# haasoscope_pro_fpga_board_-_before_autor.net
KiCad netlist of a schematic drawn in EAGLE
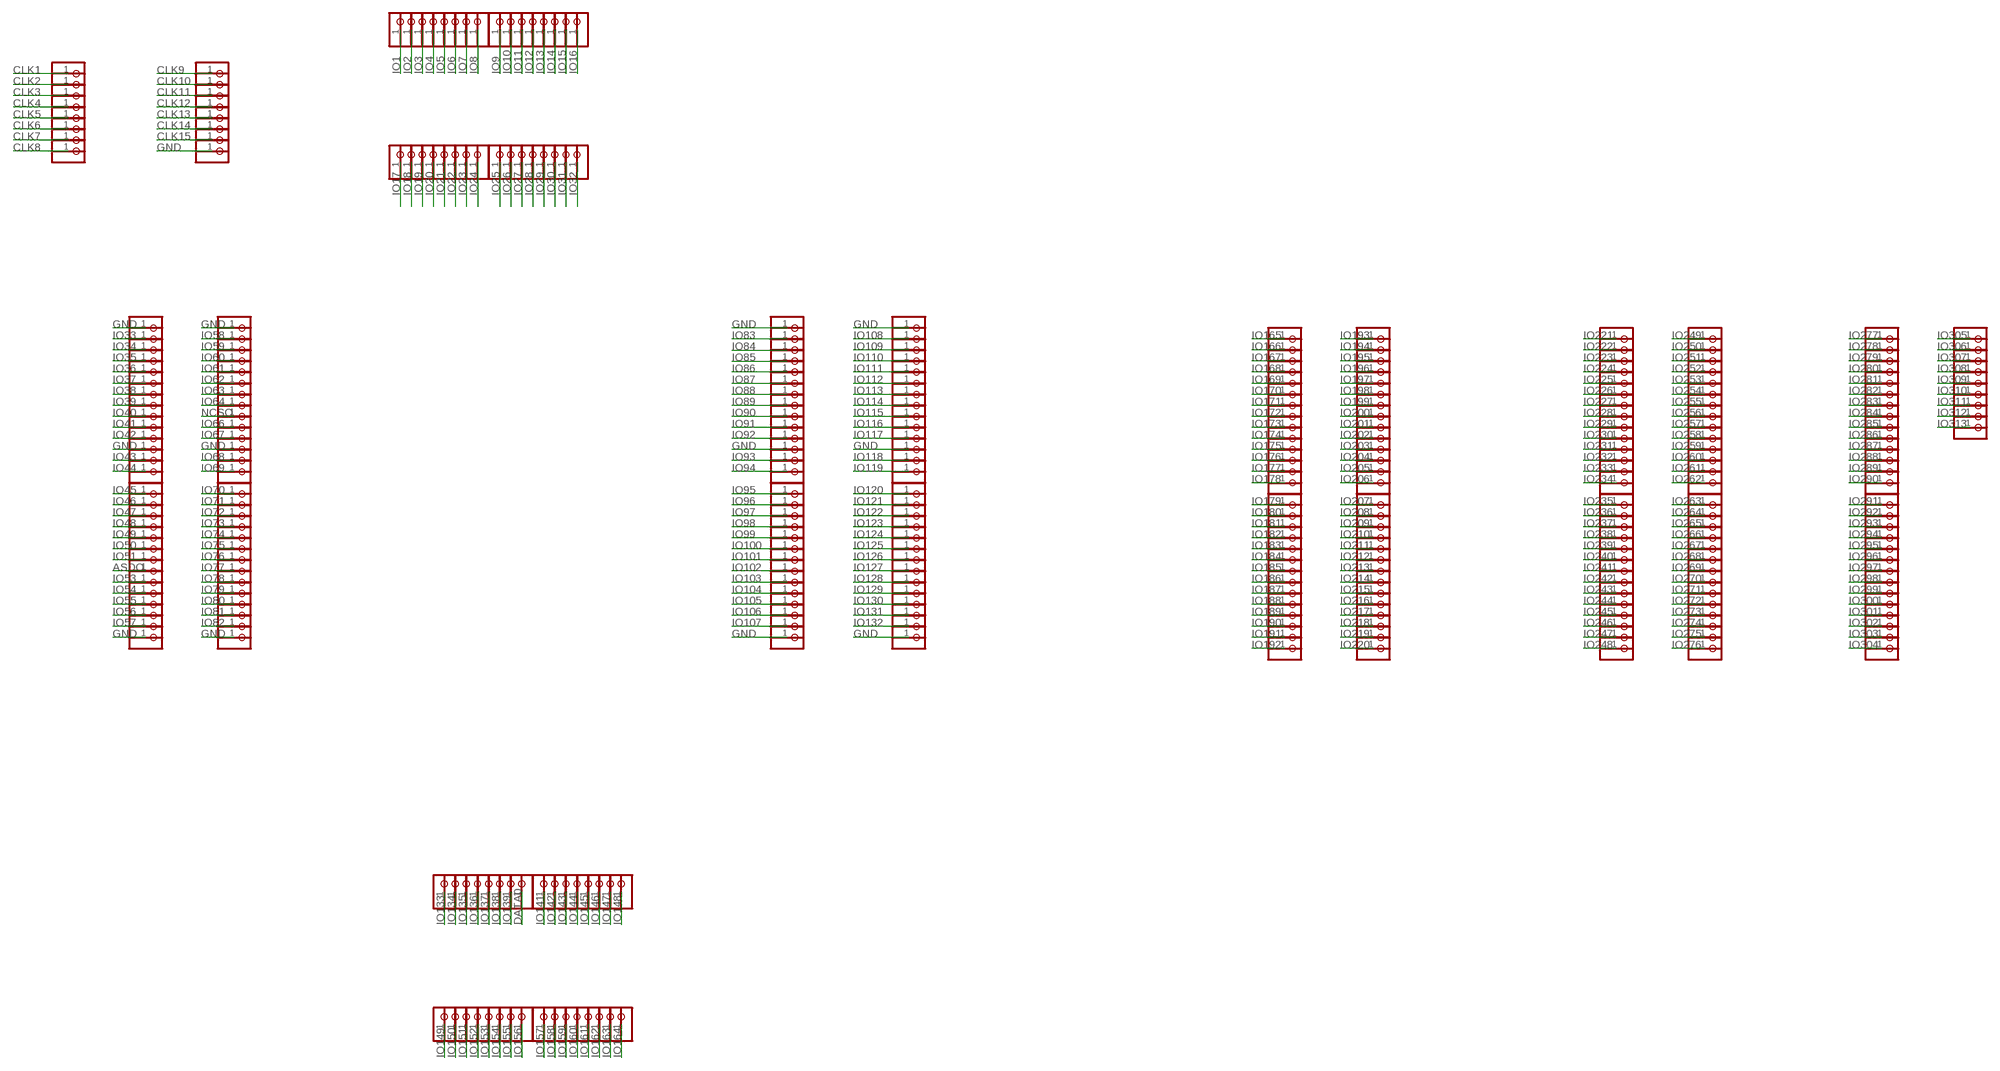
[diagram p0: schematic, sheet 1]
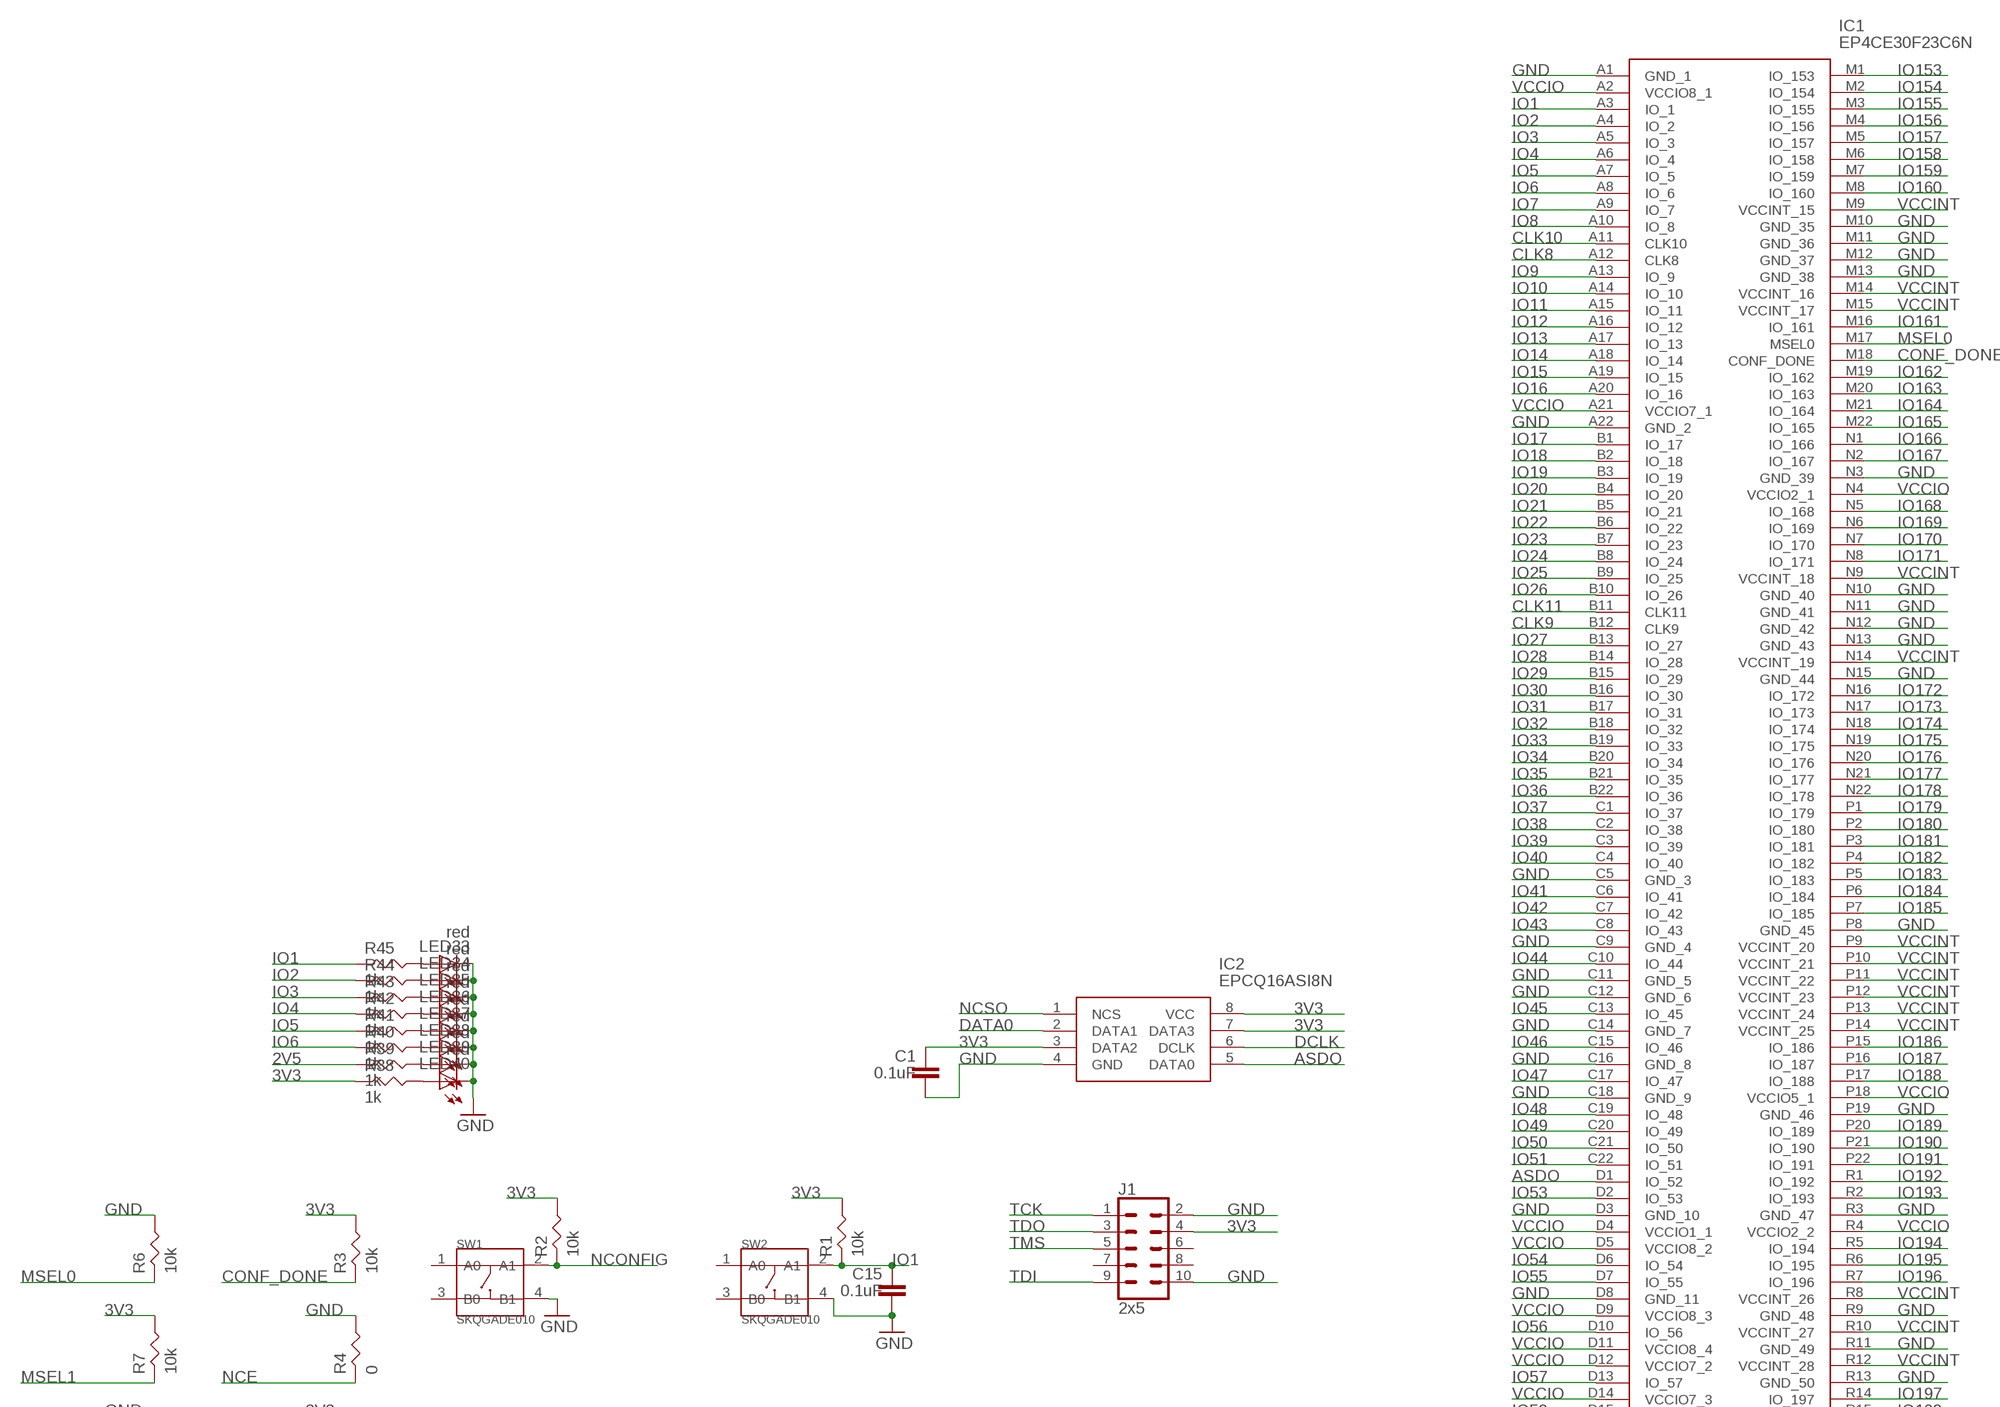
[diagram p1: schematic, sheet 2, part 1 of 2]
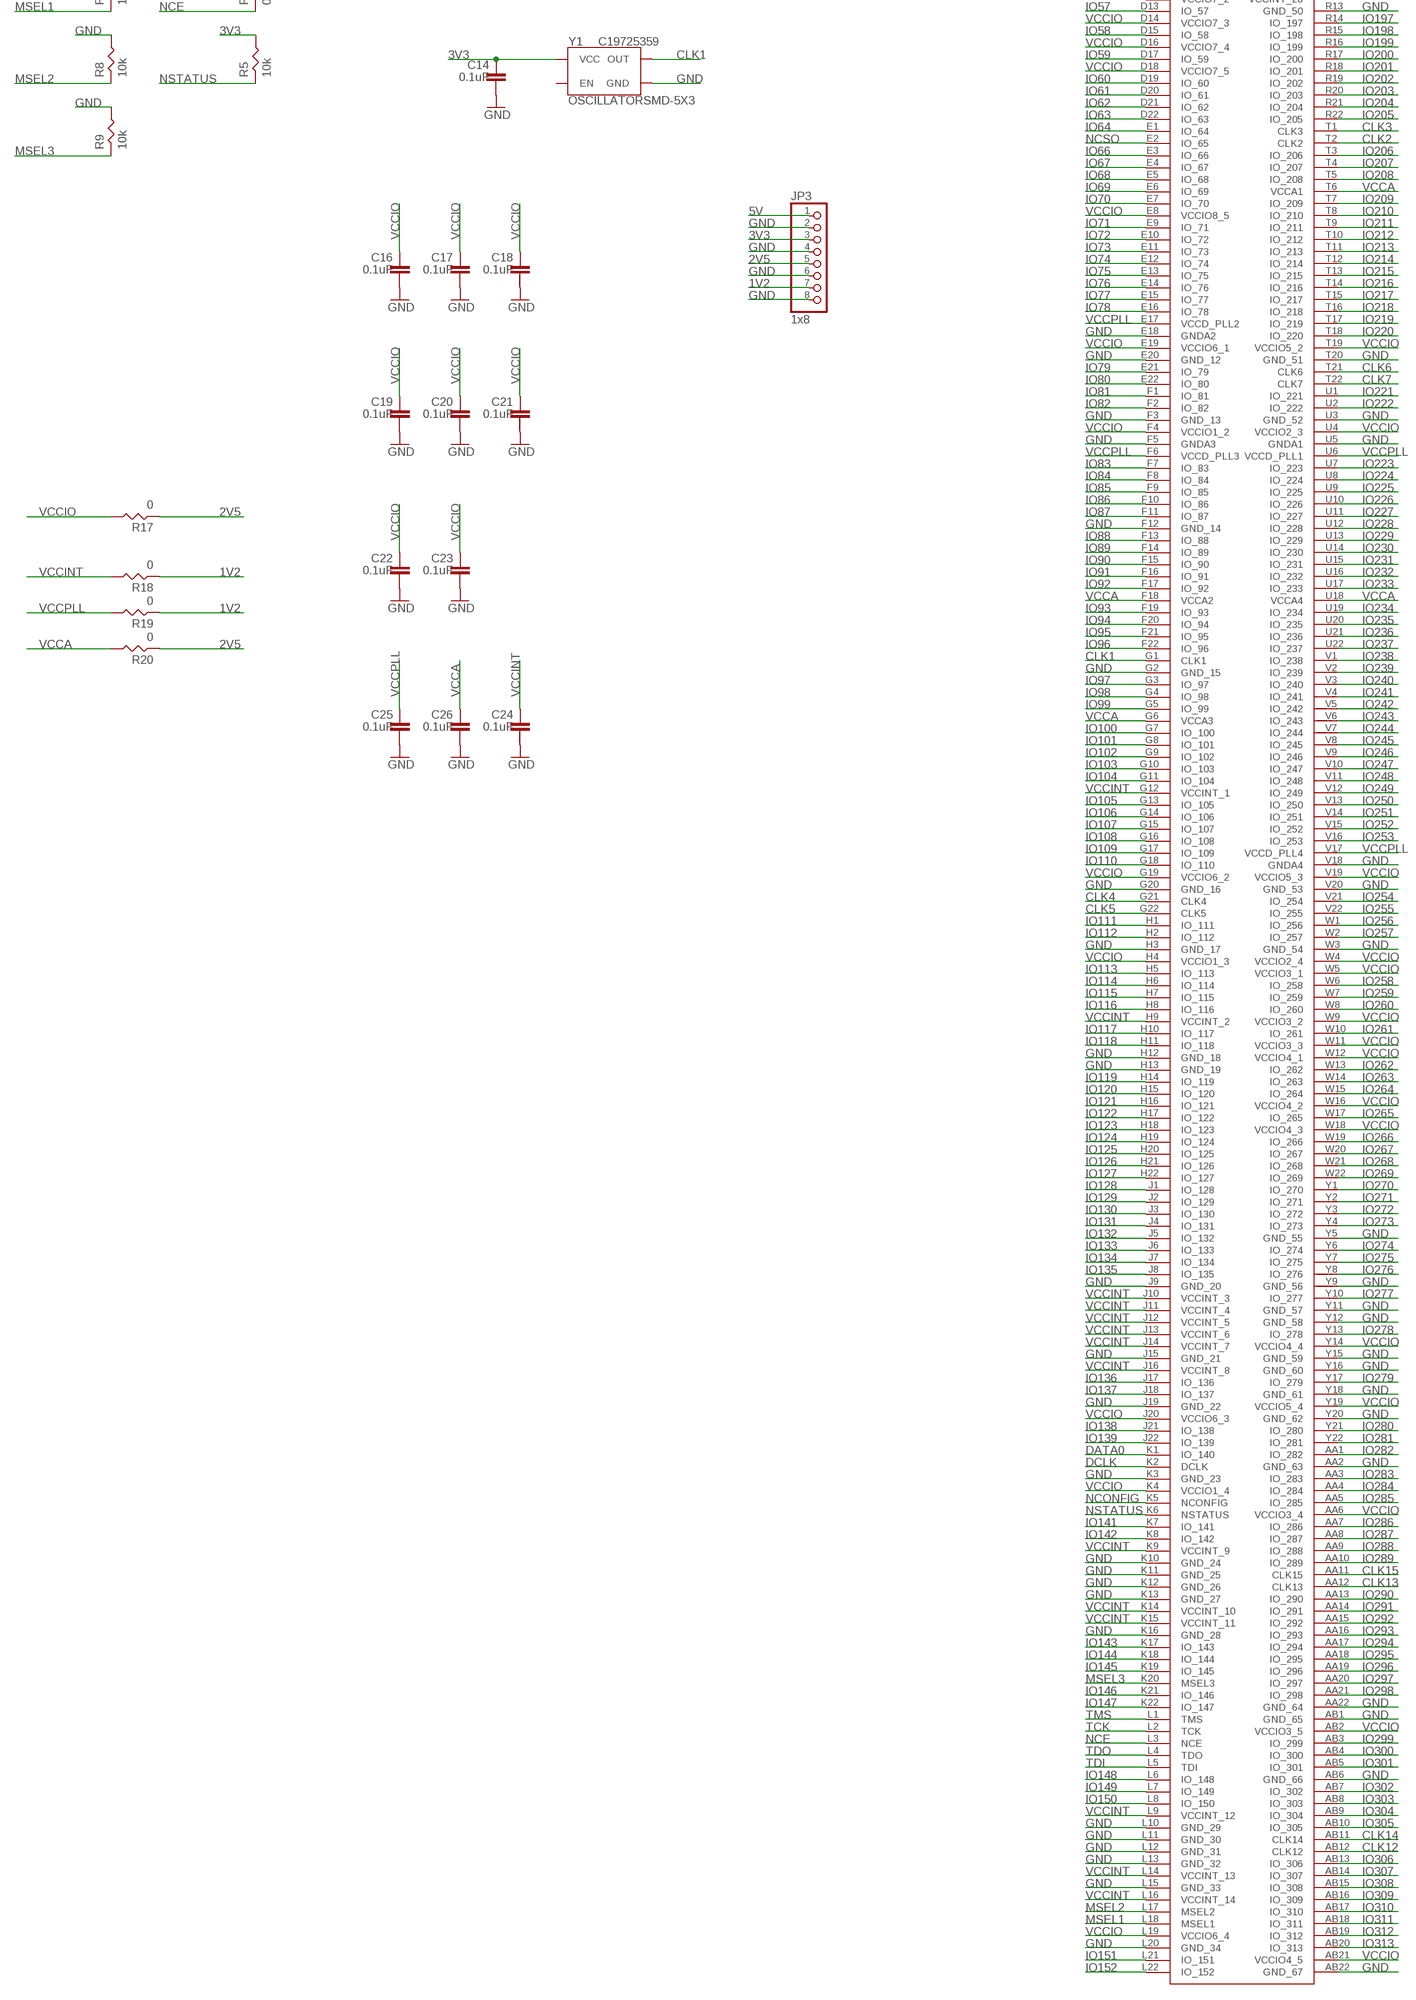
[diagram p2: schematic, sheet 2, part 2 of 2]
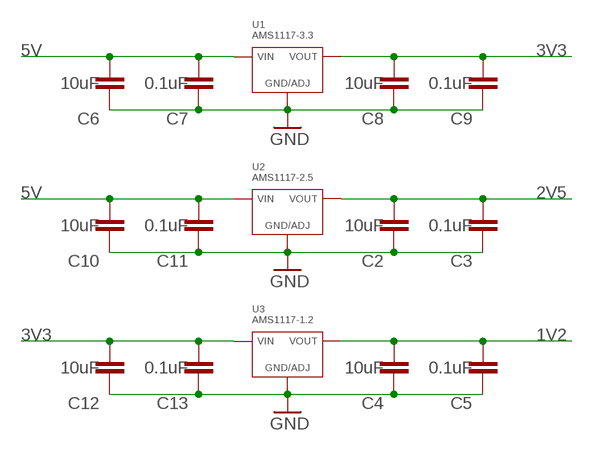
[diagram p3: schematic, sheet 3]

(export (version "E")
  (design (tool "Eeschema 10.0.6"))
  (components
    (comp (ref "C2")
      (value "10uF")
      (footprint "eagle-import:RESC0805_N")
      (libsource (lib "eagle-import") (part "CAPACITOR_0805_N"))
    )
    (comp (ref "C3")
      (value "0.1uF")
      (footprint "eagle-import:RESC0402_N")
      (libsource (lib "eagle-import") (part "CAPACITOR_0402_N"))
    )
    (comp (ref "C4")
      (value "10uF")
      (footprint "eagle-import:RESC0805_N")
      (libsource (lib "eagle-import") (part "CAPACITOR_0805_N"))
    )
    (comp (ref "C5")
      (value "0.1uF")
      (footprint "eagle-import:RESC0402_N")
      (libsource (lib "eagle-import") (part "CAPACITOR_0402_N"))
    )
    (comp (ref "C6")
      (value "10uF")
      (footprint "eagle-import:RESC0805_N")
      (libsource (lib "eagle-import") (part "CAPACITOR_0805_N"))
    )
    (comp (ref "C7")
      (value "0.1uF")
      (footprint "eagle-import:RESC0402_N")
      (libsource (lib "eagle-import") (part "CAPACITOR_0402_N"))
    )
    (comp (ref "C8")
      (value "10uF")
      (footprint "eagle-import:RESC0805_N")
      (libsource (lib "eagle-import") (part "CAPACITOR_0805_N"))
    )
    (comp (ref "C9")
      (value "0.1uF")
      (footprint "eagle-import:RESC0402_N")
      (libsource (lib "eagle-import") (part "CAPACITOR_0402_N"))
    )
    (comp (ref "C10")
      (value "10uF")
      (footprint "eagle-import:RESC0805_N")
      (libsource (lib "eagle-import") (part "CAPACITOR_0805_N"))
    )
    (comp (ref "C11")
      (value "0.1uF")
      (footprint "eagle-import:RESC0402_N")
      (libsource (lib "eagle-import") (part "CAPACITOR_0402_N"))
    )
    (comp (ref "C12")
      (value "10uF")
      (footprint "eagle-import:RESC0805_N")
      (libsource (lib "eagle-import") (part "CAPACITOR_0805_N"))
    )
    (comp (ref "C13")
      (value "0.1uF")
      (footprint "eagle-import:RESC0402_N")
      (libsource (lib "eagle-import") (part "CAPACITOR_0402_N"))
    )
    (comp (ref "U1")
      (value "AMS1117-3.3")
      (footprint "eagle-import:SOT-223-3")
      (fields
        (field (name "HOUSEPART") "NO")
        (field (name "MPN") "NCP1117LPST33T3G")
        (field (name "MPN_1") "AMS1117-3.3")
      )
      (libsource (lib "eagle-import") (part "NCP1117LPST33T3G"))
    )
    (comp (ref "U2")
      (value "AMS1117-2.5")
      (footprint "eagle-import:SOT-223-3")
      (fields
        (field (name "HOUSEPART") "NO")
        (field (name "MPN") "NCP1117LPST33T3G")
        (field (name "MPN_1") "AMS1117-2.5")
      )
      (libsource (lib "eagle-import") (part "NCP1117LPST33T3G"))
    )
    (comp (ref "U3")
      (value "AMS1117-1.2")
      (footprint "eagle-import:SOT-223-3")
      (fields
        (field (name "HOUSEPART") "NO")
        (field (name "MPN") "NCP1117LPST33T3G")
        (field (name "MPN_1") "AMS1117-1.2")
      )
      (libsource (lib "eagle-import") (part "NCP1117LPST33T3G"))
    )
    (comp (ref "JP1")
      (value "1")
      (footprint "eagle-import:1X01")
      (libsource (lib "eagle-import") (part "PINHD-1X1"))
    )
    (comp (ref "JP2")
      (value "1")
      (footprint "eagle-import:1X01")
      (libsource (lib "eagle-import") (part "PINHD-1X1"))
    )
    (comp (ref "JP4")
      (value "1")
      (footprint "eagle-import:1X01")
      (libsource (lib "eagle-import") (part "PINHD-1X1"))
    )
    (comp (ref "JP5")
      (value "1")
      (footprint "eagle-import:1X01")
      (libsource (lib "eagle-import") (part "PINHD-1X1"))
    )
    (comp (ref "JP6")
      (value "1")
      (footprint "eagle-import:1X01")
      (libsource (lib "eagle-import") (part "PINHD-1X1"))
    )
    (comp (ref "JP7")
      (value "1")
      (footprint "eagle-import:1X01")
      (libsource (lib "eagle-import") (part "PINHD-1X1"))
    )
    (comp (ref "JP8")
      (value "1")
      (footprint "eagle-import:1X01")
      (libsource (lib "eagle-import") (part "PINHD-1X1"))
    )
    (comp (ref "JP9")
      (value "1")
      (footprint "eagle-import:1X01")
      (libsource (lib "eagle-import") (part "PINHD-1X1"))
    )
    (comp (ref "JP10")
      (value "1")
      (footprint "eagle-import:1X01")
      (libsource (lib "eagle-import") (part "PINHD-1X1"))
    )
    (comp (ref "JP11")
      (value "1")
      (footprint "eagle-import:1X01")
      (libsource (lib "eagle-import") (part "PINHD-1X1"))
    )
    (comp (ref "JP12")
      (value "1")
      (footprint "eagle-import:1X01")
      (libsource (lib "eagle-import") (part "PINHD-1X1"))
    )
    (comp (ref "JP13")
      (value "1")
      (footprint "eagle-import:1X01")
      (libsource (lib "eagle-import") (part "PINHD-1X1"))
    )
    (comp (ref "JP14")
      (value "1")
      (footprint "eagle-import:1X01")
      (libsource (lib "eagle-import") (part "PINHD-1X1"))
    )
    (comp (ref "JP15")
      (value "1")
      (footprint "eagle-import:1X01")
      (libsource (lib "eagle-import") (part "PINHD-1X1"))
    )
    (comp (ref "JP16")
      (value "1")
      (footprint "eagle-import:1X01")
      (libsource (lib "eagle-import") (part "PINHD-1X1"))
    )
    (comp (ref "JP17")
      (value "1")
      (footprint "eagle-import:1X01")
      (libsource (lib "eagle-import") (part "PINHD-1X1"))
    )
    (comp (ref "JP18")
      (value "1")
      (footprint "eagle-import:1X01")
      (libsource (lib "eagle-import") (part "PINHD-1X1"))
    )
    (comp (ref "JP19")
      (value "1")
      (footprint "eagle-import:1X01")
      (libsource (lib "eagle-import") (part "PINHD-1X1"))
    )
    (comp (ref "JP20")
      (value "1")
      (footprint "eagle-import:1X01")
      (libsource (lib "eagle-import") (part "PINHD-1X1"))
    )
    (comp (ref "JP21")
      (value "1")
      (footprint "eagle-import:1X01")
      (libsource (lib "eagle-import") (part "PINHD-1X1"))
    )
    (comp (ref "JP22")
      (value "1")
      (footprint "eagle-import:1X01")
      (libsource (lib "eagle-import") (part "PINHD-1X1"))
    )
    (comp (ref "JP23")
      (value "1")
      (footprint "eagle-import:1X01")
      (libsource (lib "eagle-import") (part "PINHD-1X1"))
    )
    (comp (ref "JP24")
      (value "1")
      (footprint "eagle-import:1X01")
      (libsource (lib "eagle-import") (part "PINHD-1X1"))
    )
    (comp (ref "JP25")
      (value "1")
      (footprint "eagle-import:1X01")
      (libsource (lib "eagle-import") (part "PINHD-1X1"))
    )
    (comp (ref "JP26")
      (value "1")
      (footprint "eagle-import:1X01")
      (libsource (lib "eagle-import") (part "PINHD-1X1"))
    )
    (comp (ref "JP27")
      (value "1")
      (footprint "eagle-import:1X01")
      (libsource (lib "eagle-import") (part "PINHD-1X1"))
    )
    (comp (ref "JP28")
      (value "1")
      (footprint "eagle-import:1X01")
      (libsource (lib "eagle-import") (part "PINHD-1X1"))
    )
    (comp (ref "JP29")
      (value "1")
      (footprint "eagle-import:1X01")
      (libsource (lib "eagle-import") (part "PINHD-1X1"))
    )
    (comp (ref "JP30")
      (value "1")
      (footprint "eagle-import:1X01")
      (libsource (lib "eagle-import") (part "PINHD-1X1"))
    )
    (comp (ref "JP31")
      (value "1")
      (footprint "eagle-import:1X01")
      (libsource (lib "eagle-import") (part "PINHD-1X1"))
    )
    (comp (ref "JP32")
      (value "1")
      (footprint "eagle-import:1X01")
      (libsource (lib "eagle-import") (part "PINHD-1X1"))
    )
    (comp (ref "JP33")
      (value "1")
      (footprint "eagle-import:1X01")
      (libsource (lib "eagle-import") (part "PINHD-1X1"))
    )
    (comp (ref "JP34")
      (value "1")
      (footprint "eagle-import:1X01")
      (libsource (lib "eagle-import") (part "PINHD-1X1"))
    )
    (comp (ref "JP35")
      (value "1")
      (footprint "eagle-import:1X01")
      (libsource (lib "eagle-import") (part "PINHD-1X1"))
    )
    (comp (ref "JP36")
      (value "1")
      (footprint "eagle-import:1X01")
      (libsource (lib "eagle-import") (part "PINHD-1X1"))
    )
    (comp (ref "JP37")
      (value "1")
      (footprint "eagle-import:1X01")
      (libsource (lib "eagle-import") (part "PINHD-1X1"))
    )
    (comp (ref "JP38")
      (value "1")
      (footprint "eagle-import:1X01")
      (libsource (lib "eagle-import") (part "PINHD-1X1"))
    )
    (comp (ref "JP39")
      (value "1")
      (footprint "eagle-import:1X01")
      (libsource (lib "eagle-import") (part "PINHD-1X1"))
    )
    (comp (ref "JP40")
      (value "1")
      (footprint "eagle-import:1X01")
      (libsource (lib "eagle-import") (part "PINHD-1X1"))
    )
    (comp (ref "JP41")
      (value "1")
      (footprint "eagle-import:1X01")
      (libsource (lib "eagle-import") (part "PINHD-1X1"))
    )
    (comp (ref "JP42")
      (value "1")
      (footprint "eagle-import:1X01")
      (libsource (lib "eagle-import") (part "PINHD-1X1"))
    )
    (comp (ref "JP43")
      (value "1")
      (footprint "eagle-import:1X01")
      (libsource (lib "eagle-import") (part "PINHD-1X1"))
    )
    (comp (ref "JP44")
      (value "1")
      (footprint "eagle-import:1X01")
      (libsource (lib "eagle-import") (part "PINHD-1X1"))
    )
    (comp (ref "JP45")
      (value "1")
      (footprint "eagle-import:1X01")
      (libsource (lib "eagle-import") (part "PINHD-1X1"))
    )
    (comp (ref "JP46")
      (value "1")
      (footprint "eagle-import:1X01")
      (libsource (lib "eagle-import") (part "PINHD-1X1"))
    )
    (comp (ref "JP47")
      (value "1")
      (footprint "eagle-import:1X01")
      (libsource (lib "eagle-import") (part "PINHD-1X1"))
    )
    (comp (ref "JP48")
      (value "1")
      (footprint "eagle-import:1X01")
      (libsource (lib "eagle-import") (part "PINHD-1X1"))
    )
    (comp (ref "JP49")
      (value "1")
      (footprint "eagle-import:1X01")
      (libsource (lib "eagle-import") (part "PINHD-1X1"))
    )
    (comp (ref "JP50")
      (value "1")
      (footprint "eagle-import:1X01")
      (libsource (lib "eagle-import") (part "PINHD-1X1"))
    )
    (comp (ref "JP51")
      (value "1")
      (footprint "eagle-import:1X01")
      (libsource (lib "eagle-import") (part "PINHD-1X1"))
    )
    (comp (ref "JP52")
      (value "1")
      (footprint "eagle-import:1X01")
      (libsource (lib "eagle-import") (part "PINHD-1X1"))
    )
    (comp (ref "JP53")
      (value "1")
      (footprint "eagle-import:1X01")
      (libsource (lib "eagle-import") (part "PINHD-1X1"))
    )
    (comp (ref "JP54")
      (value "1")
      (footprint "eagle-import:1X01")
      (libsource (lib "eagle-import") (part "PINHD-1X1"))
    )
    (comp (ref "JP55")
      (value "1")
      (footprint "eagle-import:1X01")
      (libsource (lib "eagle-import") (part "PINHD-1X1"))
    )
    (comp (ref "JP56")
      (value "1")
      (footprint "eagle-import:1X01")
      (libsource (lib "eagle-import") (part "PINHD-1X1"))
    )
    (comp (ref "JP57")
      (value "1")
      (footprint "eagle-import:1X01")
      (libsource (lib "eagle-import") (part "PINHD-1X1"))
    )
    (comp (ref "JP58")
      (value "1")
      (footprint "eagle-import:1X01")
      (libsource (lib "eagle-import") (part "PINHD-1X1"))
    )
    (comp (ref "JP59")
      (value "1")
      (footprint "eagle-import:1X01")
      (libsource (lib "eagle-import") (part "PINHD-1X1"))
    )
    (comp (ref "JP60")
      (value "1")
      (footprint "eagle-import:1X01")
      (libsource (lib "eagle-import") (part "PINHD-1X1"))
    )
    (comp (ref "JP61")
      (value "1")
      (footprint "eagle-import:1X01")
      (libsource (lib "eagle-import") (part "PINHD-1X1"))
    )
    (comp (ref "JP62")
      (value "1")
      (footprint "eagle-import:1X01")
      (libsource (lib "eagle-import") (part "PINHD-1X1"))
    )
    (comp (ref "JP63")
      (value "1")
      (footprint "eagle-import:1X01")
      (libsource (lib "eagle-import") (part "PINHD-1X1"))
    )
    (comp (ref "JP64")
      (value "1")
      (footprint "eagle-import:1X01")
      (libsource (lib "eagle-import") (part "PINHD-1X1"))
    )
    (comp (ref "JP65")
      (value "1")
      (footprint "eagle-import:1X01")
      (libsource (lib "eagle-import") (part "PINHD-1X1"))
    )
    (comp (ref "JP66")
      (value "1")
      (footprint "eagle-import:1X01")
      (libsource (lib "eagle-import") (part "PINHD-1X1"))
    )
    (comp (ref "JP67")
      (value "1")
      (footprint "eagle-import:1X01")
      (libsource (lib "eagle-import") (part "PINHD-1X1"))
    )
    (comp (ref "JP68")
      (value "1")
      (footprint "eagle-import:1X01")
      (libsource (lib "eagle-import") (part "PINHD-1X1"))
    )
    (comp (ref "JP69")
      (value "1")
      (footprint "eagle-import:1X01")
      (libsource (lib "eagle-import") (part "PINHD-1X1"))
    )
    (comp (ref "JP70")
      (value "1")
      (footprint "eagle-import:1X01")
      (libsource (lib "eagle-import") (part "PINHD-1X1"))
    )
    (comp (ref "JP71")
      (value "1")
      (footprint "eagle-import:1X01")
      (libsource (lib "eagle-import") (part "PINHD-1X1"))
    )
    (comp (ref "JP72")
      (value "1")
      (footprint "eagle-import:1X01")
      (libsource (lib "eagle-import") (part "PINHD-1X1"))
    )
    (comp (ref "JP73")
      (value "1")
      (footprint "eagle-import:1X01")
      (libsource (lib "eagle-import") (part "PINHD-1X1"))
    )
    (comp (ref "JP74")
      (value "1")
      (footprint "eagle-import:1X01")
      (libsource (lib "eagle-import") (part "PINHD-1X1"))
    )
    (comp (ref "JP75")
      (value "1")
      (footprint "eagle-import:1X01")
      (libsource (lib "eagle-import") (part "PINHD-1X1"))
    )
    (comp (ref "JP76")
      (value "1")
      (footprint "eagle-import:1X01")
      (libsource (lib "eagle-import") (part "PINHD-1X1"))
    )
    (comp (ref "JP77")
      (value "1")
      (footprint "eagle-import:1X01")
      (libsource (lib "eagle-import") (part "PINHD-1X1"))
    )
    (comp (ref "JP78")
      (value "1")
      (footprint "eagle-import:1X01")
      (libsource (lib "eagle-import") (part "PINHD-1X1"))
    )
    (comp (ref "JP79")
      (value "1")
      (footprint "eagle-import:1X01")
      (libsource (lib "eagle-import") (part "PINHD-1X1"))
    )
    (comp (ref "JP80")
      (value "1")
      (footprint "eagle-import:1X01")
      (libsource (lib "eagle-import") (part "PINHD-1X1"))
    )
    (comp (ref "JP81")
      (value "1")
      (footprint "eagle-import:1X01")
      (libsource (lib "eagle-import") (part "PINHD-1X1"))
    )
    (comp (ref "JP82")
      (value "1")
      (footprint "eagle-import:1X01")
      (libsource (lib "eagle-import") (part "PINHD-1X1"))
    )
    (comp (ref "JP83")
      (value "1")
      (footprint "eagle-import:1X01")
      (libsource (lib "eagle-import") (part "PINHD-1X1"))
    )
    (comp (ref "JP84")
      (value "1")
      (footprint "eagle-import:1X01")
      (libsource (lib "eagle-import") (part "PINHD-1X1"))
    )
    (comp (ref "JP85")
      (value "1")
      (footprint "eagle-import:1X01")
      (libsource (lib "eagle-import") (part "PINHD-1X1"))
    )
    (comp (ref "JP86")
      (value "1")
      (footprint "eagle-import:1X01")
      (libsource (lib "eagle-import") (part "PINHD-1X1"))
    )
    (comp (ref "JP87")
      (value "1")
      (footprint "eagle-import:1X01")
      (libsource (lib "eagle-import") (part "PINHD-1X1"))
    )
    (comp (ref "JP88")
      (value "1")
      (footprint "eagle-import:1X01")
      (libsource (lib "eagle-import") (part "PINHD-1X1"))
    )
    (comp (ref "JP89")
      (value "1")
      (footprint "eagle-import:1X01")
      (libsource (lib "eagle-import") (part "PINHD-1X1"))
    )
    (comp (ref "JP90")
      (value "1")
      (footprint "eagle-import:1X01")
      (libsource (lib "eagle-import") (part "PINHD-1X1"))
    )
    (comp (ref "JP91")
      (value "1")
      (footprint "eagle-import:1X01")
      (libsource (lib "eagle-import") (part "PINHD-1X1"))
    )
    (comp (ref "JP92")
      (value "1")
      (footprint "eagle-import:1X01")
      (libsource (lib "eagle-import") (part "PINHD-1X1"))
    )
    (comp (ref "JP93")
      (value "1")
      (footprint "eagle-import:1X01")
      (libsource (lib "eagle-import") (part "PINHD-1X1"))
    )
    (comp (ref "JP94")
      (value "1")
      (footprint "eagle-import:1X01")
      (libsource (lib "eagle-import") (part "PINHD-1X1"))
    )
    (comp (ref "JP95")
      (value "1")
      (footprint "eagle-import:1X01")
      (libsource (lib "eagle-import") (part "PINHD-1X1"))
    )
    (comp (ref "JP96")
      (value "1")
      (footprint "eagle-import:1X01")
      (libsource (lib "eagle-import") (part "PINHD-1X1"))
    )
    (comp (ref "JP97")
      (value "1")
      (footprint "eagle-import:1X01")
      (libsource (lib "eagle-import") (part "PINHD-1X1"))
    )
    (comp (ref "JP98")
      (value "1")
      (footprint "eagle-import:1X01")
      (libsource (lib "eagle-import") (part "PINHD-1X1"))
    )
    (comp (ref "JP99")
      (value "1")
      (footprint "eagle-import:1X01")
      (libsource (lib "eagle-import") (part "PINHD-1X1"))
    )
    (comp (ref "JP100")
      (value "1")
      (footprint "eagle-import:1X01")
      (libsource (lib "eagle-import") (part "PINHD-1X1"))
    )
    (comp (ref "JP101")
      (value "1")
      (footprint "eagle-import:1X01")
      (libsource (lib "eagle-import") (part "PINHD-1X1"))
    )
    (comp (ref "JP102")
      (value "1")
      (footprint "eagle-import:1X01")
      (libsource (lib "eagle-import") (part "PINHD-1X1"))
    )
    (comp (ref "JP103")
      (value "1")
      (footprint "eagle-import:1X01")
      (libsource (lib "eagle-import") (part "PINHD-1X1"))
    )
    (comp (ref "JP104")
      (value "1")
      (footprint "eagle-import:1X01")
      (libsource (lib "eagle-import") (part "PINHD-1X1"))
    )
    (comp (ref "JP105")
      (value "1")
      (footprint "eagle-import:1X01")
      (libsource (lib "eagle-import") (part "PINHD-1X1"))
    )
    (comp (ref "JP106")
      (value "1")
      (footprint "eagle-import:1X01")
      (libsource (lib "eagle-import") (part "PINHD-1X1"))
    )
    (comp (ref "JP107")
      (value "1")
      (footprint "eagle-import:1X01")
      (libsource (lib "eagle-import") (part "PINHD-1X1"))
    )
    (comp (ref "JP108")
      (value "1")
      (footprint "eagle-import:1X01")
      (libsource (lib "eagle-import") (part "PINHD-1X1"))
    )
    (comp (ref "JP109")
      (value "1")
      (footprint "eagle-import:1X01")
      (libsource (lib "eagle-import") (part "PINHD-1X1"))
    )
    (comp (ref "JP110")
      (value "1")
      (footprint "eagle-import:1X01")
      (libsource (lib "eagle-import") (part "PINHD-1X1"))
    )
    (comp (ref "JP111")
      (value "1")
      (footprint "eagle-import:1X01")
      (libsource (lib "eagle-import") (part "PINHD-1X1"))
    )
    (comp (ref "JP112")
      (value "1")
      (footprint "eagle-import:1X01")
      (libsource (lib "eagle-import") (part "PINHD-1X1"))
    )
    (comp (ref "JP113")
      (value "1")
      (footprint "eagle-import:1X01")
      (libsource (lib "eagle-import") (part "PINHD-1X1"))
    )
    (comp (ref "JP114")
      (value "1")
      (footprint "eagle-import:1X01")
      (libsource (lib "eagle-import") (part "PINHD-1X1"))
    )
    (comp (ref "JP115")
      (value "1")
      (footprint "eagle-import:1X01")
      (libsource (lib "eagle-import") (part "PINHD-1X1"))
    )
    (comp (ref "JP116")
      (value "1")
      (footprint "eagle-import:1X01")
      (libsource (lib "eagle-import") (part "PINHD-1X1"))
    )
    (comp (ref "JP117")
      (value "1")
      (footprint "eagle-import:1X01")
      (libsource (lib "eagle-import") (part "PINHD-1X1"))
    )
    (comp (ref "JP118")
      (value "1")
      (footprint "eagle-import:1X01")
      (libsource (lib "eagle-import") (part "PINHD-1X1"))
    )
    (comp (ref "JP119")
      (value "1")
      (footprint "eagle-import:1X01")
      (libsource (lib "eagle-import") (part "PINHD-1X1"))
    )
    (comp (ref "JP120")
      (value "1")
      (footprint "eagle-import:1X01")
      (libsource (lib "eagle-import") (part "PINHD-1X1"))
    )
    (comp (ref "JP121")
      (value "1")
      (footprint "eagle-import:1X01")
      (libsource (lib "eagle-import") (part "PINHD-1X1"))
    )
    (comp (ref "JP122")
      (value "1")
      (footprint "eagle-import:1X01")
      (libsource (lib "eagle-import") (part "PINHD-1X1"))
    )
    (comp (ref "JP123")
      (value "1")
      (footprint "eagle-import:1X01")
      (libsource (lib "eagle-import") (part "PINHD-1X1"))
    )
    (comp (ref "JP124")
      (value "1")
      (footprint "eagle-import:1X01")
      (libsource (lib "eagle-import") (part "PINHD-1X1"))
    )
    (comp (ref "JP125")
      (value "1")
      (footprint "eagle-import:1X01")
      (libsource (lib "eagle-import") (part "PINHD-1X1"))
    )
    (comp (ref "JP126")
      (value "1")
      (footprint "eagle-import:1X01")
      (libsource (lib "eagle-import") (part "PINHD-1X1"))
    )
    (comp (ref "JP127")
      (value "1")
      (footprint "eagle-import:1X01")
      (libsource (lib "eagle-import") (part "PINHD-1X1"))
    )
    (comp (ref "JP128")
      (value "1")
      (footprint "eagle-import:1X01")
      (libsource (lib "eagle-import") (part "PINHD-1X1"))
    )
    (comp (ref "JP129")
      (value "1")
      (footprint "eagle-import:1X01")
      (libsource (lib "eagle-import") (part "PINHD-1X1"))
    )
    (comp (ref "JP130")
      (value "1")
      (footprint "eagle-import:1X01")
      (libsource (lib "eagle-import") (part "PINHD-1X1"))
    )
    (comp (ref "JP131")
      (value "1")
      (footprint "eagle-import:1X01")
      (libsource (lib "eagle-import") (part "PINHD-1X1"))
    )
    (comp (ref "JP132")
      (value "1")
      (footprint "eagle-import:1X01")
      (libsource (lib "eagle-import") (part "PINHD-1X1"))
    )
    (comp (ref "JP133")
      (value "1")
      (footprint "eagle-import:1X01")
      (libsource (lib "eagle-import") (part "PINHD-1X1"))
    )
    (comp (ref "JP134")
      (value "1")
      (footprint "eagle-import:1X01")
      (libsource (lib "eagle-import") (part "PINHD-1X1"))
    )
    (comp (ref "JP135")
      (value "1")
      (footprint "eagle-import:1X01")
      (libsource (lib "eagle-import") (part "PINHD-1X1"))
    )
    (comp (ref "JP136")
      (value "1")
      (footprint "eagle-import:1X01")
      (libsource (lib "eagle-import") (part "PINHD-1X1"))
    )
    (comp (ref "JP137")
      (value "1")
      (footprint "eagle-import:1X01")
      (libsource (lib "eagle-import") (part "PINHD-1X1"))
    )
    (comp (ref "JP138")
      (value "1")
      (footprint "eagle-import:1X01")
      (libsource (lib "eagle-import") (part "PINHD-1X1"))
    )
    (comp (ref "JP139")
      (value "1")
      (footprint "eagle-import:1X01")
      (libsource (lib "eagle-import") (part "PINHD-1X1"))
    )
    (comp (ref "JP140")
      (value "1")
      (footprint "eagle-import:1X01")
      (libsource (lib "eagle-import") (part "PINHD-1X1"))
    )
    (comp (ref "JP141")
      (value "1")
      (footprint "eagle-import:1X01")
      (libsource (lib "eagle-import") (part "PINHD-1X1"))
    )
    (comp (ref "JP142")
      (value "1")
      (footprint "eagle-import:1X01")
      (libsource (lib "eagle-import") (part "PINHD-1X1"))
    )
    (comp (ref "JP143")
      (value "1")
      (footprint "eagle-import:1X01")
      (libsource (lib "eagle-import") (part "PINHD-1X1"))
    )
    (comp (ref "JP144")
      (value "1")
      (footprint "eagle-import:1X01")
      (libsource (lib "eagle-import") (part "PINHD-1X1"))
    )
    (comp (ref "JP145")
      (value "1")
      (footprint "eagle-import:1X01")
      (libsource (lib "eagle-import") (part "PINHD-1X1"))
    )
    (comp (ref "JP146")
      (value "1")
      (footprint "eagle-import:1X01")
      (libsource (lib "eagle-import") (part "PINHD-1X1"))
    )
    (comp (ref "JP147")
      (value "1")
      (footprint "eagle-import:1X01")
      (libsource (lib "eagle-import") (part "PINHD-1X1"))
    )
    (comp (ref "JP148")
      (value "1")
      (footprint "eagle-import:1X01")
      (libsource (lib "eagle-import") (part "PINHD-1X1"))
    )
    (comp (ref "JP149")
      (value "1")
      (footprint "eagle-import:1X01")
      (libsource (lib "eagle-import") (part "PINHD-1X1"))
    )
    (comp (ref "JP150")
      (value "1")
      (footprint "eagle-import:1X01")
      (libsource (lib "eagle-import") (part "PINHD-1X1"))
    )
    (comp (ref "JP151")
      (value "1")
      (footprint "eagle-import:1X01")
      (libsource (lib "eagle-import") (part "PINHD-1X1"))
    )
    (comp (ref "JP152")
      (value "1")
      (footprint "eagle-import:1X01")
      (libsource (lib "eagle-import") (part "PINHD-1X1"))
    )
    (comp (ref "JP153")
      (value "1")
      (footprint "eagle-import:1X01")
      (libsource (lib "eagle-import") (part "PINHD-1X1"))
    )
    (comp (ref "JP154")
      (value "1")
      (footprint "eagle-import:1X01")
      (libsource (lib "eagle-import") (part "PINHD-1X1"))
    )
    (comp (ref "JP155")
      (value "1")
      (footprint "eagle-import:1X01")
      (libsource (lib "eagle-import") (part "PINHD-1X1"))
    )
    (comp (ref "JP156")
      (value "1")
      (footprint "eagle-import:1X01")
      (libsource (lib "eagle-import") (part "PINHD-1X1"))
    )
    (comp (ref "JP157")
      (value "1")
      (footprint "eagle-import:1X01")
      (libsource (lib "eagle-import") (part "PINHD-1X1"))
    )
    (comp (ref "JP158")
      (value "1")
      (footprint "eagle-import:1X01")
      (libsource (lib "eagle-import") (part "PINHD-1X1"))
    )
    (comp (ref "JP159")
      (value "1")
      (footprint "eagle-import:1X01")
      (libsource (lib "eagle-import") (part "PINHD-1X1"))
    )
    (comp (ref "JP160")
      (value "1")
      (footprint "eagle-import:1X01")
      (libsource (lib "eagle-import") (part "PINHD-1X1"))
    )
    (comp (ref "JP161")
      (value "1")
      (footprint "eagle-import:1X01")
      (libsource (lib "eagle-import") (part "PINHD-1X1"))
    )
    (comp (ref "JP162")
      (value "1")
      (footprint "eagle-import:1X01")
      (libsource (lib "eagle-import") (part "PINHD-1X1"))
    )
    (comp (ref "JP163")
      (value "1")
      (footprint "eagle-import:1X01")
      (libsource (lib "eagle-import") (part "PINHD-1X1"))
    )
    (comp (ref "JP164")
      (value "1")
      (footprint "eagle-import:1X01")
      (libsource (lib "eagle-import") (part "PINHD-1X1"))
    )
    (comp (ref "JP165")
      (value "1")
      (footprint "eagle-import:1X01")
      (libsource (lib "eagle-import") (part "PINHD-1X1"))
    )
    (comp (ref "JP166")
      (value "1")
      (footprint "eagle-import:1X01")
      (libsource (lib "eagle-import") (part "PINHD-1X1"))
    )
    (comp (ref "JP167")
      (value "1")
      (footprint "eagle-import:1X01")
      (libsource (lib "eagle-import") (part "PINHD-1X1"))
    )
    (comp (ref "JP168")
      (value "1")
      (footprint "eagle-import:1X01")
      (libsource (lib "eagle-import") (part "PINHD-1X1"))
    )
    (comp (ref "JP169")
      (value "1")
      (footprint "eagle-import:1X01")
      (libsource (lib "eagle-import") (part "PINHD-1X1"))
    )
    (comp (ref "JP170")
      (value "1")
      (footprint "eagle-import:1X01")
      (libsource (lib "eagle-import") (part "PINHD-1X1"))
    )
    (comp (ref "JP171")
      (value "1")
      (footprint "eagle-import:1X01")
      (libsource (lib "eagle-import") (part "PINHD-1X1"))
    )
    (comp (ref "JP172")
      (value "1")
      (footprint "eagle-import:1X01")
      (libsource (lib "eagle-import") (part "PINHD-1X1"))
    )
    (comp (ref "JP173")
      (value "1")
      (footprint "eagle-import:1X01")
      (libsource (lib "eagle-import") (part "PINHD-1X1"))
    )
    (comp (ref "JP174")
      (value "1")
      (footprint "eagle-import:1X01")
      (libsource (lib "eagle-import") (part "PINHD-1X1"))
    )
    (comp (ref "JP175")
      (value "1")
      (footprint "eagle-import:1X01")
      (libsource (lib "eagle-import") (part "PINHD-1X1"))
    )
    (comp (ref "JP176")
      (value "1")
      (footprint "eagle-import:1X01")
      (libsource (lib "eagle-import") (part "PINHD-1X1"))
    )
    (comp (ref "JP177")
      (value "1")
      (footprint "eagle-import:1X01")
      (libsource (lib "eagle-import") (part "PINHD-1X1"))
    )
    (comp (ref "JP178")
      (value "1")
      (footprint "eagle-import:1X01")
      (libsource (lib "eagle-import") (part "PINHD-1X1"))
    )
    (comp (ref "JP179")
      (value "1")
      (footprint "eagle-import:1X01")
      (libsource (lib "eagle-import") (part "PINHD-1X1"))
    )
    (comp (ref "JP180")
      (value "1")
      (footprint "eagle-import:1X01")
      (libsource (lib "eagle-import") (part "PINHD-1X1"))
    )
    (comp (ref "JP181")
      (value "1")
      (footprint "eagle-import:1X01")
      (libsource (lib "eagle-import") (part "PINHD-1X1"))
    )
    (comp (ref "JP182")
      (value "1")
      (footprint "eagle-import:1X01")
      (libsource (lib "eagle-import") (part "PINHD-1X1"))
    )
    (comp (ref "JP183")
      (value "1")
      (footprint "eagle-import:1X01")
      (libsource (lib "eagle-import") (part "PINHD-1X1"))
    )
    (comp (ref "JP184")
      (value "1")
      (footprint "eagle-import:1X01")
      (libsource (lib "eagle-import") (part "PINHD-1X1"))
    )
    (comp (ref "JP185")
      (value "1")
      (footprint "eagle-import:1X01")
      (libsource (lib "eagle-import") (part "PINHD-1X1"))
    )
    (comp (ref "JP186")
      (value "1")
      (footprint "eagle-import:1X01")
      (libsource (lib "eagle-import") (part "PINHD-1X1"))
    )
    (comp (ref "JP187")
      (value "1")
      (footprint "eagle-import:1X01")
      (libsource (lib "eagle-import") (part "PINHD-1X1"))
    )
    (comp (ref "JP188")
      (value "1")
      (footprint "eagle-import:1X01")
      (libsource (lib "eagle-import") (part "PINHD-1X1"))
    )
    (comp (ref "JP189")
      (value "1")
      (footprint "eagle-import:1X01")
      (libsource (lib "eagle-import") (part "PINHD-1X1"))
    )
    (comp (ref "JP190")
      (value "1")
      (footprint "eagle-import:1X01")
      (libsource (lib "eagle-import") (part "PINHD-1X1"))
    )
    (comp (ref "JP191")
      (value "1")
      (footprint "eagle-import:1X01")
      (libsource (lib "eagle-import") (part "PINHD-1X1"))
    )
    (comp (ref "JP192")
      (value "1")
      (footprint "eagle-import:1X01")
      (libsource (lib "eagle-import") (part "PINHD-1X1"))
    )
    (comp (ref "JP193")
      (value "1")
      (footprint "eagle-import:1X01")
      (libsource (lib "eagle-import") (part "PINHD-1X1"))
    )
    (comp (ref "JP194")
      (value "1")
      (footprint "eagle-import:1X01")
      (libsource (lib "eagle-import") (part "PINHD-1X1"))
    )
    (comp (ref "JP195")
      (value "1")
      (footprint "eagle-import:1X01")
      (libsource (lib "eagle-import") (part "PINHD-1X1"))
    )
    (comp (ref "JP196")
      (value "1")
      (footprint "eagle-import:1X01")
      (libsource (lib "eagle-import") (part "PINHD-1X1"))
    )
    (comp (ref "JP197")
      (value "1")
      (footprint "eagle-import:1X01")
      (libsource (lib "eagle-import") (part "PINHD-1X1"))
    )
    (comp (ref "JP198")
      (value "1")
      (footprint "eagle-import:1X01")
      (libsource (lib "eagle-import") (part "PINHD-1X1"))
    )
    (comp (ref "JP199")
      (value "1")
      (footprint "eagle-import:1X01")
      (libsource (lib "eagle-import") (part "PINHD-1X1"))
    )
    (comp (ref "JP200")
      (value "1")
      (footprint "eagle-import:1X01")
      (libsource (lib "eagle-import") (part "PINHD-1X1"))
    )
    (comp (ref "JP201")
      (value "1")
      (footprint "eagle-import:1X01")
      (libsource (lib "eagle-import") (part "PINHD-1X1"))
    )
    (comp (ref "JP202")
      (value "1")
      (footprint "eagle-import:1X01")
      (libsource (lib "eagle-import") (part "PINHD-1X1"))
    )
    (comp (ref "JP203")
      (value "1")
      (footprint "eagle-import:1X01")
      (libsource (lib "eagle-import") (part "PINHD-1X1"))
    )
    (comp (ref "JP204")
      (value "1")
      (footprint "eagle-import:1X01")
      (libsource (lib "eagle-import") (part "PINHD-1X1"))
    )
    (comp (ref "JP205")
      (value "1")
      (footprint "eagle-import:1X01")
      (libsource (lib "eagle-import") (part "PINHD-1X1"))
    )
    (comp (ref "JP206")
      (value "1")
      (footprint "eagle-import:1X01")
      (libsource (lib "eagle-import") (part "PINHD-1X1"))
    )
    (comp (ref "JP207")
      (value "1")
      (footprint "eagle-import:1X01")
      (libsource (lib "eagle-import") (part "PINHD-1X1"))
    )
    (comp (ref "JP208")
      (value "1")
      (footprint "eagle-import:1X01")
      (libsource (lib "eagle-import") (part "PINHD-1X1"))
    )
    (comp (ref "JP209")
      (value "1")
      (footprint "eagle-import:1X01")
      (libsource (lib "eagle-import") (part "PINHD-1X1"))
    )
    (comp (ref "JP210")
      (value "1")
      (footprint "eagle-import:1X01")
      (libsource (lib "eagle-import") (part "PINHD-1X1"))
    )
    (comp (ref "JP211")
      (value "1")
      (footprint "eagle-import:1X01")
      (libsource (lib "eagle-import") (part "PINHD-1X1"))
    )
    (comp (ref "JP212")
      (value "1")
      (footprint "eagle-import:1X01")
      (libsource (lib "eagle-import") (part "PINHD-1X1"))
    )
    (comp (ref "JP213")
      (value "1")
      (footprint "eagle-import:1X01")
      (libsource (lib "eagle-import") (part "PINHD-1X1"))
    )
    (comp (ref "JP214")
      (value "1")
      (footprint "eagle-import:1X01")
      (libsource (lib "eagle-import") (part "PINHD-1X1"))
    )
    (comp (ref "JP215")
      (value "1")
      (footprint "eagle-import:1X01")
      (libsource (lib "eagle-import") (part "PINHD-1X1"))
    )
    (comp (ref "JP216")
      (value "1")
      (footprint "eagle-import:1X01")
      (libsource (lib "eagle-import") (part "PINHD-1X1"))
    )
    (comp (ref "JP217")
      (value "1")
      (footprint "eagle-import:1X01")
      (libsource (lib "eagle-import") (part "PINHD-1X1"))
    )
    (comp (ref "JP218")
      (value "1")
      (footprint "eagle-import:1X01")
      (libsource (lib "eagle-import") (part "PINHD-1X1"))
    )
    (comp (ref "JP219")
      (value "1")
      (footprint "eagle-import:1X01")
      (libsource (lib "eagle-import") (part "PINHD-1X1"))
    )
    (comp (ref "JP220")
      (value "1")
      (footprint "eagle-import:1X01")
      (libsource (lib "eagle-import") (part "PINHD-1X1"))
    )
    (comp (ref "JP221")
      (value "1")
      (footprint "eagle-import:1X01")
      (libsource (lib "eagle-import") (part "PINHD-1X1"))
    )
    (comp (ref "JP222")
      (value "1")
      (footprint "eagle-import:1X01")
      (libsource (lib "eagle-import") (part "PINHD-1X1"))
    )
    (comp (ref "JP223")
      (value "1")
      (footprint "eagle-import:1X01")
      (libsource (lib "eagle-import") (part "PINHD-1X1"))
    )
    (comp (ref "JP224")
      (value "1")
      (footprint "eagle-import:1X01")
      (libsource (lib "eagle-import") (part "PINHD-1X1"))
    )
    (comp (ref "JP225")
      (value "1")
      (footprint "eagle-import:1X01")
      (libsource (lib "eagle-import") (part "PINHD-1X1"))
    )
    (comp (ref "JP226")
      (value "1")
      (footprint "eagle-import:1X01")
      (libsource (lib "eagle-import") (part "PINHD-1X1"))
    )
    (comp (ref "JP227")
      (value "1")
      (footprint "eagle-import:1X01")
      (libsource (lib "eagle-import") (part "PINHD-1X1"))
    )
    (comp (ref "JP228")
      (value "1")
      (footprint "eagle-import:1X01")
      (libsource (lib "eagle-import") (part "PINHD-1X1"))
    )
    (comp (ref "JP229")
      (value "1")
      (footprint "eagle-import:1X01")
      (libsource (lib "eagle-import") (part "PINHD-1X1"))
    )
    (comp (ref "JP230")
      (value "1")
      (footprint "eagle-import:1X01")
      (libsource (lib "eagle-import") (part "PINHD-1X1"))
    )
    (comp (ref "JP231")
      (value "1")
      (footprint "eagle-import:1X01")
      (libsource (lib "eagle-import") (part "PINHD-1X1"))
    )
    (comp (ref "JP232")
      (value "1")
      (footprint "eagle-import:1X01")
      (libsource (lib "eagle-import") (part "PINHD-1X1"))
    )
    (comp (ref "JP233")
      (value "1")
      (footprint "eagle-import:1X01")
      (libsource (lib "eagle-import") (part "PINHD-1X1"))
    )
    (comp (ref "JP234")
      (value "1")
      (footprint "eagle-import:1X01")
      (libsource (lib "eagle-import") (part "PINHD-1X1"))
    )
    (comp (ref "JP235")
      (value "1")
      (footprint "eagle-import:1X01")
      (libsource (lib "eagle-import") (part "PINHD-1X1"))
    )
    (comp (ref "JP236")
      (value "1")
      (footprint "eagle-import:1X01")
      (libsource (lib "eagle-import") (part "PINHD-1X1"))
    )
    (comp (ref "JP237")
      (value "1")
      (footprint "eagle-import:1X01")
      (libsource (lib "eagle-import") (part "PINHD-1X1"))
    )
    (comp (ref "JP238")
      (value "1")
      (footprint "eagle-import:1X01")
      (libsource (lib "eagle-import") (part "PINHD-1X1"))
    )
    (comp (ref "JP239")
      (value "1")
      (footprint "eagle-import:1X01")
      (libsource (lib "eagle-import") (part "PINHD-1X1"))
    )
    (comp (ref "JP240")
      (value "1")
      (footprint "eagle-import:1X01")
      (libsource (lib "eagle-import") (part "PINHD-1X1"))
    )
    (comp (ref "JP241")
      (value "1")
      (footprint "eagle-import:1X01")
      (libsource (lib "eagle-import") (part "PINHD-1X1"))
    )
    (comp (ref "JP242")
      (value "1")
      (footprint "eagle-import:1X01")
      (libsource (lib "eagle-import") (part "PINHD-1X1"))
    )
    (comp (ref "JP243")
      (value "1")
      (footprint "eagle-import:1X01")
      (libsource (lib "eagle-import") (part "PINHD-1X1"))
    )
    (comp (ref "JP244")
      (value "1")
      (footprint "eagle-import:1X01")
      (libsource (lib "eagle-import") (part "PINHD-1X1"))
    )
    (comp (ref "JP245")
      (value "1")
      (footprint "eagle-import:1X01")
      (libsource (lib "eagle-import") (part "PINHD-1X1"))
    )
    (comp (ref "JP246")
      (value "1")
      (footprint "eagle-import:1X01")
      (libsource (lib "eagle-import") (part "PINHD-1X1"))
    )
    (comp (ref "JP247")
      (value "1")
      (footprint "eagle-import:1X01")
      (libsource (lib "eagle-import") (part "PINHD-1X1"))
    )
    (comp (ref "JP248")
      (value "1")
      (footprint "eagle-import:1X01")
      (libsource (lib "eagle-import") (part "PINHD-1X1"))
    )
    (comp (ref "JP249")
      (value "1")
      (footprint "eagle-import:1X01")
      (libsource (lib "eagle-import") (part "PINHD-1X1"))
    )
    (comp (ref "JP250")
      (value "1")
      (footprint "eagle-import:1X01")
      (libsource (lib "eagle-import") (part "PINHD-1X1"))
    )
    (comp (ref "JP251")
      (value "1")
      (footprint "eagle-import:1X01")
      (libsource (lib "eagle-import") (part "PINHD-1X1"))
    )
    (comp (ref "JP252")
      (value "1")
      (footprint "eagle-import:1X01")
      (libsource (lib "eagle-import") (part "PINHD-1X1"))
    )
    (comp (ref "JP253")
      (value "1")
      (footprint "eagle-import:1X01")
      (libsource (lib "eagle-import") (part "PINHD-1X1"))
    )
    (comp (ref "JP254")
      (value "1")
      (footprint "eagle-import:1X01")
      (libsource (lib "eagle-import") (part "PINHD-1X1"))
    )
    (comp (ref "JP255")
      (value "1")
      (footprint "eagle-import:1X01")
      (libsource (lib "eagle-import") (part "PINHD-1X1"))
    )
    (comp (ref "JP256")
      (value "1")
      (footprint "eagle-import:1X01")
      (libsource (lib "eagle-import") (part "PINHD-1X1"))
    )
    (comp (ref "JP257")
      (value "1")
      (footprint "eagle-import:1X01")
      (libsource (lib "eagle-import") (part "PINHD-1X1"))
    )
    (comp (ref "JP258")
      (value "1")
      (footprint "eagle-import:1X01")
      (libsource (lib "eagle-import") (part "PINHD-1X1"))
    )
    (comp (ref "JP259")
      (value "1")
      (footprint "eagle-import:1X01")
      (libsource (lib "eagle-import") (part "PINHD-1X1"))
    )
    (comp (ref "JP260")
      (value "1")
      (footprint "eagle-import:1X01")
      (libsource (lib "eagle-import") (part "PINHD-1X1"))
    )
    (comp (ref "JP261")
      (value "1")
      (footprint "eagle-import:1X01")
      (libsource (lib "eagle-import") (part "PINHD-1X1"))
    )
    (comp (ref "JP262")
      (value "1")
      (footprint "eagle-import:1X01")
      (libsource (lib "eagle-import") (part "PINHD-1X1"))
    )
    (comp (ref "JP263")
      (value "1")
      (footprint "eagle-import:1X01")
      (libsource (lib "eagle-import") (part "PINHD-1X1"))
    )
    (comp (ref "JP264")
      (value "1")
      (footprint "eagle-import:1X01")
      (libsource (lib "eagle-import") (part "PINHD-1X1"))
    )
    (comp (ref "JP265")
      (value "1")
      (footprint "eagle-import:1X01")
      (libsource (lib "eagle-import") (part "PINHD-1X1"))
    )
    (comp (ref "JP266")
      (value "1")
      (footprint "eagle-import:1X01")
      (libsource (lib "eagle-import") (part "PINHD-1X1"))
    )
    (comp (ref "JP267")
      (value "1")
      (footprint "eagle-import:1X01")
      (libsource (lib "eagle-import") (part "PINHD-1X1"))
    )
    (comp (ref "JP268")
      (value "1")
      (footprint "eagle-import:1X01")
      (libsource (lib "eagle-import") (part "PINHD-1X1"))
    )
    (comp (ref "JP269")
      (value "1")
      (footprint "eagle-import:1X01")
      (libsource (lib "eagle-import") (part "PINHD-1X1"))
    )
    (comp (ref "JP270")
      (value "1")
      (footprint "eagle-import:1X01")
      (libsource (lib "eagle-import") (part "PINHD-1X1"))
    )
    (comp (ref "JP271")
      (value "1")
      (footprint "eagle-import:1X01")
      (libsource (lib "eagle-import") (part "PINHD-1X1"))
    )
    (comp (ref "JP272")
      (value "1")
      (footprint "eagle-import:1X01")
      (libsource (lib "eagle-import") (part "PINHD-1X1"))
    )
    (comp (ref "JP273")
      (value "1")
      (footprint "eagle-import:1X01")
      (libsource (lib "eagle-import") (part "PINHD-1X1"))
    )
    (comp (ref "JP274")
      (value "1")
      (footprint "eagle-import:1X01")
      (libsource (lib "eagle-import") (part "PINHD-1X1"))
    )
    (comp (ref "JP275")
      (value "1")
      (footprint "eagle-import:1X01")
      (libsource (lib "eagle-import") (part "PINHD-1X1"))
    )
    (comp (ref "JP276")
      (value "1")
      (footprint "eagle-import:1X01")
      (libsource (lib "eagle-import") (part "PINHD-1X1"))
    )
    (comp (ref "JP277")
      (value "1")
      (footprint "eagle-import:1X01")
      (libsource (lib "eagle-import") (part "PINHD-1X1"))
    )
    (comp (ref "JP278")
      (value "1")
      (footprint "eagle-import:1X01")
      (libsource (lib "eagle-import") (part "PINHD-1X1"))
    )
    (comp (ref "JP279")
      (value "1")
      (footprint "eagle-import:1X01")
      (libsource (lib "eagle-import") (part "PINHD-1X1"))
    )
    (comp (ref "JP280")
      (value "1")
      (footprint "eagle-import:1X01")
      (libsource (lib "eagle-import") (part "PINHD-1X1"))
    )
    (comp (ref "JP281")
      (value "1")
      (footprint "eagle-import:1X01")
      (libsource (lib "eagle-import") (part "PINHD-1X1"))
    )
    (comp (ref "JP282")
      (value "1")
      (footprint "eagle-import:1X01")
      (libsource (lib "eagle-import") (part "PINHD-1X1"))
    )
    (comp (ref "JP283")
      (value "1")
      (footprint "eagle-import:1X01")
      (libsource (lib "eagle-import") (part "PINHD-1X1"))
    )
    (comp (ref "JP284")
      (value "1")
      (footprint "eagle-import:1X01")
      (libsource (lib "eagle-import") (part "PINHD-1X1"))
    )
    (comp (ref "JP285")
      (value "1")
      (footprint "eagle-import:1X01")
      (libsource (lib "eagle-import") (part "PINHD-1X1"))
    )
    (comp (ref "JP286")
      (value "1")
      (footprint "eagle-import:1X01")
      (libsource (lib "eagle-import") (part "PINHD-1X1"))
    )
    (comp (ref "JP287")
      (value "1")
      (footprint "eagle-import:1X01")
      (libsource (lib "eagle-import") (part "PINHD-1X1"))
    )
    (comp (ref "JP288")
      (value "1")
      (footprint "eagle-import:1X01")
      (libsource (lib "eagle-import") (part "PINHD-1X1"))
    )
    (comp (ref "JP289")
      (value "1")
      (footprint "eagle-import:1X01")
      (libsource (lib "eagle-import") (part "PINHD-1X1"))
    )
    (comp (ref "JP290")
      (value "1")
      (footprint "eagle-import:1X01")
      (libsource (lib "eagle-import") (part "PINHD-1X1"))
    )
    (comp (ref "JP291")
      (value "1")
      (footprint "eagle-import:1X01")
      (libsource (lib "eagle-import") (part "PINHD-1X1"))
    )
    (comp (ref "JP292")
      (value "1")
      (footprint "eagle-import:1X01")
      (libsource (lib "eagle-import") (part "PINHD-1X1"))
    )
    (comp (ref "JP293")
      (value "1")
      (footprint "eagle-import:1X01")
      (libsource (lib "eagle-import") (part "PINHD-1X1"))
    )
    (comp (ref "JP294")
      (value "1")
      (footprint "eagle-import:1X01")
      (libsource (lib "eagle-import") (part "PINHD-1X1"))
    )
    (comp (ref "JP295")
      (value "1")
      (footprint "eagle-import:1X01")
      (libsource (lib "eagle-import") (part "PINHD-1X1"))
    )
    (comp (ref "JP296")
      (value "1")
      (footprint "eagle-import:1X01")
      (libsource (lib "eagle-import") (part "PINHD-1X1"))
    )
    (comp (ref "JP297")
      (value "1")
      (footprint "eagle-import:1X01")
      (libsource (lib "eagle-import") (part "PINHD-1X1"))
    )
    (comp (ref "JP298")
      (value "1")
      (footprint "eagle-import:1X01")
      (libsource (lib "eagle-import") (part "PINHD-1X1"))
    )
    (comp (ref "JP299")
      (value "1")
      (footprint "eagle-import:1X01")
      (libsource (lib "eagle-import") (part "PINHD-1X1"))
    )
    (comp (ref "JP300")
      (value "1")
      (footprint "eagle-import:1X01")
      (libsource (lib "eagle-import") (part "PINHD-1X1"))
    )
    (comp (ref "JP301")
      (value "1")
      (footprint "eagle-import:1X01")
      (libsource (lib "eagle-import") (part "PINHD-1X1"))
    )
    (comp (ref "JP302")
      (value "1")
      (footprint "eagle-import:1X01")
      (libsource (lib "eagle-import") (part "PINHD-1X1"))
    )
    (comp (ref "JP303")
      (value "1")
      (footprint "eagle-import:1X01")
      (libsource (lib "eagle-import") (part "PINHD-1X1"))
    )
    (comp (ref "JP304")
      (value "1")
      (footprint "eagle-import:1X01")
      (libsource (lib "eagle-import") (part "PINHD-1X1"))
    )
    (comp (ref "JP305")
      (value "1")
      (footprint "eagle-import:1X01")
      (libsource (lib "eagle-import") (part "PINHD-1X1"))
    )
    (comp (ref "JP306")
      (value "1")
      (footprint "eagle-import:1X01")
      (libsource (lib "eagle-import") (part "PINHD-1X1"))
    )
    (comp (ref "JP307")
      (value "1")
      (footprint "eagle-import:1X01")
      (libsource (lib "eagle-import") (part "PINHD-1X1"))
    )
    (comp (ref "JP308")
      (value "1")
      (footprint "eagle-import:1X01")
      (libsource (lib "eagle-import") (part "PINHD-1X1"))
    )
    (comp (ref "JP309")
      (value "1")
      (footprint "eagle-import:1X01")
      (libsource (lib "eagle-import") (part "PINHD-1X1"))
    )
    (comp (ref "JP310")
      (value "1")
      (footprint "eagle-import:1X01")
      (libsource (lib "eagle-import") (part "PINHD-1X1"))
    )
    (comp (ref "JP311")
      (value "1")
      (footprint "eagle-import:1X01")
      (libsource (lib "eagle-import") (part "PINHD-1X1"))
    )
    (comp (ref "JP312")
      (value "1")
      (footprint "eagle-import:1X01")
      (libsource (lib "eagle-import") (part "PINHD-1X1"))
    )
    (comp (ref "JP313")
      (value "1")
      (footprint "eagle-import:1X01")
      (libsource (lib "eagle-import") (part "PINHD-1X1"))
    )
    (comp (ref "JP314")
      (value "1")
      (footprint "eagle-import:1X01")
      (libsource (lib "eagle-import") (part "PINHD-1X1"))
    )
    (comp (ref "JP315")
      (value "1")
      (footprint "eagle-import:1X01")
      (libsource (lib "eagle-import") (part "PINHD-1X1"))
    )
    (comp (ref "JP316")
      (value "1")
      (footprint "eagle-import:1X01")
      (libsource (lib "eagle-import") (part "PINHD-1X1"))
    )
    (comp (ref "JP317")
      (value "1")
      (footprint "eagle-import:1X01")
      (libsource (lib "eagle-import") (part "PINHD-1X1"))
    )
    (comp (ref "JP318")
      (value "1")
      (footprint "eagle-import:1X01")
      (libsource (lib "eagle-import") (part "PINHD-1X1"))
    )
    (comp (ref "JP319")
      (value "1")
      (footprint "eagle-import:1X01")
      (libsource (lib "eagle-import") (part "PINHD-1X1"))
    )
    (comp (ref "JP320")
      (value "1")
      (footprint "eagle-import:1X01")
      (libsource (lib "eagle-import") (part "PINHD-1X1"))
    )
    (comp (ref "JP321")
      (value "1")
      (footprint "eagle-import:1X01")
      (libsource (lib "eagle-import") (part "PINHD-1X1"))
    )
    (comp (ref "JP322")
      (value "1")
      (footprint "eagle-import:1X01")
      (libsource (lib "eagle-import") (part "PINHD-1X1"))
    )
    (comp (ref "JP323")
      (value "1")
      (footprint "eagle-import:1X01")
      (libsource (lib "eagle-import") (part "PINHD-1X1"))
    )
    (comp (ref "JP324")
      (value "1")
      (footprint "eagle-import:1X01")
      (libsource (lib "eagle-import") (part "PINHD-1X1"))
    )
    (comp (ref "JP325")
      (value "1")
      (footprint "eagle-import:1X01")
      (libsource (lib "eagle-import") (part "PINHD-1X1"))
    )
    (comp (ref "JP326")
      (value "1")
      (footprint "eagle-import:1X01")
      (libsource (lib "eagle-import") (part "PINHD-1X1"))
    )
    (comp (ref "JP327")
      (value "1")
      (footprint "eagle-import:1X01")
      (libsource (lib "eagle-import") (part "PINHD-1X1"))
    )
    (comp (ref "JP328")
      (value "1")
      (footprint "eagle-import:1X01")
      (libsource (lib "eagle-import") (part "PINHD-1X1"))
    )
    (comp (ref "JP329")
      (value "1")
      (footprint "eagle-import:1X01")
      (libsource (lib "eagle-import") (part "PINHD-1X1"))
    )
    (comp (ref "JP330")
      (value "1")
      (footprint "eagle-import:1X01")
      (libsource (lib "eagle-import") (part "PINHD-1X1"))
    )
    (comp (ref "JP331")
      (value "1")
      (footprint "eagle-import:1X01")
      (libsource (lib "eagle-import") (part "PINHD-1X1"))
    )
    (comp (ref "JP332")
      (value "1")
      (footprint "eagle-import:1X01")
      (libsource (lib "eagle-import") (part "PINHD-1X1"))
    )
    (comp (ref "JP333")
      (value "1")
      (footprint "eagle-import:1X01")
      (libsource (lib "eagle-import") (part "PINHD-1X1"))
    )
    (comp (ref "JP334")
      (value "1")
      (footprint "eagle-import:1X01")
      (libsource (lib "eagle-import") (part "PINHD-1X1"))
    )
    (comp (ref "JP335")
      (value "1")
      (footprint "eagle-import:1X01")
      (libsource (lib "eagle-import") (part "PINHD-1X1"))
    )
    (comp (ref "JP336")
      (value "1")
      (footprint "eagle-import:1X01")
      (libsource (lib "eagle-import") (part "PINHD-1X1"))
    )
    (comp (ref "JP337")
      (value "1")
      (footprint "eagle-import:1X01")
      (libsource (lib "eagle-import") (part "PINHD-1X1"))
    )
    (comp (ref "JP338")
      (value "1")
      (footprint "eagle-import:1X01")
      (libsource (lib "eagle-import") (part "PINHD-1X1"))
    )
    (comp (ref "JP339")
      (value "1")
      (footprint "eagle-import:1X01")
      (libsource (lib "eagle-import") (part "PINHD-1X1"))
    )
    (comp (ref "JP340")
      (value "1")
      (footprint "eagle-import:1X01")
      (libsource (lib "eagle-import") (part "PINHD-1X1"))
    )
    (comp (ref "JP341")
      (value "1")
      (footprint "eagle-import:1X01")
      (libsource (lib "eagle-import") (part "PINHD-1X1"))
    )
    (comp (ref "JP342")
      (value "1")
      (footprint "eagle-import:1X01")
      (libsource (lib "eagle-import") (part "PINHD-1X1"))
    )
    (comp (ref "C1")
      (value "0.1uF")
      (footprint "eagle-import:RESC0402_N")
      (libsource (lib "eagle-import") (part "CAPACITOR_0402_N"))
    )
    (comp (ref "C14")
      (value "0.1uF")
      (footprint "eagle-import:RESC0402_N")
      (libsource (lib "eagle-import") (part "CAPACITOR_0402_N"))
    )
    (comp (ref "C15")
      (value "0.1uF")
      (footprint "eagle-import:RESC0402_N")
      (libsource (lib "eagle-import") (part "CAPACITOR_0402_N"))
    )
    (comp (ref "C16")
      (value "0.1uF")
      (footprint "eagle-import:RESC0402_N")
      (libsource (lib "eagle-import") (part "CAPACITOR_0402_N"))
    )
    (comp (ref "C17")
      (value "0.1uF")
      (footprint "eagle-import:RESC0402_N")
      (libsource (lib "eagle-import") (part "CAPACITOR_0402_N"))
    )
    (comp (ref "C18")
      (value "0.1uF")
      (footprint "eagle-import:RESC0402_N")
      (libsource (lib "eagle-import") (part "CAPACITOR_0402_N"))
    )
    (comp (ref "C19")
      (value "0.1uF")
      (footprint "eagle-import:RESC0402_N")
      (libsource (lib "eagle-import") (part "CAPACITOR_0402_N"))
    )
    (comp (ref "C20")
      (value "0.1uF")
      (footprint "eagle-import:RESC0402_N")
      (libsource (lib "eagle-import") (part "CAPACITOR_0402_N"))
    )
    (comp (ref "C21")
      (value "0.1uF")
      (footprint "eagle-import:RESC0402_N")
      (libsource (lib "eagle-import") (part "CAPACITOR_0402_N"))
    )
    (comp (ref "C22")
      (value "0.1uF")
      (footprint "eagle-import:RESC0402_N")
      (libsource (lib "eagle-import") (part "CAPACITOR_0402_N"))
    )
    (comp (ref "C23")
      (value "0.1uF")
      (footprint "eagle-import:RESC0402_N")
      (libsource (lib "eagle-import") (part "CAPACITOR_0402_N"))
    )
    (comp (ref "C24")
      (value "0.1uF")
      (footprint "eagle-import:RESC0402_N")
      (libsource (lib "eagle-import") (part "CAPACITOR_0402_N"))
    )
    (comp (ref "C25")
      (value "0.1uF")
      (footprint "eagle-import:RESC0402_N")
      (libsource (lib "eagle-import") (part "CAPACITOR_0402_N"))
    )
    (comp (ref "C26")
      (value "0.1uF")
      (footprint "eagle-import:RESC0402_N")
      (libsource (lib "eagle-import") (part "CAPACITOR_0402_N"))
    )
    (comp (ref "IC1")
      (value "EP4CE30F23C6N")
      (footprint "eagle-import:BGA484C100P22X22_2300X2300X240")
      (fields (field (name "MOUSER_PART_NUMBER") "989-EP4CE30F23C6N"))
      (libsource (lib "eagle-import") (part "EP4CE30F23C6N"))
    )
    (comp (ref "IC2")
      (value "EPCQ16ASI8N")
      (footprint "eagle-import:SOIC127P600X175-8N")
      (fields (field (name "MOUSER_PART_NUMBER") "989-EPCQ16ASI8N"))
      (libsource (lib "eagle-import") (part "EPCQ16ASI8N"))
    )
    (comp (ref "J1")
      (value "2x5")
      (footprint "eagle-import:2X5-SHROUDED")
      (libsource (lib "eagle-import") (part "CONN_05X2SHD"))
    )
    (comp (ref "JP3")
      (value "1x8")
      (footprint "eagle-import:1X08")
      (libsource (lib "eagle-import") (part "PINHD-1X8"))
    )
    (comp (ref "LED33")
      (value "red")
      (footprint "eagle-import:CHIP-LED0603")
      (libsource (lib "eagle-import") (part "LEDCHIP-LED0603"))
    )
    (comp (ref "LED34")
      (value "red")
      (footprint "eagle-import:CHIP-LED0603")
      (libsource (lib "eagle-import") (part "LEDCHIP-LED0603"))
    )
    (comp (ref "LED35")
      (value "red")
      (footprint "eagle-import:CHIP-LED0603")
      (libsource (lib "eagle-import") (part "LEDCHIP-LED0603"))
    )
    (comp (ref "LED36")
      (value "red")
      (footprint "eagle-import:CHIP-LED0603")
      (libsource (lib "eagle-import") (part "LEDCHIP-LED0603"))
    )
    (comp (ref "LED37")
      (value "red")
      (footprint "eagle-import:CHIP-LED0603")
      (libsource (lib "eagle-import") (part "LEDCHIP-LED0603"))
    )
    (comp (ref "LED38")
      (value "red")
      (footprint "eagle-import:CHIP-LED0603")
      (libsource (lib "eagle-import") (part "LEDCHIP-LED0603"))
    )
    (comp (ref "LED39")
      (value "red")
      (footprint "eagle-import:CHIP-LED0603")
      (libsource (lib "eagle-import") (part "LEDCHIP-LED0603"))
    )
    (comp (ref "LED40")
      (value "red")
      (footprint "eagle-import:CHIP-LED0603")
      (libsource (lib "eagle-import") (part "LEDCHIP-LED0603"))
    )
    (comp (ref "R1")
      (value "10k")
      (footprint "eagle-import:RES-0402")
      (libsource (lib "eagle-import") (part "RES-0402"))
    )
    (comp (ref "R2")
      (value "10k")
      (footprint "eagle-import:RES-0402")
      (libsource (lib "eagle-import") (part "RES-0402"))
    )
    (comp (ref "R3")
      (value "10k")
      (footprint "eagle-import:RES-0402")
      (libsource (lib "eagle-import") (part "RES-0402"))
    )
    (comp (ref "R4")
      (value "0")
      (footprint "eagle-import:RES-0402")
      (libsource (lib "eagle-import") (part "RES-0402"))
    )
    (comp (ref "R5")
      (value "10k")
      (footprint "eagle-import:RES-0402")
      (libsource (lib "eagle-import") (part "RES-0402"))
    )
    (comp (ref "R6")
      (value "10k")
      (footprint "eagle-import:RES-0402")
      (libsource (lib "eagle-import") (part "RES-0402"))
    )
    (comp (ref "R7")
      (value "10k")
      (footprint "eagle-import:RES-0402")
      (libsource (lib "eagle-import") (part "RES-0402"))
    )
    (comp (ref "R8")
      (value "10k")
      (footprint "eagle-import:RES-0402")
      (libsource (lib "eagle-import") (part "RES-0402"))
    )
    (comp (ref "R9")
      (value "10k")
      (footprint "eagle-import:RES-0402")
      (libsource (lib "eagle-import") (part "RES-0402"))
    )
    (comp (ref "R17")
      (value "0")
      (footprint "eagle-import:RES-0402")
      (libsource (lib "eagle-import") (part "RES-0402"))
    )
    (comp (ref "R18")
      (value "0")
      (footprint "eagle-import:RES-0402")
      (libsource (lib "eagle-import") (part "RES-0402"))
    )
    (comp (ref "R19")
      (value "0")
      (footprint "eagle-import:RES-0402")
      (libsource (lib "eagle-import") (part "RES-0402"))
    )
    (comp (ref "R20")
      (value "0")
      (footprint "eagle-import:RES-0402")
      (libsource (lib "eagle-import") (part "RES-0402"))
    )
    (comp (ref "R38")
      (value "1k")
      (footprint "eagle-import:RES-0402")
      (libsource (lib "eagle-import") (part "RES-0402"))
    )
    (comp (ref "R39")
      (value "1k")
      (footprint "eagle-import:RES-0402")
      (libsource (lib "eagle-import") (part "RES-0402"))
    )
    (comp (ref "R40")
      (value "1k")
      (footprint "eagle-import:RES-0402")
      (libsource (lib "eagle-import") (part "RES-0402"))
    )
    (comp (ref "R41")
      (value "1k")
      (footprint "eagle-import:RES-0402")
      (libsource (lib "eagle-import") (part "RES-0402"))
    )
    (comp (ref "R42")
      (value "1k")
      (footprint "eagle-import:RES-0402")
      (libsource (lib "eagle-import") (part "RES-0402"))
    )
    (comp (ref "R43")
      (value "1k")
      (footprint "eagle-import:RES-0402")
      (libsource (lib "eagle-import") (part "RES-0402"))
    )
    (comp (ref "R44")
      (value "1k")
      (footprint "eagle-import:RES-0402")
      (libsource (lib "eagle-import") (part "RES-0402"))
    )
    (comp (ref "R45")
      (value "1k")
      (footprint "eagle-import:RES-0402")
      (libsource (lib "eagle-import") (part "RES-0402"))
    )
    (comp (ref "SW1")
      (value "SKQGADE010")
      (footprint "eagle-import:SW4-SMD-5.2X5.2X1.5MM")
      (libsource (lib "eagle-import") (part "SMD-BUTTON(4P-5.2X5.2X1.5MM-SKQGADE010)-SKQGADE010"))
    )
    (comp (ref "SW2")
      (value "SKQGADE010")
      (footprint "eagle-import:SW4-SMD-5.2X5.2X1.5MM")
      (libsource (lib "eagle-import") (part "SMD-BUTTON(4P-5.2X5.2X1.5MM-SKQGADE010)-SKQGADE010"))
    )
    (comp (ref "Y1")
      (value "OSCILLATORSMD-5X3")
      (footprint "eagle-import:OSCILLATOR-SMD-5X3.2")
      (fields (field (name "LCSC") "C19725359"))
      (libsource (lib "eagle-import") (part "OSCILLATORSMD-5X3"))
    )
  )
  (nets
    (net (code "1") (name "1V2") (class "Default")
      (node (ref "C4") (pin "2") (pinfunction "2_2") (pintype "passive"))
      (node (ref "C5") (pin "2") (pinfunction "2_2") (pintype "passive"))
      (node (ref "JP3") (pin "7") (pinfunction "7_7") (pintype "passive"))
      (node (ref "R18") (pin "P$1") (pinfunction "P$1_P$1") (pintype "bidirectional"))
      (node (ref "R19") (pin "P$1") (pinfunction "P$1_P$1") (pintype "bidirectional"))
      (node (ref "U3") (pin "P$1") (pinfunction "VOUT_P$1") (pintype "bidirectional"))
      (node (ref "U3") (pin "P$3") (pinfunction "VOUT_P$3") (pintype "bidirectional"))
    )
    (net (code "2") (name "2V5") (class "Default")
      (node (ref "C2") (pin "2") (pinfunction "2_2") (pintype "passive"))
      (node (ref "C3") (pin "2") (pinfunction "2_2") (pintype "passive"))
      (node (ref "JP3") (pin "5") (pinfunction "5_5") (pintype "passive"))
      (node (ref "R17") (pin "P$1") (pinfunction "P$1_P$1") (pintype "bidirectional"))
      (node (ref "R20") (pin "P$1") (pinfunction "P$1_P$1") (pintype "bidirectional"))
      (node (ref "R39") (pin "P$1") (pinfunction "P$1_P$1") (pintype "bidirectional"))
      (node (ref "U2") (pin "P$1") (pinfunction "VOUT_P$1") (pintype "bidirectional"))
      (node (ref "U2") (pin "P$3") (pinfunction "VOUT_P$3") (pintype "bidirectional"))
    )
    (net (code "3") (name "3V3") (class "Default")
      (node (ref "C1") (pin "2") (pinfunction "2_2") (pintype "passive"))
      (node (ref "C12") (pin "2") (pinfunction "2_2") (pintype "passive"))
      (node (ref "C13") (pin "2") (pinfunction "2_2") (pintype "passive"))
      (node (ref "C14") (pin "2") (pinfunction "2_2") (pintype "passive"))
      (node (ref "C8") (pin "2") (pinfunction "2_2") (pintype "passive"))
      (node (ref "C9") (pin "2") (pinfunction "2_2") (pintype "passive"))
      (node (ref "IC2") (pin "3") (pinfunction "DATA2_3") (pintype "bidirectional"))
      (node (ref "IC2") (pin "7") (pinfunction "DATA3_7") (pintype "bidirectional"))
      (node (ref "IC2") (pin "8") (pinfunction "VCC_8") (pintype "bidirectional"))
      (node (ref "J1") (pin "4") (pinfunction "4_4") (pintype "passive"))
      (node (ref "JP3") (pin "3") (pinfunction "3_3") (pintype "passive"))
      (node (ref "R1") (pin "P$2") (pinfunction "P$2_P$2") (pintype "bidirectional"))
      (node (ref "R2") (pin "P$2") (pinfunction "P$2_P$2") (pintype "bidirectional"))
      (node (ref "R3") (pin "P$2") (pinfunction "P$2_P$2") (pintype "bidirectional"))
      (node (ref "R38") (pin "P$1") (pinfunction "P$1_P$1") (pintype "bidirectional"))
      (node (ref "R5") (pin "P$2") (pinfunction "P$2_P$2") (pintype "bidirectional"))
      (node (ref "R7") (pin "P$2") (pinfunction "P$2_P$2") (pintype "bidirectional"))
      (node (ref "U1") (pin "P$1") (pinfunction "VOUT_P$1") (pintype "bidirectional"))
      (node (ref "U1") (pin "P$3") (pinfunction "VOUT_P$3") (pintype "bidirectional"))
      (node (ref "U3") (pin "P$4") (pinfunction "VIN_P$4") (pintype "bidirectional"))
      (node (ref "Y1") (pin "4") (pinfunction "VCC_4") (pintype "bidirectional"))
    )
    (net (code "4") (name "5V") (class "Default")
      (node (ref "C10") (pin "2") (pinfunction "2_2") (pintype "passive"))
      (node (ref "C11") (pin "2") (pinfunction "2_2") (pintype "passive"))
      (node (ref "C6") (pin "2") (pinfunction "2_2") (pintype "passive"))
      (node (ref "C7") (pin "2") (pinfunction "2_2") (pintype "passive"))
      (node (ref "JP3") (pin "1") (pinfunction "1_1") (pintype "passive"))
      (node (ref "U1") (pin "P$4") (pinfunction "VIN_P$4") (pintype "bidirectional"))
      (node (ref "U2") (pin "P$4") (pinfunction "VIN_P$4") (pintype "bidirectional"))
    )
    (net (code "5") (name "ASDO") (class "Default")
      (node (ref "IC1") (pin "D1") (pinfunction "IO_52_D1") (pintype "bidirectional"))
      (node (ref "IC2") (pin "5") (pinfunction "DATA0_5") (pintype "bidirectional"))
      (node (ref "JP39") (pin "1") (pinfunction "1_1") (pintype "passive"))
    )
    (net (code "6") (name "CLK1") (class "Default")
      (node (ref "IC1") (pin "G1") (pinfunction "CLK1_G1") (pintype "bidirectional"))
      (node (ref "JP16") (pin "1") (pinfunction "1_1") (pintype "passive"))
      (node (ref "Y1") (pin "3") (pinfunction "OUT_3") (pintype "bidirectional"))
    )
    (net (code "7") (name "CLK2") (class "Default")
      (node (ref "IC1") (pin "T2") (pinfunction "CLK2_T2") (pintype "bidirectional"))
      (node (ref "JP18") (pin "1") (pinfunction "1_1") (pintype "passive"))
    )
    (net (code "8") (name "CLK3") (class "Default")
      (node (ref "IC1") (pin "T1") (pinfunction "CLK3_T1") (pintype "bidirectional"))
      (node (ref "JP17") (pin "1") (pinfunction "1_1") (pintype "passive"))
    )
    (net (code "9") (name "CLK4") (class "Default")
      (node (ref "IC1") (pin "G21") (pinfunction "CLK4_G21") (pintype "bidirectional"))
      (node (ref "JP19") (pin "1") (pinfunction "1_1") (pintype "passive"))
    )
    (net (code "10") (name "CLK5") (class "Default")
      (node (ref "IC1") (pin "G22") (pinfunction "CLK5_G22") (pintype "bidirectional"))
      (node (ref "JP20") (pin "1") (pinfunction "1_1") (pintype "passive"))
    )
    (net (code "11") (name "CLK6") (class "Default")
      (node (ref "IC1") (pin "T21") (pinfunction "CLK6_T21") (pintype "bidirectional"))
      (node (ref "JP22") (pin "1") (pinfunction "1_1") (pintype "passive"))
    )
    (net (code "12") (name "CLK7") (class "Default")
      (node (ref "IC1") (pin "T22") (pinfunction "CLK7_T22") (pintype "bidirectional"))
      (node (ref "JP21") (pin "1") (pinfunction "1_1") (pintype "passive"))
    )
    (net (code "13") (name "CLK8") (class "Default")
      (node (ref "IC1") (pin "A12") (pinfunction "CLK8_A12") (pintype "bidirectional"))
      (node (ref "JP23") (pin "1") (pinfunction "1_1") (pintype "passive"))
    )
    (net (code "14") (name "CLK9") (class "Default")
      (node (ref "IC1") (pin "B12") (pinfunction "CLK9_B12") (pintype "bidirectional"))
      (node (ref "JP24") (pin "1") (pinfunction "1_1") (pintype "passive"))
    )
    (net (code "15") (name "CLK10") (class "Default")
      (node (ref "IC1") (pin "A11") (pinfunction "CLK10_A11") (pintype "bidirectional"))
      (node (ref "JP26") (pin "1") (pinfunction "1_1") (pintype "passive"))
    )
    (net (code "16") (name "CLK11") (class "Default")
      (node (ref "IC1") (pin "B11") (pinfunction "CLK11_B11") (pintype "bidirectional"))
      (node (ref "JP25") (pin "1") (pinfunction "1_1") (pintype "passive"))
    )
    (net (code "17") (name "CLK12") (class "Default")
      (node (ref "IC1") (pin "AB12") (pinfunction "CLK12_AB12") (pintype "bidirectional"))
      (node (ref "JP27") (pin "1") (pinfunction "1_1") (pintype "passive"))
    )
    (net (code "18") (name "CLK13") (class "Default")
      (node (ref "IC1") (pin "AA12") (pinfunction "CLK13_AA12") (pintype "bidirectional"))
      (node (ref "JP28") (pin "1") (pinfunction "1_1") (pintype "passive"))
    )
    (net (code "19") (name "CLK14") (class "Default")
      (node (ref "IC1") (pin "AB11") (pinfunction "CLK14_AB11") (pintype "bidirectional"))
      (node (ref "JP30") (pin "1") (pinfunction "1_1") (pintype "passive"))
    )
    (net (code "20") (name "CLK15") (class "Default")
      (node (ref "IC1") (pin "AA11") (pinfunction "CLK15_AA11") (pintype "bidirectional"))
      (node (ref "JP29") (pin "1") (pinfunction "1_1") (pintype "passive"))
    )
    (net (code "21") (name "CONF_DONE") (class "Default")
      (node (ref "IC1") (pin "M18") (pinfunction "CONF_DONE_M18") (pintype "bidirectional"))
      (node (ref "R3") (pin "P$1") (pinfunction "P$1_P$1") (pintype "bidirectional"))
    )
    (net (code "22") (name "DATA0") (class "Default")
      (node (ref "IC1") (pin "K1") (pinfunction "IO_140_K1") (pintype "bidirectional"))
      (node (ref "IC2") (pin "2") (pinfunction "DATA1_2") (pintype "bidirectional"))
      (node (ref "JP113") (pin "1") (pinfunction "1_1") (pintype "passive"))
    )
    (net (code "23") (name "DCLK") (class "Default")
      (node (ref "IC1") (pin "K2") (pinfunction "DCLK_K2") (pintype "bidirectional"))
      (node (ref "IC2") (pin "6") (pinfunction "DCLK_6") (pintype "bidirectional"))
    )
    (net (code "24") (name "GND") (class "Default")
      (node (ref "C1") (pin "1") (pinfunction "1_1") (pintype "passive"))
      (node (ref "C10") (pin "1") (pinfunction "1_1") (pintype "passive"))
      (node (ref "C11") (pin "1") (pinfunction "1_1") (pintype "passive"))
      (node (ref "C12") (pin "1") (pinfunction "1_1") (pintype "passive"))
      (node (ref "C13") (pin "1") (pinfunction "1_1") (pintype "passive"))
      (node (ref "C14") (pin "1") (pinfunction "1_1") (pintype "passive"))
      (node (ref "C15") (pin "1") (pinfunction "1_1") (pintype "passive"))
      (node (ref "C16") (pin "1") (pinfunction "1_1") (pintype "passive"))
      (node (ref "C17") (pin "1") (pinfunction "1_1") (pintype "passive"))
      (node (ref "C18") (pin "1") (pinfunction "1_1") (pintype "passive"))
      (node (ref "C19") (pin "1") (pinfunction "1_1") (pintype "passive"))
      (node (ref "C2") (pin "1") (pinfunction "1_1") (pintype "passive"))
      (node (ref "C20") (pin "1") (pinfunction "1_1") (pintype "passive"))
      (node (ref "C21") (pin "1") (pinfunction "1_1") (pintype "passive"))
      (node (ref "C22") (pin "1") (pinfunction "1_1") (pintype "passive"))
      (node (ref "C23") (pin "1") (pinfunction "1_1") (pintype "passive"))
      (node (ref "C24") (pin "1") (pinfunction "1_1") (pintype "passive"))
      (node (ref "C25") (pin "1") (pinfunction "1_1") (pintype "passive"))
      (node (ref "C26") (pin "1") (pinfunction "1_1") (pintype "passive"))
      (node (ref "C3") (pin "1") (pinfunction "1_1") (pintype "passive"))
      (node (ref "C4") (pin "1") (pinfunction "1_1") (pintype "passive"))
      (node (ref "C5") (pin "1") (pinfunction "1_1") (pintype "passive"))
      (node (ref "C6") (pin "1") (pinfunction "1_1") (pintype "passive"))
      (node (ref "C7") (pin "1") (pinfunction "1_1") (pintype "passive"))
      (node (ref "C8") (pin "1") (pinfunction "1_1") (pintype "passive"))
      (node (ref "C9") (pin "1") (pinfunction "1_1") (pintype "passive"))
      (node (ref "IC1") (pin "A1") (pinfunction "GND_1_A1") (pintype "bidirectional"))
      (node (ref "IC1") (pin "A22") (pinfunction "GND_2_A22") (pintype "bidirectional"))
      (node (ref "IC1") (pin "AA2") (pinfunction "GND_63_AA2") (pintype "bidirectional"))
      (node (ref "IC1") (pin "AA22") (pinfunction "GND_64_AA22") (pintype "bidirectional"))
      (node (ref "IC1") (pin "AB1") (pinfunction "GND_65_AB1") (pintype "bidirectional"))
      (node (ref "IC1") (pin "AB22") (pinfunction "GND_67_AB22") (pintype "bidirectional"))
      (node (ref "IC1") (pin "AB6") (pinfunction "GND_66_AB6") (pintype "bidirectional"))
      (node (ref "IC1") (pin "C11") (pinfunction "GND_5_C11") (pintype "bidirectional"))
      (node (ref "IC1") (pin "C12") (pinfunction "GND_6_C12") (pintype "bidirectional"))
      (node (ref "IC1") (pin "C14") (pinfunction "GND_7_C14") (pintype "bidirectional"))
      (node (ref "IC1") (pin "C16") (pinfunction "GND_8_C16") (pintype "bidirectional"))
      (node (ref "IC1") (pin "C18") (pinfunction "GND_9_C18") (pintype "bidirectional"))
      (node (ref "IC1") (pin "C5") (pinfunction "GND_3_C5") (pintype "bidirectional"))
      (node (ref "IC1") (pin "C9") (pinfunction "GND_4_C9") (pintype "bidirectional"))
      (node (ref "IC1") (pin "D3") (pinfunction "GND_10_D3") (pintype "bidirectional"))
      (node (ref "IC1") (pin "D8") (pinfunction "GND_11_D8") (pintype "bidirectional"))
      (node (ref "IC1") (pin "E18") (pinfunction "GNDA2_E18") (pintype "bidirectional"))
      (node (ref "IC1") (pin "E20") (pinfunction "GND_12_E20") (pintype "bidirectional"))
      (node (ref "IC1") (pin "F12") (pinfunction "GND_14_F12") (pintype "bidirectional"))
      (node (ref "IC1") (pin "F3") (pinfunction "GND_13_F3") (pintype "bidirectional"))
      (node (ref "IC1") (pin "F5") (pinfunction "GNDA3_F5") (pintype "bidirectional"))
      (node (ref "IC1") (pin "G2") (pinfunction "GND_15_G2") (pintype "bidirectional"))
      (node (ref "IC1") (pin "G20") (pinfunction "GND_16_G20") (pintype "bidirectional"))
      (node (ref "IC1") (pin "H12") (pinfunction "GND_18_H12") (pintype "bidirectional"))
      (node (ref "IC1") (pin "H13") (pinfunction "GND_19_H13") (pintype "bidirectional"))
      (node (ref "IC1") (pin "H3") (pinfunction "GND_17_H3") (pintype "bidirectional"))
      (node (ref "IC1") (pin "J15") (pinfunction "GND_21_J15") (pintype "bidirectional"))
      (node (ref "IC1") (pin "J19") (pinfunction "GND_22_J19") (pintype "bidirectional"))
      (node (ref "IC1") (pin "J9") (pinfunction "GND_20_J9") (pintype "bidirectional"))
      (node (ref "IC1") (pin "K10") (pinfunction "GND_24_K10") (pintype "bidirectional"))
      (node (ref "IC1") (pin "K11") (pinfunction "GND_25_K11") (pintype "bidirectional"))
      (node (ref "IC1") (pin "K12") (pinfunction "GND_26_K12") (pintype "bidirectional"))
      (node (ref "IC1") (pin "K13") (pinfunction "GND_27_K13") (pintype "bidirectional"))
      (node (ref "IC1") (pin "K16") (pinfunction "GND_28_K16") (pintype "bidirectional"))
      (node (ref "IC1") (pin "K3") (pinfunction "GND_23_K3") (pintype "bidirectional"))
      (node (ref "IC1") (pin "L10") (pinfunction "GND_29_L10") (pintype "bidirectional"))
      (node (ref "IC1") (pin "L11") (pinfunction "GND_30_L11") (pintype "bidirectional"))
      (node (ref "IC1") (pin "L12") (pinfunction "GND_31_L12") (pintype "bidirectional"))
      (node (ref "IC1") (pin "L13") (pinfunction "GND_32_L13") (pintype "bidirectional"))
      (node (ref "IC1") (pin "L15") (pinfunction "GND_33_L15") (pintype "bidirectional"))
      (node (ref "IC1") (pin "L20") (pinfunction "GND_34_L20") (pintype "bidirectional"))
      (node (ref "IC1") (pin "M10") (pinfunction "GND_35_M10") (pintype "bidirectional"))
      (node (ref "IC1") (pin "M11") (pinfunction "GND_36_M11") (pintype "bidirectional"))
      (node (ref "IC1") (pin "M12") (pinfunction "GND_37_M12") (pintype "bidirectional"))
      (node (ref "IC1") (pin "M13") (pinfunction "GND_38_M13") (pintype "bidirectional"))
      (node (ref "IC1") (pin "N10") (pinfunction "GND_40_N10") (pintype "bidirectional"))
      (node (ref "IC1") (pin "N11") (pinfunction "GND_41_N11") (pintype "bidirectional"))
      (node (ref "IC1") (pin "N12") (pinfunction "GND_42_N12") (pintype "bidirectional"))
      (node (ref "IC1") (pin "N13") (pinfunction "GND_43_N13") (pintype "bidirectional"))
      (node (ref "IC1") (pin "N15") (pinfunction "GND_44_N15") (pintype "bidirectional"))
      (node (ref "IC1") (pin "N3") (pinfunction "GND_39_N3") (pintype "bidirectional"))
      (node (ref "IC1") (pin "P19") (pinfunction "GND_46_P19") (pintype "bidirectional"))
      (node (ref "IC1") (pin "P8") (pinfunction "GND_45_P8") (pintype "bidirectional"))
      (node (ref "IC1") (pin "R11") (pinfunction "GND_49_R11") (pintype "bidirectional"))
      (node (ref "IC1") (pin "R13") (pinfunction "GND_50_R13") (pintype "bidirectional"))
      (node (ref "IC1") (pin "R3") (pinfunction "GND_47_R3") (pintype "bidirectional"))
      (node (ref "IC1") (pin "R9") (pinfunction "GND_48_R9") (pintype "bidirectional"))
      (node (ref "IC1") (pin "T20") (pinfunction "GND_51_T20") (pintype "bidirectional"))
      (node (ref "IC1") (pin "U3") (pinfunction "GND_52_U3") (pintype "bidirectional"))
      (node (ref "IC1") (pin "U5") (pinfunction "GNDA1_U5") (pintype "bidirectional"))
      (node (ref "IC1") (pin "V18") (pinfunction "GNDA4_V18") (pintype "bidirectional"))
      (node (ref "IC1") (pin "V20") (pinfunction "GND_53_V20") (pintype "bidirectional"))
      (node (ref "IC1") (pin "W3") (pinfunction "GND_54_W3") (pintype "bidirectional"))
      (node (ref "IC1") (pin "Y11") (pinfunction "GND_57_Y11") (pintype "bidirectional"))
      (node (ref "IC1") (pin "Y12") (pinfunction "GND_58_Y12") (pintype "bidirectional"))
      (node (ref "IC1") (pin "Y15") (pinfunction "GND_59_Y15") (pintype "bidirectional"))
      (node (ref "IC1") (pin "Y16") (pinfunction "GND_60_Y16") (pintype "bidirectional"))
      (node (ref "IC1") (pin "Y18") (pinfunction "GND_61_Y18") (pintype "bidirectional"))
      (node (ref "IC1") (pin "Y20") (pinfunction "GND_62_Y20") (pintype "bidirectional"))
      (node (ref "IC1") (pin "Y5") (pinfunction "GND_55_Y5") (pintype "bidirectional"))
      (node (ref "IC1") (pin "Y9") (pinfunction "GND_56_Y9") (pintype "bidirectional"))
      (node (ref "IC2") (pin "4") (pinfunction "GND_4") (pintype "bidirectional"))
      (node (ref "J1") (pin "10") (pinfunction "10_10") (pintype "passive"))
      (node (ref "J1") (pin "2") (pinfunction "2_2") (pintype "passive"))
      (node (ref "JP1") (pin "1") (pinfunction "1_1") (pintype "passive"))
      (node (ref "JP13") (pin "1") (pinfunction "1_1") (pintype "passive"))
      (node (ref "JP138") (pin "1") (pinfunction "1_1") (pintype "passive"))
      (node (ref "JP149") (pin "1") (pinfunction "1_1") (pintype "passive"))
      (node (ref "JP165") (pin "1") (pinfunction "1_1") (pintype "passive"))
      (node (ref "JP166") (pin "1") (pinfunction "1_1") (pintype "passive"))
      (node (ref "JP177") (pin "1") (pinfunction "1_1") (pintype "passive"))
      (node (ref "JP193") (pin "1") (pinfunction "1_1") (pintype "passive"))
      (node (ref "JP3") (pin "2") (pinfunction "2_2") (pintype "passive"))
      (node (ref "JP3") (pin "4") (pinfunction "4_4") (pintype "passive"))
      (node (ref "JP3") (pin "6") (pinfunction "6_6") (pintype "passive"))
      (node (ref "JP3") (pin "8") (pinfunction "8_8") (pintype "passive"))
      (node (ref "JP31") (pin "1") (pinfunction "1_1") (pintype "passive"))
      (node (ref "JP45") (pin "1") (pinfunction "1_1") (pintype "passive"))
      (node (ref "JP46") (pin "1") (pinfunction "1_1") (pintype "passive"))
      (node (ref "JP57") (pin "1") (pinfunction "1_1") (pintype "passive"))
      (node (ref "JP73") (pin "1") (pinfunction "1_1") (pintype "passive"))
      (node (ref "LED33") (pin "C") (pinfunction "C_C") (pintype "passive"))
      (node (ref "LED34") (pin "C") (pinfunction "C_C") (pintype "passive"))
      (node (ref "LED35") (pin "C") (pinfunction "C_C") (pintype "passive"))
      (node (ref "LED36") (pin "C") (pinfunction "C_C") (pintype "passive"))
      (node (ref "LED37") (pin "C") (pinfunction "C_C") (pintype "passive"))
      (node (ref "LED38") (pin "C") (pinfunction "C_C") (pintype "passive"))
      (node (ref "LED39") (pin "C") (pinfunction "C_C") (pintype "passive"))
      (node (ref "LED40") (pin "C") (pinfunction "C_C") (pintype "passive"))
      (node (ref "R4") (pin "P$2") (pinfunction "P$2_P$2") (pintype "bidirectional"))
      (node (ref "R6") (pin "P$2") (pinfunction "P$2_P$2") (pintype "bidirectional"))
      (node (ref "R8") (pin "P$2") (pinfunction "P$2_P$2") (pintype "bidirectional"))
      (node (ref "R9") (pin "P$2") (pinfunction "P$2_P$2") (pintype "bidirectional"))
      (node (ref "SW1") (pin "4") (pinfunction "B1_4") (pintype "bidirectional"))
      (node (ref "SW2") (pin "4") (pinfunction "B1_4") (pintype "bidirectional"))
      (node (ref "U1") (pin "P$2") (pinfunction "GND/ADJ_P$2") (pintype "bidirectional"))
      (node (ref "U2") (pin "P$2") (pinfunction "GND/ADJ_P$2") (pintype "bidirectional"))
      (node (ref "U3") (pin "P$2") (pinfunction "GND/ADJ_P$2") (pintype "bidirectional"))
      (node (ref "Y1") (pin "2") (pinfunction "GND_2") (pintype "bidirectional"))
    )
    (net (code "25") (name "IO1") (class "Default")
      (node (ref "C15") (pin "2") (pinfunction "2_2") (pintype "passive"))
      (node (ref "IC1") (pin "A3") (pinfunction "IO_1_A3") (pintype "bidirectional"))
      (node (ref "JP74") (pin "1") (pinfunction "1_1") (pintype "passive"))
      (node (ref "R1") (pin "P$1") (pinfunction "P$1_P$1") (pintype "bidirectional"))
      (node (ref "R45") (pin "P$1") (pinfunction "P$1_P$1") (pintype "bidirectional"))
      (node (ref "SW2") (pin "2") (pinfunction "A1_2") (pintype "bidirectional"))
    )
    (net (code "26") (name "IO2") (class "Default")
      (node (ref "IC1") (pin "A4") (pinfunction "IO_2_A4") (pintype "bidirectional"))
      (node (ref "JP76") (pin "1") (pinfunction "1_1") (pintype "passive"))
      (node (ref "R44") (pin "P$1") (pinfunction "P$1_P$1") (pintype "bidirectional"))
    )
    (net (code "27") (name "IO3") (class "Default")
      (node (ref "IC1") (pin "A5") (pinfunction "IO_3_A5") (pintype "bidirectional"))
      (node (ref "JP75") (pin "1") (pinfunction "1_1") (pintype "passive"))
      (node (ref "R43") (pin "P$1") (pinfunction "P$1_P$1") (pintype "bidirectional"))
    )
    (net (code "28") (name "IO4") (class "Default")
      (node (ref "IC1") (pin "A6") (pinfunction "IO_4_A6") (pintype "bidirectional"))
      (node (ref "JP77") (pin "1") (pinfunction "1_1") (pintype "passive"))
      (node (ref "R42") (pin "P$1") (pinfunction "P$1_P$1") (pintype "bidirectional"))
    )
    (net (code "29") (name "IO5") (class "Default")
      (node (ref "IC1") (pin "A7") (pinfunction "IO_5_A7") (pintype "bidirectional"))
      (node (ref "JP78") (pin "1") (pinfunction "1_1") (pintype "passive"))
      (node (ref "R41") (pin "P$1") (pinfunction "P$1_P$1") (pintype "bidirectional"))
    )
    (net (code "30") (name "IO6") (class "Default")
      (node (ref "IC1") (pin "A8") (pinfunction "IO_6_A8") (pintype "bidirectional"))
      (node (ref "JP80") (pin "1") (pinfunction "1_1") (pintype "passive"))
      (node (ref "R40") (pin "P$1") (pinfunction "P$1_P$1") (pintype "bidirectional"))
    )
    (net (code "31") (name "IO7") (class "Default")
      (node (ref "IC1") (pin "A9") (pinfunction "IO_7_A9") (pintype "bidirectional"))
      (node (ref "JP79") (pin "1") (pinfunction "1_1") (pintype "passive"))
    )
    (net (code "32") (name "IO8") (class "Default")
      (node (ref "IC1") (pin "A10") (pinfunction "IO_8_A10") (pintype "bidirectional"))
      (node (ref "JP81") (pin "1") (pinfunction "1_1") (pintype "passive"))
    )
    (net (code "33") (name "IO9") (class "Default")
      (node (ref "IC1") (pin "A13") (pinfunction "IO_9_A13") (pintype "bidirectional"))
      (node (ref "JP82") (pin "1") (pinfunction "1_1") (pintype "passive"))
    )
    (net (code "34") (name "IO10") (class "Default")
      (node (ref "IC1") (pin "A14") (pinfunction "IO_10_A14") (pintype "bidirectional"))
      (node (ref "JP84") (pin "1") (pinfunction "1_1") (pintype "passive"))
    )
    (net (code "35") (name "IO11") (class "Default")
      (node (ref "IC1") (pin "A15") (pinfunction "IO_11_A15") (pintype "bidirectional"))
      (node (ref "JP83") (pin "1") (pinfunction "1_1") (pintype "passive"))
    )
    (net (code "36") (name "IO12") (class "Default")
      (node (ref "IC1") (pin "A16") (pinfunction "IO_12_A16") (pintype "bidirectional"))
      (node (ref "JP85") (pin "1") (pinfunction "1_1") (pintype "passive"))
    )
    (net (code "37") (name "IO13") (class "Default")
      (node (ref "IC1") (pin "A17") (pinfunction "IO_13_A17") (pintype "bidirectional"))
      (node (ref "JP86") (pin "1") (pinfunction "1_1") (pintype "passive"))
    )
    (net (code "38") (name "IO14") (class "Default")
      (node (ref "IC1") (pin "A18") (pinfunction "IO_14_A18") (pintype "bidirectional"))
      (node (ref "JP88") (pin "1") (pinfunction "1_1") (pintype "passive"))
    )
    (net (code "39") (name "IO15") (class "Default")
      (node (ref "IC1") (pin "A19") (pinfunction "IO_15_A19") (pintype "bidirectional"))
      (node (ref "JP87") (pin "1") (pinfunction "1_1") (pintype "passive"))
    )
    (net (code "40") (name "IO16") (class "Default")
      (node (ref "IC1") (pin "A20") (pinfunction "IO_16_A20") (pintype "bidirectional"))
      (node (ref "JP89") (pin "1") (pinfunction "1_1") (pintype "passive"))
    )
    (net (code "41") (name "IO17") (class "Default")
      (node (ref "IC1") (pin "B1") (pinfunction "IO_17_B1") (pintype "bidirectional"))
      (node (ref "JP90") (pin "1") (pinfunction "1_1") (pintype "passive"))
    )
    (net (code "42") (name "IO18") (class "Default")
      (node (ref "IC1") (pin "B2") (pinfunction "IO_18_B2") (pintype "bidirectional"))
      (node (ref "JP92") (pin "1") (pinfunction "1_1") (pintype "passive"))
    )
    (net (code "43") (name "IO19") (class "Default")
      (node (ref "IC1") (pin "B3") (pinfunction "IO_19_B3") (pintype "bidirectional"))
      (node (ref "JP91") (pin "1") (pinfunction "1_1") (pintype "passive"))
    )
    (net (code "44") (name "IO20") (class "Default")
      (node (ref "IC1") (pin "B4") (pinfunction "IO_20_B4") (pintype "bidirectional"))
      (node (ref "JP93") (pin "1") (pinfunction "1_1") (pintype "passive"))
    )
    (net (code "45") (name "IO21") (class "Default")
      (node (ref "IC1") (pin "B5") (pinfunction "IO_21_B5") (pintype "bidirectional"))
      (node (ref "JP94") (pin "1") (pinfunction "1_1") (pintype "passive"))
    )
    (net (code "46") (name "IO22") (class "Default")
      (node (ref "IC1") (pin "B6") (pinfunction "IO_22_B6") (pintype "bidirectional"))
      (node (ref "JP96") (pin "1") (pinfunction "1_1") (pintype "passive"))
    )
    (net (code "47") (name "IO23") (class "Default")
      (node (ref "IC1") (pin "B7") (pinfunction "IO_23_B7") (pintype "bidirectional"))
      (node (ref "JP95") (pin "1") (pinfunction "1_1") (pintype "passive"))
    )
    (net (code "48") (name "IO24") (class "Default")
      (node (ref "IC1") (pin "B8") (pinfunction "IO_24_B8") (pintype "bidirectional"))
      (node (ref "JP97") (pin "1") (pinfunction "1_1") (pintype "passive"))
    )
    (net (code "49") (name "IO25") (class "Default")
      (node (ref "IC1") (pin "B9") (pinfunction "IO_25_B9") (pintype "bidirectional"))
      (node (ref "JP98") (pin "1") (pinfunction "1_1") (pintype "passive"))
    )
    (net (code "50") (name "IO26") (class "Default")
      (node (ref "IC1") (pin "B10") (pinfunction "IO_26_B10") (pintype "bidirectional"))
      (node (ref "JP100") (pin "1") (pinfunction "1_1") (pintype "passive"))
    )
    (net (code "51") (name "IO27") (class "Default")
      (node (ref "IC1") (pin "B13") (pinfunction "IO_27_B13") (pintype "bidirectional"))
      (node (ref "JP99") (pin "1") (pinfunction "1_1") (pintype "passive"))
    )
    (net (code "52") (name "IO28") (class "Default")
      (node (ref "IC1") (pin "B14") (pinfunction "IO_28_B14") (pintype "bidirectional"))
      (node (ref "JP101") (pin "1") (pinfunction "1_1") (pintype "passive"))
    )
    (net (code "53") (name "IO29") (class "Default")
      (node (ref "IC1") (pin "B15") (pinfunction "IO_29_B15") (pintype "bidirectional"))
      (node (ref "JP102") (pin "1") (pinfunction "1_1") (pintype "passive"))
    )
    (net (code "54") (name "IO30") (class "Default")
      (node (ref "IC1") (pin "B16") (pinfunction "IO_30_B16") (pintype "bidirectional"))
      (node (ref "JP104") (pin "1") (pinfunction "1_1") (pintype "passive"))
    )
    (net (code "55") (name "IO31") (class "Default")
      (node (ref "IC1") (pin "B17") (pinfunction "IO_31_B17") (pintype "bidirectional"))
      (node (ref "JP103") (pin "1") (pinfunction "1_1") (pintype "passive"))
    )
    (net (code "56") (name "IO32") (class "Default")
      (node (ref "IC1") (pin "B18") (pinfunction "IO_32_B18") (pintype "bidirectional"))
      (node (ref "JP105") (pin "1") (pinfunction "1_1") (pintype "passive"))
    )
    (net (code "57") (name "IO33") (class "Default")
      (node (ref "IC1") (pin "B19") (pinfunction "IO_33_B19") (pintype "bidirectional"))
      (node (ref "JP4") (pin "1") (pinfunction "1_1") (pintype "passive"))
    )
    (net (code "58") (name "IO34") (class "Default")
      (node (ref "IC1") (pin "B20") (pinfunction "IO_34_B20") (pintype "bidirectional"))
      (node (ref "JP2") (pin "1") (pinfunction "1_1") (pintype "passive"))
    )
    (net (code "59") (name "IO35") (class "Default")
      (node (ref "IC1") (pin "B21") (pinfunction "IO_35_B21") (pintype "bidirectional"))
      (node (ref "JP5") (pin "1") (pinfunction "1_1") (pintype "passive"))
    )
    (net (code "60") (name "IO36") (class "Default")
      (node (ref "IC1") (pin "B22") (pinfunction "IO_36_B22") (pintype "bidirectional"))
      (node (ref "JP6") (pin "1") (pinfunction "1_1") (pintype "passive"))
    )
    (net (code "61") (name "IO37") (class "Default")
      (node (ref "IC1") (pin "C1") (pinfunction "IO_37_C1") (pintype "bidirectional"))
      (node (ref "JP8") (pin "1") (pinfunction "1_1") (pintype "passive"))
    )
    (net (code "62") (name "IO38") (class "Default")
      (node (ref "IC1") (pin "C2") (pinfunction "IO_38_C2") (pintype "bidirectional"))
      (node (ref "JP7") (pin "1") (pinfunction "1_1") (pintype "passive"))
    )
    (net (code "63") (name "IO39") (class "Default")
      (node (ref "IC1") (pin "C3") (pinfunction "IO_39_C3") (pintype "bidirectional"))
      (node (ref "JP9") (pin "1") (pinfunction "1_1") (pintype "passive"))
    )
    (net (code "64") (name "IO40") (class "Default")
      (node (ref "IC1") (pin "C4") (pinfunction "IO_40_C4") (pintype "bidirectional"))
      (node (ref "JP10") (pin "1") (pinfunction "1_1") (pintype "passive"))
    )
    (net (code "65") (name "IO41") (class "Default")
      (node (ref "IC1") (pin "C6") (pinfunction "IO_41_C6") (pintype "bidirectional"))
      (node (ref "JP12") (pin "1") (pinfunction "1_1") (pintype "passive"))
    )
    (net (code "66") (name "IO42") (class "Default")
      (node (ref "IC1") (pin "C7") (pinfunction "IO_42_C7") (pintype "bidirectional"))
      (node (ref "JP11") (pin "1") (pinfunction "1_1") (pintype "passive"))
    )
    (net (code "67") (name "IO43") (class "Default")
      (node (ref "IC1") (pin "C8") (pinfunction "IO_43_C8") (pintype "bidirectional"))
      (node (ref "JP14") (pin "1") (pinfunction "1_1") (pintype "passive"))
    )
    (net (code "68") (name "IO44") (class "Default")
      (node (ref "IC1") (pin "C10") (pinfunction "IO_44_C10") (pintype "bidirectional"))
      (node (ref "JP15") (pin "1") (pinfunction "1_1") (pintype "passive"))
    )
    (net (code "69") (name "IO45") (class "Default")
      (node (ref "IC1") (pin "C13") (pinfunction "IO_45_C13") (pintype "bidirectional"))
      (node (ref "JP32") (pin "1") (pinfunction "1_1") (pintype "passive"))
    )
    (net (code "70") (name "IO46") (class "Default")
      (node (ref "IC1") (pin "C15") (pinfunction "IO_46_C15") (pintype "bidirectional"))
      (node (ref "JP34") (pin "1") (pinfunction "1_1") (pintype "passive"))
    )
    (net (code "71") (name "IO47") (class "Default")
      (node (ref "IC1") (pin "C17") (pinfunction "IO_47_C17") (pintype "bidirectional"))
      (node (ref "JP33") (pin "1") (pinfunction "1_1") (pintype "passive"))
    )
    (net (code "72") (name "IO48") (class "Default")
      (node (ref "IC1") (pin "C19") (pinfunction "IO_48_C19") (pintype "bidirectional"))
      (node (ref "JP35") (pin "1") (pinfunction "1_1") (pintype "passive"))
    )
    (net (code "73") (name "IO49") (class "Default")
      (node (ref "IC1") (pin "C20") (pinfunction "IO_49_C20") (pintype "bidirectional"))
      (node (ref "JP36") (pin "1") (pinfunction "1_1") (pintype "passive"))
    )
    (net (code "74") (name "IO50") (class "Default")
      (node (ref "IC1") (pin "C21") (pinfunction "IO_50_C21") (pintype "bidirectional"))
      (node (ref "JP38") (pin "1") (pinfunction "1_1") (pintype "passive"))
    )
    (net (code "75") (name "IO51") (class "Default")
      (node (ref "IC1") (pin "C22") (pinfunction "IO_51_C22") (pintype "bidirectional"))
      (node (ref "JP37") (pin "1") (pinfunction "1_1") (pintype "passive"))
    )
    (net (code "76") (name "IO53") (class "Default")
      (node (ref "IC1") (pin "D2") (pinfunction "IO_53_D2") (pintype "bidirectional"))
      (node (ref "JP40") (pin "1") (pinfunction "1_1") (pintype "passive"))
    )
    (net (code "77") (name "IO54") (class "Default")
      (node (ref "IC1") (pin "D6") (pinfunction "IO_54_D6") (pintype "bidirectional"))
      (node (ref "JP42") (pin "1") (pinfunction "1_1") (pintype "passive"))
    )
    (net (code "78") (name "IO55") (class "Default")
      (node (ref "IC1") (pin "D7") (pinfunction "IO_55_D7") (pintype "bidirectional"))
      (node (ref "JP41") (pin "1") (pinfunction "1_1") (pintype "passive"))
    )
    (net (code "79") (name "IO56") (class "Default")
      (node (ref "IC1") (pin "D10") (pinfunction "IO_56_D10") (pintype "bidirectional"))
      (node (ref "JP43") (pin "1") (pinfunction "1_1") (pintype "passive"))
    )
    (net (code "80") (name "IO57") (class "Default")
      (node (ref "IC1") (pin "D13") (pinfunction "IO_57_D13") (pintype "bidirectional"))
      (node (ref "JP44") (pin "1") (pinfunction "1_1") (pintype "passive"))
    )
    (net (code "81") (name "IO58") (class "Default")
      (node (ref "IC1") (pin "D15") (pinfunction "IO_58_D15") (pintype "bidirectional"))
      (node (ref "JP48") (pin "1") (pinfunction "1_1") (pintype "passive"))
    )
    (net (code "82") (name "IO59") (class "Default")
      (node (ref "IC1") (pin "D17") (pinfunction "IO_59_D17") (pintype "bidirectional"))
      (node (ref "JP47") (pin "1") (pinfunction "1_1") (pintype "passive"))
    )
    (net (code "83") (name "IO60") (class "Default")
      (node (ref "IC1") (pin "D19") (pinfunction "IO_60_D19") (pintype "bidirectional"))
      (node (ref "JP49") (pin "1") (pinfunction "1_1") (pintype "passive"))
    )
    (net (code "84") (name "IO61") (class "Default")
      (node (ref "IC1") (pin "D20") (pinfunction "IO_61_D20") (pintype "bidirectional"))
      (node (ref "JP50") (pin "1") (pinfunction "1_1") (pintype "passive"))
    )
    (net (code "85") (name "IO62") (class "Default")
      (node (ref "IC1") (pin "D21") (pinfunction "IO_62_D21") (pintype "bidirectional"))
      (node (ref "JP52") (pin "1") (pinfunction "1_1") (pintype "passive"))
    )
    (net (code "86") (name "IO63") (class "Default")
      (node (ref "IC1") (pin "D22") (pinfunction "IO_63_D22") (pintype "bidirectional"))
      (node (ref "JP51") (pin "1") (pinfunction "1_1") (pintype "passive"))
    )
    (net (code "87") (name "IO64") (class "Default")
      (node (ref "IC1") (pin "E1") (pinfunction "IO_64_E1") (pintype "bidirectional"))
      (node (ref "JP53") (pin "1") (pinfunction "1_1") (pintype "passive"))
    )
    (net (code "88") (name "IO66") (class "Default")
      (node (ref "IC1") (pin "E3") (pinfunction "IO_66_E3") (pintype "bidirectional"))
      (node (ref "JP56") (pin "1") (pinfunction "1_1") (pintype "passive"))
    )
    (net (code "89") (name "IO67") (class "Default")
      (node (ref "IC1") (pin "E4") (pinfunction "IO_67_E4") (pintype "bidirectional"))
      (node (ref "JP55") (pin "1") (pinfunction "1_1") (pintype "passive"))
    )
    (net (code "90") (name "IO68") (class "Default")
      (node (ref "IC1") (pin "E5") (pinfunction "IO_68_E5") (pintype "bidirectional"))
      (node (ref "JP58") (pin "1") (pinfunction "1_1") (pintype "passive"))
    )
    (net (code "91") (name "IO69") (class "Default")
      (node (ref "IC1") (pin "E6") (pinfunction "IO_69_E6") (pintype "bidirectional"))
      (node (ref "JP59") (pin "1") (pinfunction "1_1") (pintype "passive"))
    )
    (net (code "92") (name "IO70") (class "Default")
      (node (ref "IC1") (pin "E7") (pinfunction "IO_70_E7") (pintype "bidirectional"))
      (node (ref "JP60") (pin "1") (pinfunction "1_1") (pintype "passive"))
    )
    (net (code "93") (name "IO71") (class "Default")
      (node (ref "IC1") (pin "E9") (pinfunction "IO_71_E9") (pintype "bidirectional"))
      (node (ref "JP62") (pin "1") (pinfunction "1_1") (pintype "passive"))
    )
    (net (code "94") (name "IO72") (class "Default")
      (node (ref "IC1") (pin "E10") (pinfunction "IO_72_E10") (pintype "bidirectional"))
      (node (ref "JP61") (pin "1") (pinfunction "1_1") (pintype "passive"))
    )
    (net (code "95") (name "IO73") (class "Default")
      (node (ref "IC1") (pin "E11") (pinfunction "IO_73_E11") (pintype "bidirectional"))
      (node (ref "JP63") (pin "1") (pinfunction "1_1") (pintype "passive"))
    )
    (net (code "96") (name "IO74") (class "Default")
      (node (ref "IC1") (pin "E12") (pinfunction "IO_74_E12") (pintype "bidirectional"))
      (node (ref "JP64") (pin "1") (pinfunction "1_1") (pintype "passive"))
    )
    (net (code "97") (name "IO75") (class "Default")
      (node (ref "IC1") (pin "E13") (pinfunction "IO_75_E13") (pintype "bidirectional"))
      (node (ref "JP66") (pin "1") (pinfunction "1_1") (pintype "passive"))
    )
    (net (code "98") (name "IO76") (class "Default")
      (node (ref "IC1") (pin "E14") (pinfunction "IO_76_E14") (pintype "bidirectional"))
      (node (ref "JP65") (pin "1") (pinfunction "1_1") (pintype "passive"))
    )
    (net (code "99") (name "IO77") (class "Default")
      (node (ref "IC1") (pin "E15") (pinfunction "IO_77_E15") (pintype "bidirectional"))
      (node (ref "JP67") (pin "1") (pinfunction "1_1") (pintype "passive"))
    )
    (net (code "100") (name "IO78") (class "Default")
      (node (ref "IC1") (pin "E16") (pinfunction "IO_78_E16") (pintype "bidirectional"))
      (node (ref "JP68") (pin "1") (pinfunction "1_1") (pintype "passive"))
    )
    (net (code "101") (name "IO79") (class "Default")
      (node (ref "IC1") (pin "E21") (pinfunction "IO_79_E21") (pintype "bidirectional"))
      (node (ref "JP70") (pin "1") (pinfunction "1_1") (pintype "passive"))
    )
    (net (code "102") (name "IO80") (class "Default")
      (node (ref "IC1") (pin "E22") (pinfunction "IO_80_E22") (pintype "bidirectional"))
      (node (ref "JP69") (pin "1") (pinfunction "1_1") (pintype "passive"))
    )
    (net (code "103") (name "IO81") (class "Default")
      (node (ref "IC1") (pin "F1") (pinfunction "IO_81_F1") (pintype "bidirectional"))
      (node (ref "JP71") (pin "1") (pinfunction "1_1") (pintype "passive"))
    )
    (net (code "104") (name "IO82") (class "Default")
      (node (ref "IC1") (pin "F2") (pinfunction "IO_82_F2") (pintype "bidirectional"))
      (node (ref "JP72") (pin "1") (pinfunction "1_1") (pintype "passive"))
    )
    (net (code "105") (name "IO83") (class "Default")
      (node (ref "IC1") (pin "F7") (pinfunction "IO_83_F7") (pintype "bidirectional"))
      (node (ref "JP140") (pin "1") (pinfunction "1_1") (pintype "passive"))
    )
    (net (code "106") (name "IO84") (class "Default")
      (node (ref "IC1") (pin "F8") (pinfunction "IO_84_F8") (pintype "bidirectional"))
      (node (ref "JP139") (pin "1") (pinfunction "1_1") (pintype "passive"))
    )
    (net (code "107") (name "IO85") (class "Default")
      (node (ref "IC1") (pin "F9") (pinfunction "IO_85_F9") (pintype "bidirectional"))
      (node (ref "JP141") (pin "1") (pinfunction "1_1") (pintype "passive"))
    )
    (net (code "108") (name "IO86") (class "Default")
      (node (ref "IC1") (pin "F10") (pinfunction "IO_86_F10") (pintype "bidirectional"))
      (node (ref "JP142") (pin "1") (pinfunction "1_1") (pintype "passive"))
    )
    (net (code "109") (name "IO87") (class "Default")
      (node (ref "IC1") (pin "F11") (pinfunction "IO_87_F11") (pintype "bidirectional"))
      (node (ref "JP144") (pin "1") (pinfunction "1_1") (pintype "passive"))
    )
    (net (code "110") (name "IO88") (class "Default")
      (node (ref "IC1") (pin "F13") (pinfunction "IO_88_F13") (pintype "bidirectional"))
      (node (ref "JP143") (pin "1") (pinfunction "1_1") (pintype "passive"))
    )
    (net (code "111") (name "IO89") (class "Default")
      (node (ref "IC1") (pin "F14") (pinfunction "IO_89_F14") (pintype "bidirectional"))
      (node (ref "JP145") (pin "1") (pinfunction "1_1") (pintype "passive"))
    )
    (net (code "112") (name "IO90") (class "Default")
      (node (ref "IC1") (pin "F15") (pinfunction "IO_90_F15") (pintype "bidirectional"))
      (node (ref "JP146") (pin "1") (pinfunction "1_1") (pintype "passive"))
    )
    (net (code "113") (name "IO91") (class "Default")
      (node (ref "IC1") (pin "F16") (pinfunction "IO_91_F16") (pintype "bidirectional"))
      (node (ref "JP148") (pin "1") (pinfunction "1_1") (pintype "passive"))
    )
    (net (code "114") (name "IO92") (class "Default")
      (node (ref "IC1") (pin "F17") (pinfunction "IO_92_F17") (pintype "bidirectional"))
      (node (ref "JP147") (pin "1") (pinfunction "1_1") (pintype "passive"))
    )
    (net (code "115") (name "IO93") (class "Default")
      (node (ref "IC1") (pin "F19") (pinfunction "IO_93_F19") (pintype "bidirectional"))
      (node (ref "JP150") (pin "1") (pinfunction "1_1") (pintype "passive"))
    )
    (net (code "116") (name "IO94") (class "Default")
      (node (ref "IC1") (pin "F20") (pinfunction "IO_94_F20") (pintype "bidirectional"))
      (node (ref "JP151") (pin "1") (pinfunction "1_1") (pintype "passive"))
    )
    (net (code "117") (name "IO95") (class "Default")
      (node (ref "IC1") (pin "F21") (pinfunction "IO_95_F21") (pintype "bidirectional"))
      (node (ref "JP152") (pin "1") (pinfunction "1_1") (pintype "passive"))
    )
    (net (code "118") (name "IO96") (class "Default")
      (node (ref "IC1") (pin "F22") (pinfunction "IO_96_F22") (pintype "bidirectional"))
      (node (ref "JP154") (pin "1") (pinfunction "1_1") (pintype "passive"))
    )
    (net (code "119") (name "IO97") (class "Default")
      (node (ref "IC1") (pin "G3") (pinfunction "IO_97_G3") (pintype "bidirectional"))
      (node (ref "JP153") (pin "1") (pinfunction "1_1") (pintype "passive"))
    )
    (net (code "120") (name "IO98") (class "Default")
      (node (ref "IC1") (pin "G4") (pinfunction "IO_98_G4") (pintype "bidirectional"))
      (node (ref "JP155") (pin "1") (pinfunction "1_1") (pintype "passive"))
    )
    (net (code "121") (name "IO99") (class "Default")
      (node (ref "IC1") (pin "G5") (pinfunction "IO_99_G5") (pintype "bidirectional"))
      (node (ref "JP156") (pin "1") (pinfunction "1_1") (pintype "passive"))
    )
    (net (code "122") (name "IO100") (class "Default")
      (node (ref "IC1") (pin "G7") (pinfunction "IO_100_G7") (pintype "bidirectional"))
      (node (ref "JP158") (pin "1") (pinfunction "1_1") (pintype "passive"))
    )
    (net (code "123") (name "IO101") (class "Default")
      (node (ref "IC1") (pin "G8") (pinfunction "IO_101_G8") (pintype "bidirectional"))
      (node (ref "JP157") (pin "1") (pinfunction "1_1") (pintype "passive"))
    )
    (net (code "124") (name "IO102") (class "Default")
      (node (ref "IC1") (pin "G9") (pinfunction "IO_102_G9") (pintype "bidirectional"))
      (node (ref "JP159") (pin "1") (pinfunction "1_1") (pintype "passive"))
    )
    (net (code "125") (name "IO103") (class "Default")
      (node (ref "IC1") (pin "G10") (pinfunction "IO_103_G10") (pintype "bidirectional"))
      (node (ref "JP160") (pin "1") (pinfunction "1_1") (pintype "passive"))
    )
    (net (code "126") (name "IO104") (class "Default")
      (node (ref "IC1") (pin "G11") (pinfunction "IO_104_G11") (pintype "bidirectional"))
      (node (ref "JP162") (pin "1") (pinfunction "1_1") (pintype "passive"))
    )
    (net (code "127") (name "IO105") (class "Default")
      (node (ref "IC1") (pin "G13") (pinfunction "IO_105_G13") (pintype "bidirectional"))
      (node (ref "JP161") (pin "1") (pinfunction "1_1") (pintype "passive"))
    )
    (net (code "128") (name "IO106") (class "Default")
      (node (ref "IC1") (pin "G14") (pinfunction "IO_106_G14") (pintype "bidirectional"))
      (node (ref "JP163") (pin "1") (pinfunction "1_1") (pintype "passive"))
    )
    (net (code "129") (name "IO107") (class "Default")
      (node (ref "IC1") (pin "G15") (pinfunction "IO_107_G15") (pintype "bidirectional"))
      (node (ref "JP164") (pin "1") (pinfunction "1_1") (pintype "passive"))
    )
    (net (code "130") (name "IO108") (class "Default")
      (node (ref "IC1") (pin "G16") (pinfunction "IO_108_G16") (pintype "bidirectional"))
      (node (ref "JP168") (pin "1") (pinfunction "1_1") (pintype "passive"))
    )
    (net (code "131") (name "IO109") (class "Default")
      (node (ref "IC1") (pin "G17") (pinfunction "IO_109_G17") (pintype "bidirectional"))
      (node (ref "JP167") (pin "1") (pinfunction "1_1") (pintype "passive"))
    )
    (net (code "132") (name "IO110") (class "Default")
      (node (ref "IC1") (pin "G18") (pinfunction "IO_110_G18") (pintype "bidirectional"))
      (node (ref "JP169") (pin "1") (pinfunction "1_1") (pintype "passive"))
    )
    (net (code "133") (name "IO111") (class "Default")
      (node (ref "IC1") (pin "H1") (pinfunction "IO_111_H1") (pintype "bidirectional"))
      (node (ref "JP170") (pin "1") (pinfunction "1_1") (pintype "passive"))
    )
    (net (code "134") (name "IO112") (class "Default")
      (node (ref "IC1") (pin "H2") (pinfunction "IO_112_H2") (pintype "bidirectional"))
      (node (ref "JP172") (pin "1") (pinfunction "1_1") (pintype "passive"))
    )
    (net (code "135") (name "IO113") (class "Default")
      (node (ref "IC1") (pin "H5") (pinfunction "IO_113_H5") (pintype "bidirectional"))
      (node (ref "JP171") (pin "1") (pinfunction "1_1") (pintype "passive"))
    )
    (net (code "136") (name "IO114") (class "Default")
      (node (ref "IC1") (pin "H6") (pinfunction "IO_114_H6") (pintype "bidirectional"))
      (node (ref "JP173") (pin "1") (pinfunction "1_1") (pintype "passive"))
    )
    (net (code "137") (name "IO115") (class "Default")
      (node (ref "IC1") (pin "H7") (pinfunction "IO_115_H7") (pintype "bidirectional"))
      (node (ref "JP174") (pin "1") (pinfunction "1_1") (pintype "passive"))
    )
    (net (code "138") (name "IO116") (class "Default")
      (node (ref "IC1") (pin "H8") (pinfunction "IO_116_H8") (pintype "bidirectional"))
      (node (ref "JP176") (pin "1") (pinfunction "1_1") (pintype "passive"))
    )
    (net (code "139") (name "IO117") (class "Default")
      (node (ref "IC1") (pin "H10") (pinfunction "IO_117_H10") (pintype "bidirectional"))
      (node (ref "JP175") (pin "1") (pinfunction "1_1") (pintype "passive"))
    )
    (net (code "140") (name "IO118") (class "Default")
      (node (ref "IC1") (pin "H11") (pinfunction "IO_118_H11") (pintype "bidirectional"))
      (node (ref "JP178") (pin "1") (pinfunction "1_1") (pintype "passive"))
    )
    (net (code "141") (name "IO119") (class "Default")
      (node (ref "IC1") (pin "H14") (pinfunction "IO_119_H14") (pintype "bidirectional"))
      (node (ref "JP179") (pin "1") (pinfunction "1_1") (pintype "passive"))
    )
    (net (code "142") (name "IO120") (class "Default")
      (node (ref "IC1") (pin "H15") (pinfunction "IO_120_H15") (pintype "bidirectional"))
      (node (ref "JP180") (pin "1") (pinfunction "1_1") (pintype "passive"))
    )
    (net (code "143") (name "IO121") (class "Default")
      (node (ref "IC1") (pin "H16") (pinfunction "IO_121_H16") (pintype "bidirectional"))
      (node (ref "JP182") (pin "1") (pinfunction "1_1") (pintype "passive"))
    )
    (net (code "144") (name "IO122") (class "Default")
      (node (ref "IC1") (pin "H17") (pinfunction "IO_122_H17") (pintype "bidirectional"))
      (node (ref "JP181") (pin "1") (pinfunction "1_1") (pintype "passive"))
    )
    (net (code "145") (name "IO123") (class "Default")
      (node (ref "IC1") (pin "H18") (pinfunction "IO_123_H18") (pintype "bidirectional"))
      (node (ref "JP183") (pin "1") (pinfunction "1_1") (pintype "passive"))
    )
    (net (code "146") (name "IO124") (class "Default")
      (node (ref "IC1") (pin "H19") (pinfunction "IO_124_H19") (pintype "bidirectional"))
      (node (ref "JP184") (pin "1") (pinfunction "1_1") (pintype "passive"))
    )
    (net (code "147") (name "IO125") (class "Default")
      (node (ref "IC1") (pin "H20") (pinfunction "IO_125_H20") (pintype "bidirectional"))
      (node (ref "JP186") (pin "1") (pinfunction "1_1") (pintype "passive"))
    )
    (net (code "148") (name "IO126") (class "Default")
      (node (ref "IC1") (pin "H21") (pinfunction "IO_126_H21") (pintype "bidirectional"))
      (node (ref "JP185") (pin "1") (pinfunction "1_1") (pintype "passive"))
    )
    (net (code "149") (name "IO127") (class "Default")
      (node (ref "IC1") (pin "H22") (pinfunction "IO_127_H22") (pintype "bidirectional"))
      (node (ref "JP187") (pin "1") (pinfunction "1_1") (pintype "passive"))
    )
    (net (code "150") (name "IO128") (class "Default")
      (node (ref "IC1") (pin "J1") (pinfunction "IO_128_J1") (pintype "bidirectional"))
      (node (ref "JP188") (pin "1") (pinfunction "1_1") (pintype "passive"))
    )
    (net (code "151") (name "IO129") (class "Default")
      (node (ref "IC1") (pin "J2") (pinfunction "IO_129_J2") (pintype "bidirectional"))
      (node (ref "JP190") (pin "1") (pinfunction "1_1") (pintype "passive"))
    )
    (net (code "152") (name "IO130") (class "Default")
      (node (ref "IC1") (pin "J3") (pinfunction "IO_130_J3") (pintype "bidirectional"))
      (node (ref "JP189") (pin "1") (pinfunction "1_1") (pintype "passive"))
    )
    (net (code "153") (name "IO131") (class "Default")
      (node (ref "IC1") (pin "J4") (pinfunction "IO_131_J4") (pintype "bidirectional"))
      (node (ref "JP191") (pin "1") (pinfunction "1_1") (pintype "passive"))
    )
    (net (code "154") (name "IO132") (class "Default")
      (node (ref "IC1") (pin "J5") (pinfunction "IO_132_J5") (pintype "bidirectional"))
      (node (ref "JP192") (pin "1") (pinfunction "1_1") (pintype "passive"))
    )
    (net (code "155") (name "IO133") (class "Default")
      (node (ref "IC1") (pin "J6") (pinfunction "IO_133_J6") (pintype "bidirectional"))
      (node (ref "JP106") (pin "1") (pinfunction "1_1") (pintype "passive"))
    )
    (net (code "156") (name "IO134") (class "Default")
      (node (ref "IC1") (pin "J7") (pinfunction "IO_134_J7") (pintype "bidirectional"))
      (node (ref "JP108") (pin "1") (pinfunction "1_1") (pintype "passive"))
    )
    (net (code "157") (name "IO135") (class "Default")
      (node (ref "IC1") (pin "J8") (pinfunction "IO_135_J8") (pintype "bidirectional"))
      (node (ref "JP107") (pin "1") (pinfunction "1_1") (pintype "passive"))
    )
    (net (code "158") (name "IO136") (class "Default")
      (node (ref "IC1") (pin "J17") (pinfunction "IO_136_J17") (pintype "bidirectional"))
      (node (ref "JP109") (pin "1") (pinfunction "1_1") (pintype "passive"))
    )
    (net (code "159") (name "IO137") (class "Default")
      (node (ref "IC1") (pin "J18") (pinfunction "IO_137_J18") (pintype "bidirectional"))
      (node (ref "JP110") (pin "1") (pinfunction "1_1") (pintype "passive"))
    )
    (net (code "160") (name "IO138") (class "Default")
      (node (ref "IC1") (pin "J21") (pinfunction "IO_138_J21") (pintype "bidirectional"))
      (node (ref "JP112") (pin "1") (pinfunction "1_1") (pintype "passive"))
    )
    (net (code "161") (name "IO139") (class "Default")
      (node (ref "IC1") (pin "J22") (pinfunction "IO_139_J22") (pintype "bidirectional"))
      (node (ref "JP111") (pin "1") (pinfunction "1_1") (pintype "passive"))
    )
    (net (code "162") (name "IO141") (class "Default")
      (node (ref "IC1") (pin "K7") (pinfunction "IO_141_K7") (pintype "bidirectional"))
      (node (ref "JP114") (pin "1") (pinfunction "1_1") (pintype "passive"))
    )
    (net (code "163") (name "IO142") (class "Default")
      (node (ref "IC1") (pin "K8") (pinfunction "IO_142_K8") (pintype "bidirectional"))
      (node (ref "JP116") (pin "1") (pinfunction "1_1") (pintype "passive"))
    )
    (net (code "164") (name "IO143") (class "Default")
      (node (ref "IC1") (pin "K17") (pinfunction "IO_143_K17") (pintype "bidirectional"))
      (node (ref "JP115") (pin "1") (pinfunction "1_1") (pintype "passive"))
    )
    (net (code "165") (name "IO144") (class "Default")
      (node (ref "IC1") (pin "K18") (pinfunction "IO_144_K18") (pintype "bidirectional"))
      (node (ref "JP117") (pin "1") (pinfunction "1_1") (pintype "passive"))
    )
    (net (code "166") (name "IO145") (class "Default")
      (node (ref "IC1") (pin "K19") (pinfunction "IO_145_K19") (pintype "bidirectional"))
      (node (ref "JP118") (pin "1") (pinfunction "1_1") (pintype "passive"))
    )
    (net (code "167") (name "IO146") (class "Default")
      (node (ref "IC1") (pin "K21") (pinfunction "IO_146_K21") (pintype "bidirectional"))
      (node (ref "JP120") (pin "1") (pinfunction "1_1") (pintype "passive"))
    )
    (net (code "168") (name "IO147") (class "Default")
      (node (ref "IC1") (pin "K22") (pinfunction "IO_147_K22") (pintype "bidirectional"))
      (node (ref "JP119") (pin "1") (pinfunction "1_1") (pintype "passive"))
    )
    (net (code "169") (name "IO148") (class "Default")
      (node (ref "IC1") (pin "L6") (pinfunction "IO_148_L6") (pintype "bidirectional"))
      (node (ref "JP121") (pin "1") (pinfunction "1_1") (pintype "passive"))
    )
    (net (code "170") (name "IO149") (class "Default")
      (node (ref "IC1") (pin "L7") (pinfunction "IO_149_L7") (pintype "bidirectional"))
      (node (ref "JP122") (pin "1") (pinfunction "1_1") (pintype "passive"))
    )
    (net (code "171") (name "IO150") (class "Default")
      (node (ref "IC1") (pin "L8") (pinfunction "IO_150_L8") (pintype "bidirectional"))
      (node (ref "JP124") (pin "1") (pinfunction "1_1") (pintype "passive"))
    )
    (net (code "172") (name "IO151") (class "Default")
      (node (ref "IC1") (pin "L21") (pinfunction "IO_151_L21") (pintype "bidirectional"))
      (node (ref "JP123") (pin "1") (pinfunction "1_1") (pintype "passive"))
    )
    (net (code "173") (name "IO152") (class "Default")
      (node (ref "IC1") (pin "L22") (pinfunction "IO_152_L22") (pintype "bidirectional"))
      (node (ref "JP125") (pin "1") (pinfunction "1_1") (pintype "passive"))
    )
    (net (code "174") (name "IO153") (class "Default")
      (node (ref "IC1") (pin "M1") (pinfunction "IO_153_M1") (pintype "bidirectional"))
      (node (ref "JP126") (pin "1") (pinfunction "1_1") (pintype "passive"))
    )
    (net (code "175") (name "IO154") (class "Default")
      (node (ref "IC1") (pin "M2") (pinfunction "IO_154_M2") (pintype "bidirectional"))
      (node (ref "JP128") (pin "1") (pinfunction "1_1") (pintype "passive"))
    )
    (net (code "176") (name "IO155") (class "Default")
      (node (ref "IC1") (pin "M3") (pinfunction "IO_155_M3") (pintype "bidirectional"))
      (node (ref "JP127") (pin "1") (pinfunction "1_1") (pintype "passive"))
    )
    (net (code "177") (name "IO156") (class "Default")
      (node (ref "IC1") (pin "M4") (pinfunction "IO_156_M4") (pintype "bidirectional"))
      (node (ref "JP129") (pin "1") (pinfunction "1_1") (pintype "passive"))
    )
    (net (code "178") (name "IO157") (class "Default")
      (node (ref "IC1") (pin "M5") (pinfunction "IO_157_M5") (pintype "bidirectional"))
      (node (ref "JP130") (pin "1") (pinfunction "1_1") (pintype "passive"))
    )
    (net (code "179") (name "IO158") (class "Default")
      (node (ref "IC1") (pin "M6") (pinfunction "IO_158_M6") (pintype "bidirectional"))
      (node (ref "JP132") (pin "1") (pinfunction "1_1") (pintype "passive"))
    )
    (net (code "180") (name "IO159") (class "Default")
      (node (ref "IC1") (pin "M7") (pinfunction "IO_159_M7") (pintype "bidirectional"))
      (node (ref "JP131") (pin "1") (pinfunction "1_1") (pintype "passive"))
    )
    (net (code "181") (name "IO160") (class "Default")
      (node (ref "IC1") (pin "M8") (pinfunction "IO_160_M8") (pintype "bidirectional"))
      (node (ref "JP133") (pin "1") (pinfunction "1_1") (pintype "passive"))
    )
    (net (code "182") (name "IO161") (class "Default")
      (node (ref "IC1") (pin "M16") (pinfunction "IO_161_M16") (pintype "bidirectional"))
      (node (ref "JP134") (pin "1") (pinfunction "1_1") (pintype "passive"))
    )
    (net (code "183") (name "IO162") (class "Default")
      (node (ref "IC1") (pin "M19") (pinfunction "IO_162_M19") (pintype "bidirectional"))
      (node (ref "JP136") (pin "1") (pinfunction "1_1") (pintype "passive"))
    )
    (net (code "184") (name "IO163") (class "Default")
      (node (ref "IC1") (pin "M20") (pinfunction "IO_163_M20") (pintype "bidirectional"))
      (node (ref "JP135") (pin "1") (pinfunction "1_1") (pintype "passive"))
    )
    (net (code "185") (name "IO164") (class "Default")
      (node (ref "IC1") (pin "M21") (pinfunction "IO_164_M21") (pintype "bidirectional"))
      (node (ref "JP137") (pin "1") (pinfunction "1_1") (pintype "passive"))
    )
    (net (code "186") (name "IO165") (class "Default")
      (node (ref "IC1") (pin "M22") (pinfunction "IO_165_M22") (pintype "bidirectional"))
      (node (ref "JP194") (pin "1") (pinfunction "1_1") (pintype "passive"))
    )
    (net (code "187") (name "IO166") (class "Default")
      (node (ref "IC1") (pin "N1") (pinfunction "IO_166_N1") (pintype "bidirectional"))
      (node (ref "JP196") (pin "1") (pinfunction "1_1") (pintype "passive"))
    )
    (net (code "188") (name "IO167") (class "Default")
      (node (ref "IC1") (pin "N2") (pinfunction "IO_167_N2") (pintype "bidirectional"))
      (node (ref "JP195") (pin "1") (pinfunction "1_1") (pintype "passive"))
    )
    (net (code "189") (name "IO168") (class "Default")
      (node (ref "IC1") (pin "N5") (pinfunction "IO_168_N5") (pintype "bidirectional"))
      (node (ref "JP197") (pin "1") (pinfunction "1_1") (pintype "passive"))
    )
    (net (code "190") (name "IO169") (class "Default")
      (node (ref "IC1") (pin "N6") (pinfunction "IO_169_N6") (pintype "bidirectional"))
      (node (ref "JP198") (pin "1") (pinfunction "1_1") (pintype "passive"))
    )
    (net (code "191") (name "IO170") (class "Default")
      (node (ref "IC1") (pin "N7") (pinfunction "IO_170_N7") (pintype "bidirectional"))
      (node (ref "JP200") (pin "1") (pinfunction "1_1") (pintype "passive"))
    )
    (net (code "192") (name "IO171") (class "Default")
      (node (ref "IC1") (pin "N8") (pinfunction "IO_171_N8") (pintype "bidirectional"))
      (node (ref "JP199") (pin "1") (pinfunction "1_1") (pintype "passive"))
    )
    (net (code "193") (name "IO172") (class "Default")
      (node (ref "IC1") (pin "N16") (pinfunction "IO_172_N16") (pintype "bidirectional"))
      (node (ref "JP201") (pin "1") (pinfunction "1_1") (pintype "passive"))
    )
    (net (code "194") (name "IO173") (class "Default")
      (node (ref "IC1") (pin "N17") (pinfunction "IO_173_N17") (pintype "bidirectional"))
      (node (ref "JP202") (pin "1") (pinfunction "1_1") (pintype "passive"))
    )
    (net (code "195") (name "IO174") (class "Default")
      (node (ref "IC1") (pin "N18") (pinfunction "IO_174_N18") (pintype "bidirectional"))
      (node (ref "JP204") (pin "1") (pinfunction "1_1") (pintype "passive"))
    )
    (net (code "196") (name "IO175") (class "Default")
      (node (ref "IC1") (pin "N19") (pinfunction "IO_175_N19") (pintype "bidirectional"))
      (node (ref "JP203") (pin "1") (pinfunction "1_1") (pintype "passive"))
    )
    (net (code "197") (name "IO176") (class "Default")
      (node (ref "IC1") (pin "N20") (pinfunction "IO_176_N20") (pintype "bidirectional"))
      (node (ref "JP205") (pin "1") (pinfunction "1_1") (pintype "passive"))
    )
    (net (code "198") (name "IO177") (class "Default")
      (node (ref "IC1") (pin "N21") (pinfunction "IO_177_N21") (pintype "bidirectional"))
      (node (ref "JP206") (pin "1") (pinfunction "1_1") (pintype "passive"))
    )
    (net (code "199") (name "IO178") (class "Default")
      (node (ref "IC1") (pin "N22") (pinfunction "IO_178_N22") (pintype "bidirectional"))
      (node (ref "JP207") (pin "1") (pinfunction "1_1") (pintype "passive"))
    )
    (net (code "200") (name "IO179") (class "Default")
      (node (ref "IC1") (pin "P1") (pinfunction "IO_179_P1") (pintype "bidirectional"))
      (node (ref "JP208") (pin "1") (pinfunction "1_1") (pintype "passive"))
    )
    (net (code "201") (name "IO180") (class "Default")
      (node (ref "IC1") (pin "P2") (pinfunction "IO_180_P2") (pintype "bidirectional"))
      (node (ref "JP210") (pin "1") (pinfunction "1_1") (pintype "passive"))
    )
    (net (code "202") (name "IO181") (class "Default")
      (node (ref "IC1") (pin "P3") (pinfunction "IO_181_P3") (pintype "bidirectional"))
      (node (ref "JP209") (pin "1") (pinfunction "1_1") (pintype "passive"))
    )
    (net (code "203") (name "IO182") (class "Default")
      (node (ref "IC1") (pin "P4") (pinfunction "IO_182_P4") (pintype "bidirectional"))
      (node (ref "JP211") (pin "1") (pinfunction "1_1") (pintype "passive"))
    )
    (net (code "204") (name "IO183") (class "Default")
      (node (ref "IC1") (pin "P5") (pinfunction "IO_183_P5") (pintype "bidirectional"))
      (node (ref "JP212") (pin "1") (pinfunction "1_1") (pintype "passive"))
    )
    (net (code "205") (name "IO184") (class "Default")
      (node (ref "IC1") (pin "P6") (pinfunction "IO_184_P6") (pintype "bidirectional"))
      (node (ref "JP214") (pin "1") (pinfunction "1_1") (pintype "passive"))
    )
    (net (code "206") (name "IO185") (class "Default")
      (node (ref "IC1") (pin "P7") (pinfunction "IO_185_P7") (pintype "bidirectional"))
      (node (ref "JP213") (pin "1") (pinfunction "1_1") (pintype "passive"))
    )
    (net (code "207") (name "IO186") (class "Default")
      (node (ref "IC1") (pin "P15") (pinfunction "IO_186_P15") (pintype "bidirectional"))
      (node (ref "JP215") (pin "1") (pinfunction "1_1") (pintype "passive"))
    )
    (net (code "208") (name "IO187") (class "Default")
      (node (ref "IC1") (pin "P16") (pinfunction "IO_187_P16") (pintype "bidirectional"))
      (node (ref "JP216") (pin "1") (pinfunction "1_1") (pintype "passive"))
    )
    (net (code "209") (name "IO188") (class "Default")
      (node (ref "IC1") (pin "P17") (pinfunction "IO_188_P17") (pintype "bidirectional"))
      (node (ref "JP218") (pin "1") (pinfunction "1_1") (pintype "passive"))
    )
    (net (code "210") (name "IO189") (class "Default")
      (node (ref "IC1") (pin "P20") (pinfunction "IO_189_P20") (pintype "bidirectional"))
      (node (ref "JP217") (pin "1") (pinfunction "1_1") (pintype "passive"))
    )
    (net (code "211") (name "IO190") (class "Default")
      (node (ref "IC1") (pin "P21") (pinfunction "IO_190_P21") (pintype "bidirectional"))
      (node (ref "JP219") (pin "1") (pinfunction "1_1") (pintype "passive"))
    )
    (net (code "212") (name "IO191") (class "Default")
      (node (ref "IC1") (pin "P22") (pinfunction "IO_191_P22") (pintype "bidirectional"))
      (node (ref "JP220") (pin "1") (pinfunction "1_1") (pintype "passive"))
    )
    (net (code "213") (name "IO192") (class "Default")
      (node (ref "IC1") (pin "R1") (pinfunction "IO_192_R1") (pintype "bidirectional"))
      (node (ref "JP221") (pin "1") (pinfunction "1_1") (pintype "passive"))
    )
    (net (code "214") (name "IO193") (class "Default")
      (node (ref "IC1") (pin "R2") (pinfunction "IO_193_R2") (pintype "bidirectional"))
      (node (ref "JP222") (pin "1") (pinfunction "1_1") (pintype "passive"))
    )
    (net (code "215") (name "IO194") (class "Default")
      (node (ref "IC1") (pin "R5") (pinfunction "IO_194_R5") (pintype "bidirectional"))
      (node (ref "JP224") (pin "1") (pinfunction "1_1") (pintype "passive"))
    )
    (net (code "216") (name "IO195") (class "Default")
      (node (ref "IC1") (pin "R6") (pinfunction "IO_195_R6") (pintype "bidirectional"))
      (node (ref "JP223") (pin "1") (pinfunction "1_1") (pintype "passive"))
    )
    (net (code "217") (name "IO196") (class "Default")
      (node (ref "IC1") (pin "R7") (pinfunction "IO_196_R7") (pintype "bidirectional"))
      (node (ref "JP225") (pin "1") (pinfunction "1_1") (pintype "passive"))
    )
    (net (code "218") (name "IO197") (class "Default")
      (node (ref "IC1") (pin "R14") (pinfunction "IO_197_R14") (pintype "bidirectional"))
      (node (ref "JP226") (pin "1") (pinfunction "1_1") (pintype "passive"))
    )
    (net (code "219") (name "IO198") (class "Default")
      (node (ref "IC1") (pin "R15") (pinfunction "IO_198_R15") (pintype "bidirectional"))
      (node (ref "JP228") (pin "1") (pinfunction "1_1") (pintype "passive"))
    )
    (net (code "220") (name "IO199") (class "Default")
      (node (ref "IC1") (pin "R16") (pinfunction "IO_199_R16") (pintype "bidirectional"))
      (node (ref "JP227") (pin "1") (pinfunction "1_1") (pintype "passive"))
    )
    (net (code "221") (name "IO200") (class "Default")
      (node (ref "IC1") (pin "R17") (pinfunction "IO_200_R17") (pintype "bidirectional"))
      (node (ref "JP229") (pin "1") (pinfunction "1_1") (pintype "passive"))
    )
    (net (code "222") (name "IO201") (class "Default")
      (node (ref "IC1") (pin "R18") (pinfunction "IO_201_R18") (pintype "bidirectional"))
      (node (ref "JP230") (pin "1") (pinfunction "1_1") (pintype "passive"))
    )
    (net (code "223") (name "IO202") (class "Default")
      (node (ref "IC1") (pin "R19") (pinfunction "IO_202_R19") (pintype "bidirectional"))
      (node (ref "JP232") (pin "1") (pinfunction "1_1") (pintype "passive"))
    )
    (net (code "224") (name "IO203") (class "Default")
      (node (ref "IC1") (pin "R20") (pinfunction "IO_203_R20") (pintype "bidirectional"))
      (node (ref "JP231") (pin "1") (pinfunction "1_1") (pintype "passive"))
    )
    (net (code "225") (name "IO204") (class "Default")
      (node (ref "IC1") (pin "R21") (pinfunction "IO_204_R21") (pintype "bidirectional"))
      (node (ref "JP233") (pin "1") (pinfunction "1_1") (pintype "passive"))
    )
    (net (code "226") (name "IO205") (class "Default")
      (node (ref "IC1") (pin "R22") (pinfunction "IO_205_R22") (pintype "bidirectional"))
      (node (ref "JP234") (pin "1") (pinfunction "1_1") (pintype "passive"))
    )
    (net (code "227") (name "IO206") (class "Default")
      (node (ref "IC1") (pin "T3") (pinfunction "IO_206_T3") (pintype "bidirectional"))
      (node (ref "JP235") (pin "1") (pinfunction "1_1") (pintype "passive"))
    )
    (net (code "228") (name "IO207") (class "Default")
      (node (ref "IC1") (pin "T4") (pinfunction "IO_207_T4") (pintype "bidirectional"))
      (node (ref "JP236") (pin "1") (pinfunction "1_1") (pintype "passive"))
    )
    (net (code "229") (name "IO208") (class "Default")
      (node (ref "IC1") (pin "T5") (pinfunction "IO_208_T5") (pintype "bidirectional"))
      (node (ref "JP238") (pin "1") (pinfunction "1_1") (pintype "passive"))
    )
    (net (code "230") (name "IO209") (class "Default")
      (node (ref "IC1") (pin "T7") (pinfunction "IO_209_T7") (pintype "bidirectional"))
      (node (ref "JP237") (pin "1") (pinfunction "1_1") (pintype "passive"))
    )
    (net (code "231") (name "IO210") (class "Default")
      (node (ref "IC1") (pin "T8") (pinfunction "IO_210_T8") (pintype "bidirectional"))
      (node (ref "JP239") (pin "1") (pinfunction "1_1") (pintype "passive"))
    )
    (net (code "232") (name "IO211") (class "Default")
      (node (ref "IC1") (pin "T9") (pinfunction "IO_211_T9") (pintype "bidirectional"))
      (node (ref "JP240") (pin "1") (pinfunction "1_1") (pintype "passive"))
    )
    (net (code "233") (name "IO212") (class "Default")
      (node (ref "IC1") (pin "T10") (pinfunction "IO_212_T10") (pintype "bidirectional"))
      (node (ref "JP242") (pin "1") (pinfunction "1_1") (pintype "passive"))
    )
    (net (code "234") (name "IO213") (class "Default")
      (node (ref "IC1") (pin "T11") (pinfunction "IO_213_T11") (pintype "bidirectional"))
      (node (ref "JP241") (pin "1") (pinfunction "1_1") (pintype "passive"))
    )
    (net (code "235") (name "IO214") (class "Default")
      (node (ref "IC1") (pin "T12") (pinfunction "IO_214_T12") (pintype "bidirectional"))
      (node (ref "JP243") (pin "1") (pinfunction "1_1") (pintype "passive"))
    )
    (net (code "236") (name "IO215") (class "Default")
      (node (ref "IC1") (pin "T13") (pinfunction "IO_215_T13") (pintype "bidirectional"))
      (node (ref "JP244") (pin "1") (pinfunction "1_1") (pintype "passive"))
    )
    (net (code "237") (name "IO216") (class "Default")
      (node (ref "IC1") (pin "T14") (pinfunction "IO_216_T14") (pintype "bidirectional"))
      (node (ref "JP246") (pin "1") (pinfunction "1_1") (pintype "passive"))
    )
    (net (code "238") (name "IO217") (class "Default")
      (node (ref "IC1") (pin "T15") (pinfunction "IO_217_T15") (pintype "bidirectional"))
      (node (ref "JP245") (pin "1") (pinfunction "1_1") (pintype "passive"))
    )
    (net (code "239") (name "IO218") (class "Default")
      (node (ref "IC1") (pin "T16") (pinfunction "IO_218_T16") (pintype "bidirectional"))
      (node (ref "JP247") (pin "1") (pinfunction "1_1") (pintype "passive"))
    )
    (net (code "240") (name "IO219") (class "Default")
      (node (ref "IC1") (pin "T17") (pinfunction "IO_219_T17") (pintype "bidirectional"))
      (node (ref "JP248") (pin "1") (pinfunction "1_1") (pintype "passive"))
    )
    (net (code "241") (name "IO220") (class "Default")
      (node (ref "IC1") (pin "T18") (pinfunction "IO_220_T18") (pintype "bidirectional"))
      (node (ref "JP249") (pin "1") (pinfunction "1_1") (pintype "passive"))
    )
    (net (code "242") (name "IO221") (class "Default")
      (node (ref "IC1") (pin "U1") (pinfunction "IO_221_U1") (pintype "bidirectional"))
      (node (ref "JP250") (pin "1") (pinfunction "1_1") (pintype "passive"))
    )
    (net (code "243") (name "IO222") (class "Default")
      (node (ref "IC1") (pin "U2") (pinfunction "IO_222_U2") (pintype "bidirectional"))
      (node (ref "JP252") (pin "1") (pinfunction "1_1") (pintype "passive"))
    )
    (net (code "244") (name "IO223") (class "Default")
      (node (ref "IC1") (pin "U7") (pinfunction "IO_223_U7") (pintype "bidirectional"))
      (node (ref "JP251") (pin "1") (pinfunction "1_1") (pintype "passive"))
    )
    (net (code "245") (name "IO224") (class "Default")
      (node (ref "IC1") (pin "U8") (pinfunction "IO_224_U8") (pintype "bidirectional"))
      (node (ref "JP253") (pin "1") (pinfunction "1_1") (pintype "passive"))
    )
    (net (code "246") (name "IO225") (class "Default")
      (node (ref "IC1") (pin "U9") (pinfunction "IO_225_U9") (pintype "bidirectional"))
      (node (ref "JP254") (pin "1") (pinfunction "1_1") (pintype "passive"))
    )
    (net (code "247") (name "IO226") (class "Default")
      (node (ref "IC1") (pin "U10") (pinfunction "IO_226_U10") (pintype "bidirectional"))
      (node (ref "JP256") (pin "1") (pinfunction "1_1") (pintype "passive"))
    )
    (net (code "248") (name "IO227") (class "Default")
      (node (ref "IC1") (pin "U11") (pinfunction "IO_227_U11") (pintype "bidirectional"))
      (node (ref "JP255") (pin "1") (pinfunction "1_1") (pintype "passive"))
    )
    (net (code "249") (name "IO228") (class "Default")
      (node (ref "IC1") (pin "U12") (pinfunction "IO_228_U12") (pintype "bidirectional"))
      (node (ref "JP257") (pin "1") (pinfunction "1_1") (pintype "passive"))
    )
    (net (code "250") (name "IO229") (class "Default")
      (node (ref "IC1") (pin "U13") (pinfunction "IO_229_U13") (pintype "bidirectional"))
      (node (ref "JP258") (pin "1") (pinfunction "1_1") (pintype "passive"))
    )
    (net (code "251") (name "IO230") (class "Default")
      (node (ref "IC1") (pin "U14") (pinfunction "IO_230_U14") (pintype "bidirectional"))
      (node (ref "JP260") (pin "1") (pinfunction "1_1") (pintype "passive"))
    )
    (net (code "252") (name "IO231") (class "Default")
      (node (ref "IC1") (pin "U15") (pinfunction "IO_231_U15") (pintype "bidirectional"))
      (node (ref "JP259") (pin "1") (pinfunction "1_1") (pintype "passive"))
    )
    (net (code "253") (name "IO232") (class "Default")
      (node (ref "IC1") (pin "U16") (pinfunction "IO_232_U16") (pintype "bidirectional"))
      (node (ref "JP261") (pin "1") (pinfunction "1_1") (pintype "passive"))
    )
    (net (code "254") (name "IO233") (class "Default")
      (node (ref "IC1") (pin "U17") (pinfunction "IO_233_U17") (pintype "bidirectional"))
      (node (ref "JP262") (pin "1") (pinfunction "1_1") (pintype "passive"))
    )
    (net (code "255") (name "IO234") (class "Default")
      (node (ref "IC1") (pin "U19") (pinfunction "IO_234_U19") (pintype "bidirectional"))
      (node (ref "JP263") (pin "1") (pinfunction "1_1") (pintype "passive"))
    )
    (net (code "256") (name "IO235") (class "Default")
      (node (ref "IC1") (pin "U20") (pinfunction "IO_235_U20") (pintype "bidirectional"))
      (node (ref "JP264") (pin "1") (pinfunction "1_1") (pintype "passive"))
    )
    (net (code "257") (name "IO236") (class "Default")
      (node (ref "IC1") (pin "U21") (pinfunction "IO_236_U21") (pintype "bidirectional"))
      (node (ref "JP266") (pin "1") (pinfunction "1_1") (pintype "passive"))
    )
    (net (code "258") (name "IO237") (class "Default")
      (node (ref "IC1") (pin "U22") (pinfunction "IO_237_U22") (pintype "bidirectional"))
      (node (ref "JP265") (pin "1") (pinfunction "1_1") (pintype "passive"))
    )
    (net (code "259") (name "IO238") (class "Default")
      (node (ref "IC1") (pin "V1") (pinfunction "IO_238_V1") (pintype "bidirectional"))
      (node (ref "JP267") (pin "1") (pinfunction "1_1") (pintype "passive"))
    )
    (net (code "260") (name "IO239") (class "Default")
      (node (ref "IC1") (pin "V2") (pinfunction "IO_239_V2") (pintype "bidirectional"))
      (node (ref "JP268") (pin "1") (pinfunction "1_1") (pintype "passive"))
    )
    (net (code "261") (name "IO240") (class "Default")
      (node (ref "IC1") (pin "V3") (pinfunction "IO_240_V3") (pintype "bidirectional"))
      (node (ref "JP270") (pin "1") (pinfunction "1_1") (pintype "passive"))
    )
    (net (code "262") (name "IO241") (class "Default")
      (node (ref "IC1") (pin "V4") (pinfunction "IO_241_V4") (pintype "bidirectional"))
      (node (ref "JP269") (pin "1") (pinfunction "1_1") (pintype "passive"))
    )
    (net (code "263") (name "IO242") (class "Default")
      (node (ref "IC1") (pin "V5") (pinfunction "IO_242_V5") (pintype "bidirectional"))
      (node (ref "JP271") (pin "1") (pinfunction "1_1") (pintype "passive"))
    )
    (net (code "264") (name "IO243") (class "Default")
      (node (ref "IC1") (pin "V6") (pinfunction "IO_243_V6") (pintype "bidirectional"))
      (node (ref "JP272") (pin "1") (pinfunction "1_1") (pintype "passive"))
    )
    (net (code "265") (name "IO244") (class "Default")
      (node (ref "IC1") (pin "V7") (pinfunction "IO_244_V7") (pintype "bidirectional"))
      (node (ref "JP274") (pin "1") (pinfunction "1_1") (pintype "passive"))
    )
    (net (code "266") (name "IO245") (class "Default")
      (node (ref "IC1") (pin "V8") (pinfunction "IO_245_V8") (pintype "bidirectional"))
      (node (ref "JP273") (pin "1") (pinfunction "1_1") (pintype "passive"))
    )
    (net (code "267") (name "IO246") (class "Default")
      (node (ref "IC1") (pin "V9") (pinfunction "IO_246_V9") (pintype "bidirectional"))
      (node (ref "JP275") (pin "1") (pinfunction "1_1") (pintype "passive"))
    )
    (net (code "268") (name "IO247") (class "Default")
      (node (ref "IC1") (pin "V10") (pinfunction "IO_247_V10") (pintype "bidirectional"))
      (node (ref "JP276") (pin "1") (pinfunction "1_1") (pintype "passive"))
    )
    (net (code "269") (name "IO248") (class "Default")
      (node (ref "IC1") (pin "V11") (pinfunction "IO_248_V11") (pintype "bidirectional"))
      (node (ref "JP277") (pin "1") (pinfunction "1_1") (pintype "passive"))
    )
    (net (code "270") (name "IO249") (class "Default")
      (node (ref "IC1") (pin "V12") (pinfunction "IO_249_V12") (pintype "bidirectional"))
      (node (ref "JP278") (pin "1") (pinfunction "1_1") (pintype "passive"))
    )
    (net (code "271") (name "IO250") (class "Default")
      (node (ref "IC1") (pin "V13") (pinfunction "IO_250_V13") (pintype "bidirectional"))
      (node (ref "JP280") (pin "1") (pinfunction "1_1") (pintype "passive"))
    )
    (net (code "272") (name "IO251") (class "Default")
      (node (ref "IC1") (pin "V14") (pinfunction "IO_251_V14") (pintype "bidirectional"))
      (node (ref "JP279") (pin "1") (pinfunction "1_1") (pintype "passive"))
    )
    (net (code "273") (name "IO252") (class "Default")
      (node (ref "IC1") (pin "V15") (pinfunction "IO_252_V15") (pintype "bidirectional"))
      (node (ref "JP281") (pin "1") (pinfunction "1_1") (pintype "passive"))
    )
    (net (code "274") (name "IO253") (class "Default")
      (node (ref "IC1") (pin "V16") (pinfunction "IO_253_V16") (pintype "bidirectional"))
      (node (ref "JP282") (pin "1") (pinfunction "1_1") (pintype "passive"))
    )
    (net (code "275") (name "IO254") (class "Default")
      (node (ref "IC1") (pin "V21") (pinfunction "IO_254_V21") (pintype "bidirectional"))
      (node (ref "JP284") (pin "1") (pinfunction "1_1") (pintype "passive"))
    )
    (net (code "276") (name "IO255") (class "Default")
      (node (ref "IC1") (pin "V22") (pinfunction "IO_255_V22") (pintype "bidirectional"))
      (node (ref "JP283") (pin "1") (pinfunction "1_1") (pintype "passive"))
    )
    (net (code "277") (name "IO256") (class "Default")
      (node (ref "IC1") (pin "W1") (pinfunction "IO_256_W1") (pintype "bidirectional"))
      (node (ref "JP285") (pin "1") (pinfunction "1_1") (pintype "passive"))
    )
    (net (code "278") (name "IO257") (class "Default")
      (node (ref "IC1") (pin "W2") (pinfunction "IO_257_W2") (pintype "bidirectional"))
      (node (ref "JP286") (pin "1") (pinfunction "1_1") (pintype "passive"))
    )
    (net (code "279") (name "IO258") (class "Default")
      (node (ref "IC1") (pin "W6") (pinfunction "IO_258_W6") (pintype "bidirectional"))
      (node (ref "JP288") (pin "1") (pinfunction "1_1") (pintype "passive"))
    )
    (net (code "280") (name "IO259") (class "Default")
      (node (ref "IC1") (pin "W7") (pinfunction "IO_259_W7") (pintype "bidirectional"))
      (node (ref "JP287") (pin "1") (pinfunction "1_1") (pintype "passive"))
    )
    (net (code "281") (name "IO260") (class "Default")
      (node (ref "IC1") (pin "W8") (pinfunction "IO_260_W8") (pintype "bidirectional"))
      (node (ref "JP289") (pin "1") (pinfunction "1_1") (pintype "passive"))
    )
    (net (code "282") (name "IO261") (class "Default")
      (node (ref "IC1") (pin "W10") (pinfunction "IO_261_W10") (pintype "bidirectional"))
      (node (ref "JP290") (pin "1") (pinfunction "1_1") (pintype "passive"))
    )
    (net (code "283") (name "IO262") (class "Default")
      (node (ref "IC1") (pin "W13") (pinfunction "IO_262_W13") (pintype "bidirectional"))
      (node (ref "JP291") (pin "1") (pinfunction "1_1") (pintype "passive"))
    )
    (net (code "284") (name "IO263") (class "Default")
      (node (ref "IC1") (pin "W14") (pinfunction "IO_263_W14") (pintype "bidirectional"))
      (node (ref "JP292") (pin "1") (pinfunction "1_1") (pintype "passive"))
    )
    (net (code "285") (name "IO264") (class "Default")
      (node (ref "IC1") (pin "W15") (pinfunction "IO_264_W15") (pintype "bidirectional"))
      (node (ref "JP294") (pin "1") (pinfunction "1_1") (pintype "passive"))
    )
    (net (code "286") (name "IO265") (class "Default")
      (node (ref "IC1") (pin "W17") (pinfunction "IO_265_W17") (pintype "bidirectional"))
      (node (ref "JP293") (pin "1") (pinfunction "1_1") (pintype "passive"))
    )
    (net (code "287") (name "IO266") (class "Default")
      (node (ref "IC1") (pin "W19") (pinfunction "IO_266_W19") (pintype "bidirectional"))
      (node (ref "JP295") (pin "1") (pinfunction "1_1") (pintype "passive"))
    )
    (net (code "288") (name "IO267") (class "Default")
      (node (ref "IC1") (pin "W20") (pinfunction "IO_267_W20") (pintype "bidirectional"))
      (node (ref "JP296") (pin "1") (pinfunction "1_1") (pintype "passive"))
    )
    (net (code "289") (name "IO268") (class "Default")
      (node (ref "IC1") (pin "W21") (pinfunction "IO_268_W21") (pintype "bidirectional"))
      (node (ref "JP298") (pin "1") (pinfunction "1_1") (pintype "passive"))
    )
    (net (code "290") (name "IO269") (class "Default")
      (node (ref "IC1") (pin "W22") (pinfunction "IO_269_W22") (pintype "bidirectional"))
      (node (ref "JP297") (pin "1") (pinfunction "1_1") (pintype "passive"))
    )
    (net (code "291") (name "IO270") (class "Default")
      (node (ref "IC1") (pin "Y1") (pinfunction "IO_270_Y1") (pintype "bidirectional"))
      (node (ref "JP299") (pin "1") (pinfunction "1_1") (pintype "passive"))
    )
    (net (code "292") (name "IO271") (class "Default")
      (node (ref "IC1") (pin "Y2") (pinfunction "IO_271_Y2") (pintype "bidirectional"))
      (node (ref "JP300") (pin "1") (pinfunction "1_1") (pintype "passive"))
    )
    (net (code "293") (name "IO272") (class "Default")
      (node (ref "IC1") (pin "Y3") (pinfunction "IO_272_Y3") (pintype "bidirectional"))
      (node (ref "JP302") (pin "1") (pinfunction "1_1") (pintype "passive"))
    )
    (net (code "294") (name "IO273") (class "Default")
      (node (ref "IC1") (pin "Y4") (pinfunction "IO_273_Y4") (pintype "bidirectional"))
      (node (ref "JP301") (pin "1") (pinfunction "1_1") (pintype "passive"))
    )
    (net (code "295") (name "IO274") (class "Default")
      (node (ref "IC1") (pin "Y6") (pinfunction "IO_274_Y6") (pintype "bidirectional"))
      (node (ref "JP303") (pin "1") (pinfunction "1_1") (pintype "passive"))
    )
    (net (code "296") (name "IO275") (class "Default")
      (node (ref "IC1") (pin "Y7") (pinfunction "IO_275_Y7") (pintype "bidirectional"))
      (node (ref "JP304") (pin "1") (pinfunction "1_1") (pintype "passive"))
    )
    (net (code "297") (name "IO276") (class "Default")
      (node (ref "IC1") (pin "Y8") (pinfunction "IO_276_Y8") (pintype "bidirectional"))
      (node (ref "JP305") (pin "1") (pinfunction "1_1") (pintype "passive"))
    )
    (net (code "298") (name "IO277") (class "Default")
      (node (ref "IC1") (pin "Y10") (pinfunction "IO_277_Y10") (pintype "bidirectional"))
      (node (ref "JP306") (pin "1") (pinfunction "1_1") (pintype "passive"))
    )
    (net (code "299") (name "IO278") (class "Default")
      (node (ref "IC1") (pin "Y13") (pinfunction "IO_278_Y13") (pintype "bidirectional"))
      (node (ref "JP308") (pin "1") (pinfunction "1_1") (pintype "passive"))
    )
    (net (code "300") (name "IO279") (class "Default")
      (node (ref "IC1") (pin "Y17") (pinfunction "IO_279_Y17") (pintype "bidirectional"))
      (node (ref "JP307") (pin "1") (pinfunction "1_1") (pintype "passive"))
    )
    (net (code "301") (name "IO280") (class "Default")
      (node (ref "IC1") (pin "Y21") (pinfunction "IO_280_Y21") (pintype "bidirectional"))
      (node (ref "JP309") (pin "1") (pinfunction "1_1") (pintype "passive"))
    )
    (net (code "302") (name "IO281") (class "Default")
      (node (ref "IC1") (pin "Y22") (pinfunction "IO_281_Y22") (pintype "bidirectional"))
      (node (ref "JP310") (pin "1") (pinfunction "1_1") (pintype "passive"))
    )
    (net (code "303") (name "IO282") (class "Default")
      (node (ref "IC1") (pin "AA1") (pinfunction "IO_282_AA1") (pintype "bidirectional"))
      (node (ref "JP312") (pin "1") (pinfunction "1_1") (pintype "passive"))
    )
    (net (code "304") (name "IO283") (class "Default")
      (node (ref "IC1") (pin "AA3") (pinfunction "IO_283_AA3") (pintype "bidirectional"))
      (node (ref "JP311") (pin "1") (pinfunction "1_1") (pintype "passive"))
    )
    (net (code "305") (name "IO284") (class "Default")
      (node (ref "IC1") (pin "AA4") (pinfunction "IO_284_AA4") (pintype "bidirectional"))
      (node (ref "JP313") (pin "1") (pinfunction "1_1") (pintype "passive"))
    )
    (net (code "306") (name "IO285") (class "Default")
      (node (ref "IC1") (pin "AA5") (pinfunction "IO_285_AA5") (pintype "bidirectional"))
      (node (ref "JP314") (pin "1") (pinfunction "1_1") (pintype "passive"))
    )
    (net (code "307") (name "IO286") (class "Default")
      (node (ref "IC1") (pin "AA7") (pinfunction "IO_286_AA7") (pintype "bidirectional"))
      (node (ref "JP316") (pin "1") (pinfunction "1_1") (pintype "passive"))
    )
    (net (code "308") (name "IO287") (class "Default")
      (node (ref "IC1") (pin "AA8") (pinfunction "IO_287_AA8") (pintype "bidirectional"))
      (node (ref "JP315") (pin "1") (pinfunction "1_1") (pintype "passive"))
    )
    (net (code "309") (name "IO288") (class "Default")
      (node (ref "IC1") (pin "AA9") (pinfunction "IO_288_AA9") (pintype "bidirectional"))
      (node (ref "JP317") (pin "1") (pinfunction "1_1") (pintype "passive"))
    )
    (net (code "310") (name "IO289") (class "Default")
      (node (ref "IC1") (pin "AA10") (pinfunction "IO_289_AA10") (pintype "bidirectional"))
      (node (ref "JP318") (pin "1") (pinfunction "1_1") (pintype "passive"))
    )
    (net (code "311") (name "IO290") (class "Default")
      (node (ref "IC1") (pin "AA13") (pinfunction "IO_290_AA13") (pintype "bidirectional"))
      (node (ref "JP319") (pin "1") (pinfunction "1_1") (pintype "passive"))
    )
    (net (code "312") (name "IO291") (class "Default")
      (node (ref "IC1") (pin "AA14") (pinfunction "IO_291_AA14") (pintype "bidirectional"))
      (node (ref "JP320") (pin "1") (pinfunction "1_1") (pintype "passive"))
    )
    (net (code "313") (name "IO292") (class "Default")
      (node (ref "IC1") (pin "AA15") (pinfunction "IO_292_AA15") (pintype "bidirectional"))
      (node (ref "JP322") (pin "1") (pinfunction "1_1") (pintype "passive"))
    )
    (net (code "314") (name "IO293") (class "Default")
      (node (ref "IC1") (pin "AA16") (pinfunction "IO_293_AA16") (pintype "bidirectional"))
      (node (ref "JP321") (pin "1") (pinfunction "1_1") (pintype "passive"))
    )
    (net (code "315") (name "IO294") (class "Default")
      (node (ref "IC1") (pin "AA17") (pinfunction "IO_294_AA17") (pintype "bidirectional"))
      (node (ref "JP323") (pin "1") (pinfunction "1_1") (pintype "passive"))
    )
    (net (code "316") (name "IO295") (class "Default")
      (node (ref "IC1") (pin "AA18") (pinfunction "IO_295_AA18") (pintype "bidirectional"))
      (node (ref "JP324") (pin "1") (pinfunction "1_1") (pintype "passive"))
    )
    (net (code "317") (name "IO296") (class "Default")
      (node (ref "IC1") (pin "AA19") (pinfunction "IO_296_AA19") (pintype "bidirectional"))
      (node (ref "JP326") (pin "1") (pinfunction "1_1") (pintype "passive"))
    )
    (net (code "318") (name "IO297") (class "Default")
      (node (ref "IC1") (pin "AA20") (pinfunction "IO_297_AA20") (pintype "bidirectional"))
      (node (ref "JP325") (pin "1") (pinfunction "1_1") (pintype "passive"))
    )
    (net (code "319") (name "IO298") (class "Default")
      (node (ref "IC1") (pin "AA21") (pinfunction "IO_298_AA21") (pintype "bidirectional"))
      (node (ref "JP327") (pin "1") (pinfunction "1_1") (pintype "passive"))
    )
    (net (code "320") (name "IO299") (class "Default")
      (node (ref "IC1") (pin "AB3") (pinfunction "IO_299_AB3") (pintype "bidirectional"))
      (node (ref "JP328") (pin "1") (pinfunction "1_1") (pintype "passive"))
    )
    (net (code "321") (name "IO300") (class "Default")
      (node (ref "IC1") (pin "AB4") (pinfunction "IO_300_AB4") (pintype "bidirectional"))
      (node (ref "JP330") (pin "1") (pinfunction "1_1") (pintype "passive"))
    )
    (net (code "322") (name "IO301") (class "Default")
      (node (ref "IC1") (pin "AB5") (pinfunction "IO_301_AB5") (pintype "bidirectional"))
      (node (ref "JP329") (pin "1") (pinfunction "1_1") (pintype "passive"))
    )
    (net (code "323") (name "IO302") (class "Default")
      (node (ref "IC1") (pin "AB7") (pinfunction "IO_302_AB7") (pintype "bidirectional"))
      (node (ref "JP331") (pin "1") (pinfunction "1_1") (pintype "passive"))
    )
    (net (code "324") (name "IO303") (class "Default")
      (node (ref "IC1") (pin "AB8") (pinfunction "IO_303_AB8") (pintype "bidirectional"))
      (node (ref "JP332") (pin "1") (pinfunction "1_1") (pintype "passive"))
    )
    (net (code "325") (name "IO304") (class "Default")
      (node (ref "IC1") (pin "AB9") (pinfunction "IO_304_AB9") (pintype "bidirectional"))
      (node (ref "JP333") (pin "1") (pinfunction "1_1") (pintype "passive"))
    )
    (net (code "326") (name "IO305") (class "Default")
      (node (ref "IC1") (pin "AB10") (pinfunction "IO_305_AB10") (pintype "bidirectional"))
      (node (ref "JP334") (pin "1") (pinfunction "1_1") (pintype "passive"))
    )
    (net (code "327") (name "IO306") (class "Default")
      (node (ref "IC1") (pin "AB13") (pinfunction "IO_306_AB13") (pintype "bidirectional"))
      (node (ref "JP336") (pin "1") (pinfunction "1_1") (pintype "passive"))
    )
    (net (code "328") (name "IO307") (class "Default")
      (node (ref "IC1") (pin "AB14") (pinfunction "IO_307_AB14") (pintype "bidirectional"))
      (node (ref "JP335") (pin "1") (pinfunction "1_1") (pintype "passive"))
    )
    (net (code "329") (name "IO308") (class "Default")
      (node (ref "IC1") (pin "AB15") (pinfunction "IO_308_AB15") (pintype "bidirectional"))
      (node (ref "JP337") (pin "1") (pinfunction "1_1") (pintype "passive"))
    )
    (net (code "330") (name "IO309") (class "Default")
      (node (ref "IC1") (pin "AB16") (pinfunction "IO_309_AB16") (pintype "bidirectional"))
      (node (ref "JP338") (pin "1") (pinfunction "1_1") (pintype "passive"))
    )
    (net (code "331") (name "IO310") (class "Default")
      (node (ref "IC1") (pin "AB17") (pinfunction "IO_310_AB17") (pintype "bidirectional"))
      (node (ref "JP340") (pin "1") (pinfunction "1_1") (pintype "passive"))
    )
    (net (code "332") (name "IO311") (class "Default")
      (node (ref "IC1") (pin "AB18") (pinfunction "IO_311_AB18") (pintype "bidirectional"))
      (node (ref "JP339") (pin "1") (pinfunction "1_1") (pintype "passive"))
    )
    (net (code "333") (name "IO312") (class "Default")
      (node (ref "IC1") (pin "AB19") (pinfunction "IO_312_AB19") (pintype "bidirectional"))
      (node (ref "JP341") (pin "1") (pinfunction "1_1") (pintype "passive"))
    )
    (net (code "334") (name "IO313") (class "Default")
      (node (ref "IC1") (pin "AB20") (pinfunction "IO_313_AB20") (pintype "bidirectional"))
      (node (ref "JP342") (pin "1") (pinfunction "1_1") (pintype "passive"))
    )
    (net (code "335") (name "MSEL0") (class "Default")
      (node (ref "IC1") (pin "M17") (pinfunction "MSEL0_M17") (pintype "bidirectional"))
      (node (ref "R6") (pin "P$1") (pinfunction "P$1_P$1") (pintype "bidirectional"))
    )
    (net (code "336") (name "MSEL1") (class "Default")
      (node (ref "IC1") (pin "L18") (pinfunction "MSEL1_L18") (pintype "bidirectional"))
      (node (ref "R7") (pin "P$1") (pinfunction "P$1_P$1") (pintype "bidirectional"))
    )
    (net (code "337") (name "MSEL2") (class "Default")
      (node (ref "IC1") (pin "L17") (pinfunction "MSEL2_L17") (pintype "bidirectional"))
      (node (ref "R8") (pin "P$1") (pinfunction "P$1_P$1") (pintype "bidirectional"))
    )
    (net (code "338") (name "MSEL3") (class "Default")
      (node (ref "IC1") (pin "K20") (pinfunction "MSEL3_K20") (pintype "bidirectional"))
      (node (ref "R9") (pin "P$1") (pinfunction "P$1_P$1") (pintype "bidirectional"))
    )
    (net (code "339") (name "NCE") (class "Default")
      (node (ref "IC1") (pin "L3") (pinfunction "NCE_L3") (pintype "bidirectional"))
      (node (ref "R4") (pin "P$1") (pinfunction "P$1_P$1") (pintype "bidirectional"))
    )
    (net (code "340") (name "NCONFIG") (class "Default")
      (node (ref "IC1") (pin "K5") (pinfunction "NCONFIG_K5") (pintype "bidirectional"))
      (node (ref "R2") (pin "P$1") (pinfunction "P$1_P$1") (pintype "bidirectional"))
      (node (ref "SW1") (pin "2") (pinfunction "A1_2") (pintype "bidirectional"))
    )
    (net (code "341") (name "NCSO") (class "Default")
      (node (ref "IC1") (pin "E2") (pinfunction "IO_65_E2") (pintype "bidirectional"))
      (node (ref "IC2") (pin "1") (pinfunction "NCS_1") (pintype "bidirectional"))
      (node (ref "JP54") (pin "1") (pinfunction "1_1") (pintype "passive"))
    )
    (net (code "342") (name "NSTATUS") (class "Default")
      (node (ref "IC1") (pin "K6") (pinfunction "NSTATUS_K6") (pintype "bidirectional"))
      (node (ref "R5") (pin "P$1") (pinfunction "P$1_P$1") (pintype "bidirectional"))
    )
    (net (code "343") (name "Net-(LED33-PadA)") (class "Default")
      (node (ref "LED33") (pin "A") (pinfunction "A_A") (pintype "passive"))
      (node (ref "R45") (pin "P$2") (pinfunction "P$2_P$2") (pintype "bidirectional"))
    )
    (net (code "344") (name "Net-(LED34-PadA)") (class "Default")
      (node (ref "LED34") (pin "A") (pinfunction "A_A") (pintype "passive"))
      (node (ref "R44") (pin "P$2") (pinfunction "P$2_P$2") (pintype "bidirectional"))
    )
    (net (code "345") (name "Net-(LED35-PadA)") (class "Default")
      (node (ref "LED35") (pin "A") (pinfunction "A_A") (pintype "passive"))
      (node (ref "R43") (pin "P$2") (pinfunction "P$2_P$2") (pintype "bidirectional"))
    )
    (net (code "346") (name "Net-(LED36-PadA)") (class "Default")
      (node (ref "LED36") (pin "A") (pinfunction "A_A") (pintype "passive"))
      (node (ref "R42") (pin "P$2") (pinfunction "P$2_P$2") (pintype "bidirectional"))
    )
    (net (code "347") (name "Net-(LED37-PadA)") (class "Default")
      (node (ref "LED37") (pin "A") (pinfunction "A_A") (pintype "passive"))
      (node (ref "R41") (pin "P$2") (pinfunction "P$2_P$2") (pintype "bidirectional"))
    )
    (net (code "348") (name "Net-(LED38-PadA)") (class "Default")
      (node (ref "LED38") (pin "A") (pinfunction "A_A") (pintype "passive"))
      (node (ref "R40") (pin "P$2") (pinfunction "P$2_P$2") (pintype "bidirectional"))
    )
    (net (code "349") (name "Net-(LED39-PadA)") (class "Default")
      (node (ref "LED39") (pin "A") (pinfunction "A_A") (pintype "passive"))
      (node (ref "R39") (pin "P$2") (pinfunction "P$2_P$2") (pintype "bidirectional"))
    )
    (net (code "350") (name "Net-(LED40-PadA)") (class "Default")
      (node (ref "LED40") (pin "A") (pinfunction "A_A") (pintype "passive"))
      (node (ref "R38") (pin "P$2") (pinfunction "P$2_P$2") (pintype "bidirectional"))
    )
    (net (code "351") (name "TCK") (class "Default")
      (node (ref "IC1") (pin "L2") (pinfunction "TCK_L2") (pintype "bidirectional"))
      (node (ref "J1") (pin "1") (pinfunction "1_1") (pintype "passive"))
    )
    (net (code "352") (name "TDI") (class "Default")
      (node (ref "IC1") (pin "L5") (pinfunction "TDI_L5") (pintype "bidirectional"))
      (node (ref "J1") (pin "9") (pinfunction "9_9") (pintype "passive"))
    )
    (net (code "353") (name "TDO") (class "Default")
      (node (ref "IC1") (pin "L4") (pinfunction "TDO_L4") (pintype "bidirectional"))
      (node (ref "J1") (pin "3") (pinfunction "3_3") (pintype "passive"))
    )
    (net (code "354") (name "TMS") (class "Default")
      (node (ref "IC1") (pin "L1") (pinfunction "TMS_L1") (pintype "bidirectional"))
      (node (ref "J1") (pin "5") (pinfunction "5_5") (pintype "passive"))
    )
    (net (code "355") (name "VCCA") (class "Default")
      (node (ref "C26") (pin "2") (pinfunction "2_2") (pintype "passive"))
      (node (ref "IC1") (pin "F18") (pinfunction "VCCA2_F18") (pintype "bidirectional"))
      (node (ref "IC1") (pin "G6") (pinfunction "VCCA3_G6") (pintype "bidirectional"))
      (node (ref "IC1") (pin "T6") (pinfunction "VCCA1_T6") (pintype "bidirectional"))
      (node (ref "IC1") (pin "U18") (pinfunction "VCCA4_U18") (pintype "bidirectional"))
      (node (ref "R20") (pin "P$2") (pinfunction "P$2_P$2") (pintype "bidirectional"))
    )
    (net (code "356") (name "VCCINT") (class "Default")
      (node (ref "C24") (pin "2") (pinfunction "2_2") (pintype "passive"))
      (node (ref "IC1") (pin "G12") (pinfunction "VCCINT_1_G12") (pintype "bidirectional"))
      (node (ref "IC1") (pin "H9") (pinfunction "VCCINT_2_H9") (pintype "bidirectional"))
      (node (ref "IC1") (pin "J10") (pinfunction "VCCINT_3_J10") (pintype "bidirectional"))
      (node (ref "IC1") (pin "J11") (pinfunction "VCCINT_4_J11") (pintype "bidirectional"))
      (node (ref "IC1") (pin "J12") (pinfunction "VCCINT_5_J12") (pintype "bidirectional"))
      (node (ref "IC1") (pin "J13") (pinfunction "VCCINT_6_J13") (pintype "bidirectional"))
      (node (ref "IC1") (pin "J14") (pinfunction "VCCINT_7_J14") (pintype "bidirectional"))
      (node (ref "IC1") (pin "J16") (pinfunction "VCCINT_8_J16") (pintype "bidirectional"))
      (node (ref "IC1") (pin "K14") (pinfunction "VCCINT_10_K14") (pintype "bidirectional"))
      (node (ref "IC1") (pin "K15") (pinfunction "VCCINT_11_K15") (pintype "bidirectional"))
      (node (ref "IC1") (pin "K9") (pinfunction "VCCINT_9_K9") (pintype "bidirectional"))
      (node (ref "IC1") (pin "L14") (pinfunction "VCCINT_13_L14") (pintype "bidirectional"))
      (node (ref "IC1") (pin "L16") (pinfunction "VCCINT_14_L16") (pintype "bidirectional"))
      (node (ref "IC1") (pin "L9") (pinfunction "VCCINT_12_L9") (pintype "bidirectional"))
      (node (ref "IC1") (pin "M14") (pinfunction "VCCINT_16_M14") (pintype "bidirectional"))
      (node (ref "IC1") (pin "M15") (pinfunction "VCCINT_17_M15") (pintype "bidirectional"))
      (node (ref "IC1") (pin "M9") (pinfunction "VCCINT_15_M9") (pintype "bidirectional"))
      (node (ref "IC1") (pin "N14") (pinfunction "VCCINT_19_N14") (pintype "bidirectional"))
      (node (ref "IC1") (pin "N9") (pinfunction "VCCINT_18_N9") (pintype "bidirectional"))
      (node (ref "IC1") (pin "P10") (pinfunction "VCCINT_21_P10") (pintype "bidirectional"))
      (node (ref "IC1") (pin "P11") (pinfunction "VCCINT_22_P11") (pintype "bidirectional"))
      (node (ref "IC1") (pin "P12") (pinfunction "VCCINT_23_P12") (pintype "bidirectional"))
      (node (ref "IC1") (pin "P13") (pinfunction "VCCINT_24_P13") (pintype "bidirectional"))
      (node (ref "IC1") (pin "P14") (pinfunction "VCCINT_25_P14") (pintype "bidirectional"))
      (node (ref "IC1") (pin "P9") (pinfunction "VCCINT_20_P9") (pintype "bidirectional"))
      (node (ref "IC1") (pin "R10") (pinfunction "VCCINT_27_R10") (pintype "bidirectional"))
      (node (ref "IC1") (pin "R12") (pinfunction "VCCINT_28_R12") (pintype "bidirectional"))
      (node (ref "IC1") (pin "R8") (pinfunction "VCCINT_26_R8") (pintype "bidirectional"))
      (node (ref "R18") (pin "P$2") (pinfunction "P$2_P$2") (pintype "bidirectional"))
    )
    (net (code "357") (name "VCCIO") (class "Default")
      (node (ref "C16") (pin "2") (pinfunction "2_2") (pintype "passive"))
      (node (ref "C17") (pin "2") (pinfunction "2_2") (pintype "passive"))
      (node (ref "C18") (pin "2") (pinfunction "2_2") (pintype "passive"))
      (node (ref "C19") (pin "2") (pinfunction "2_2") (pintype "passive"))
      (node (ref "C20") (pin "2") (pinfunction "2_2") (pintype "passive"))
      (node (ref "C21") (pin "2") (pinfunction "2_2") (pintype "passive"))
      (node (ref "C22") (pin "2") (pinfunction "2_2") (pintype "passive"))
      (node (ref "C23") (pin "2") (pinfunction "2_2") (pintype "passive"))
      (node (ref "IC1") (pin "A2") (pinfunction "VCCIO8_1_A2") (pintype "bidirectional"))
      (node (ref "IC1") (pin "A21") (pinfunction "VCCIO7_1_A21") (pintype "bidirectional"))
      (node (ref "IC1") (pin "AA6") (pinfunction "VCCIO3_4_AA6") (pintype "bidirectional"))
      (node (ref "IC1") (pin "AB2") (pinfunction "VCCIO3_5_AB2") (pintype "bidirectional"))
      (node (ref "IC1") (pin "AB21") (pinfunction "VCCIO4_5_AB21") (pintype "bidirectional"))
      (node (ref "IC1") (pin "D11") (pinfunction "VCCIO8_4_D11") (pintype "bidirectional"))
      (node (ref "IC1") (pin "D12") (pinfunction "VCCIO7_2_D12") (pintype "bidirectional"))
      (node (ref "IC1") (pin "D14") (pinfunction "VCCIO7_3_D14") (pintype "bidirectional"))
      (node (ref "IC1") (pin "D16") (pinfunction "VCCIO7_4_D16") (pintype "bidirectional"))
      (node (ref "IC1") (pin "D18") (pinfunction "VCCIO7_5_D18") (pintype "bidirectional"))
      (node (ref "IC1") (pin "D4") (pinfunction "VCCIO1_1_D4") (pintype "bidirectional"))
      (node (ref "IC1") (pin "D5") (pinfunction "VCCIO8_2_D5") (pintype "bidirectional"))
      (node (ref "IC1") (pin "D9") (pinfunction "VCCIO8_3_D9") (pintype "bidirectional"))
      (node (ref "IC1") (pin "E19") (pinfunction "VCCIO6_1_E19") (pintype "bidirectional"))
      (node (ref "IC1") (pin "E8") (pinfunction "VCCIO8_5_E8") (pintype "bidirectional"))
      (node (ref "IC1") (pin "F4") (pinfunction "VCCIO1_2_F4") (pintype "bidirectional"))
      (node (ref "IC1") (pin "G19") (pinfunction "VCCIO6_2_G19") (pintype "bidirectional"))
      (node (ref "IC1") (pin "H4") (pinfunction "VCCIO1_3_H4") (pintype "bidirectional"))
      (node (ref "IC1") (pin "J20") (pinfunction "VCCIO6_3_J20") (pintype "bidirectional"))
      (node (ref "IC1") (pin "K4") (pinfunction "VCCIO1_4_K4") (pintype "bidirectional"))
      (node (ref "IC1") (pin "L19") (pinfunction "VCCIO6_4_L19") (pintype "bidirectional"))
      (node (ref "IC1") (pin "N4") (pinfunction "VCCIO2_1_N4") (pintype "bidirectional"))
      (node (ref "IC1") (pin "P18") (pinfunction "VCCIO5_1_P18") (pintype "bidirectional"))
      (node (ref "IC1") (pin "R4") (pinfunction "VCCIO2_2_R4") (pintype "bidirectional"))
      (node (ref "IC1") (pin "T19") (pinfunction "VCCIO5_2_T19") (pintype "bidirectional"))
      (node (ref "IC1") (pin "U4") (pinfunction "VCCIO2_3_U4") (pintype "bidirectional"))
      (node (ref "IC1") (pin "V19") (pinfunction "VCCIO5_3_V19") (pintype "bidirectional"))
      (node (ref "IC1") (pin "W11") (pinfunction "VCCIO3_3_W11") (pintype "bidirectional"))
      (node (ref "IC1") (pin "W12") (pinfunction "VCCIO4_1_W12") (pintype "bidirectional"))
      (node (ref "IC1") (pin "W16") (pinfunction "VCCIO4_2_W16") (pintype "bidirectional"))
      (node (ref "IC1") (pin "W18") (pinfunction "VCCIO4_3_W18") (pintype "bidirectional"))
      (node (ref "IC1") (pin "W4") (pinfunction "VCCIO2_4_W4") (pintype "bidirectional"))
      (node (ref "IC1") (pin "W5") (pinfunction "VCCIO3_1_W5") (pintype "bidirectional"))
      (node (ref "IC1") (pin "W9") (pinfunction "VCCIO3_2_W9") (pintype "bidirectional"))
      (node (ref "IC1") (pin "Y14") (pinfunction "VCCIO4_4_Y14") (pintype "bidirectional"))
      (node (ref "IC1") (pin "Y19") (pinfunction "VCCIO5_4_Y19") (pintype "bidirectional"))
      (node (ref "R17") (pin "P$2") (pinfunction "P$2_P$2") (pintype "bidirectional"))
    )
    (net (code "358") (name "VCCPLL") (class "Default")
      (node (ref "C25") (pin "2") (pinfunction "2_2") (pintype "passive"))
      (node (ref "IC1") (pin "E17") (pinfunction "VCCD_PLL2_E17") (pintype "bidirectional"))
      (node (ref "IC1") (pin "F6") (pinfunction "VCCD_PLL3_F6") (pintype "bidirectional"))
      (node (ref "IC1") (pin "U6") (pinfunction "VCCD_PLL1_U6") (pintype "bidirectional"))
      (node (ref "IC1") (pin "V17") (pinfunction "VCCD_PLL4_V17") (pintype "bidirectional"))
      (node (ref "R19") (pin "P$2") (pinfunction "P$2_P$2") (pintype "bidirectional"))
    )
    (net (code "359") (name "unconnected-(J1-Pad6)") (class "Default")
      (node (ref "J1") (pin "6") (pinfunction "6_6") (pintype "passive"))
    )
    (net (code "360") (name "unconnected-(J1-Pad7)") (class "Default")
      (node (ref "J1") (pin "7") (pinfunction "7_7") (pintype "passive"))
    )
    (net (code "361") (name "unconnected-(J1-Pad8)") (class "Default")
      (node (ref "J1") (pin "8") (pinfunction "8_8") (pintype "passive"))
    )
    (net (code "362") (name "unconnected-(SW1-A0-Pad1)") (class "Default")
      (node (ref "SW1") (pin "1") (pinfunction "A0_1") (pintype "bidirectional"))
    )
    (net (code "363") (name "unconnected-(SW1-B0-Pad3)") (class "Default")
      (node (ref "SW1") (pin "3") (pinfunction "B0_3") (pintype "bidirectional"))
    )
    (net (code "364") (name "unconnected-(SW2-A0-Pad1)") (class "Default")
      (node (ref "SW2") (pin "1") (pinfunction "A0_1") (pintype "bidirectional"))
    )
    (net (code "365") (name "unconnected-(SW2-B0-Pad3)") (class "Default")
      (node (ref "SW2") (pin "3") (pinfunction "B0_3") (pintype "bidirectional"))
    )
    (net (code "366") (name "unconnected-(Y1-EN-Pad1)") (class "Default")
      (node (ref "Y1") (pin "1") (pinfunction "EN_1") (pintype "bidirectional"))
    )
  )
)
